# oresat-batteries.net
KiCad netlist of a schematic drawn in EAGLE
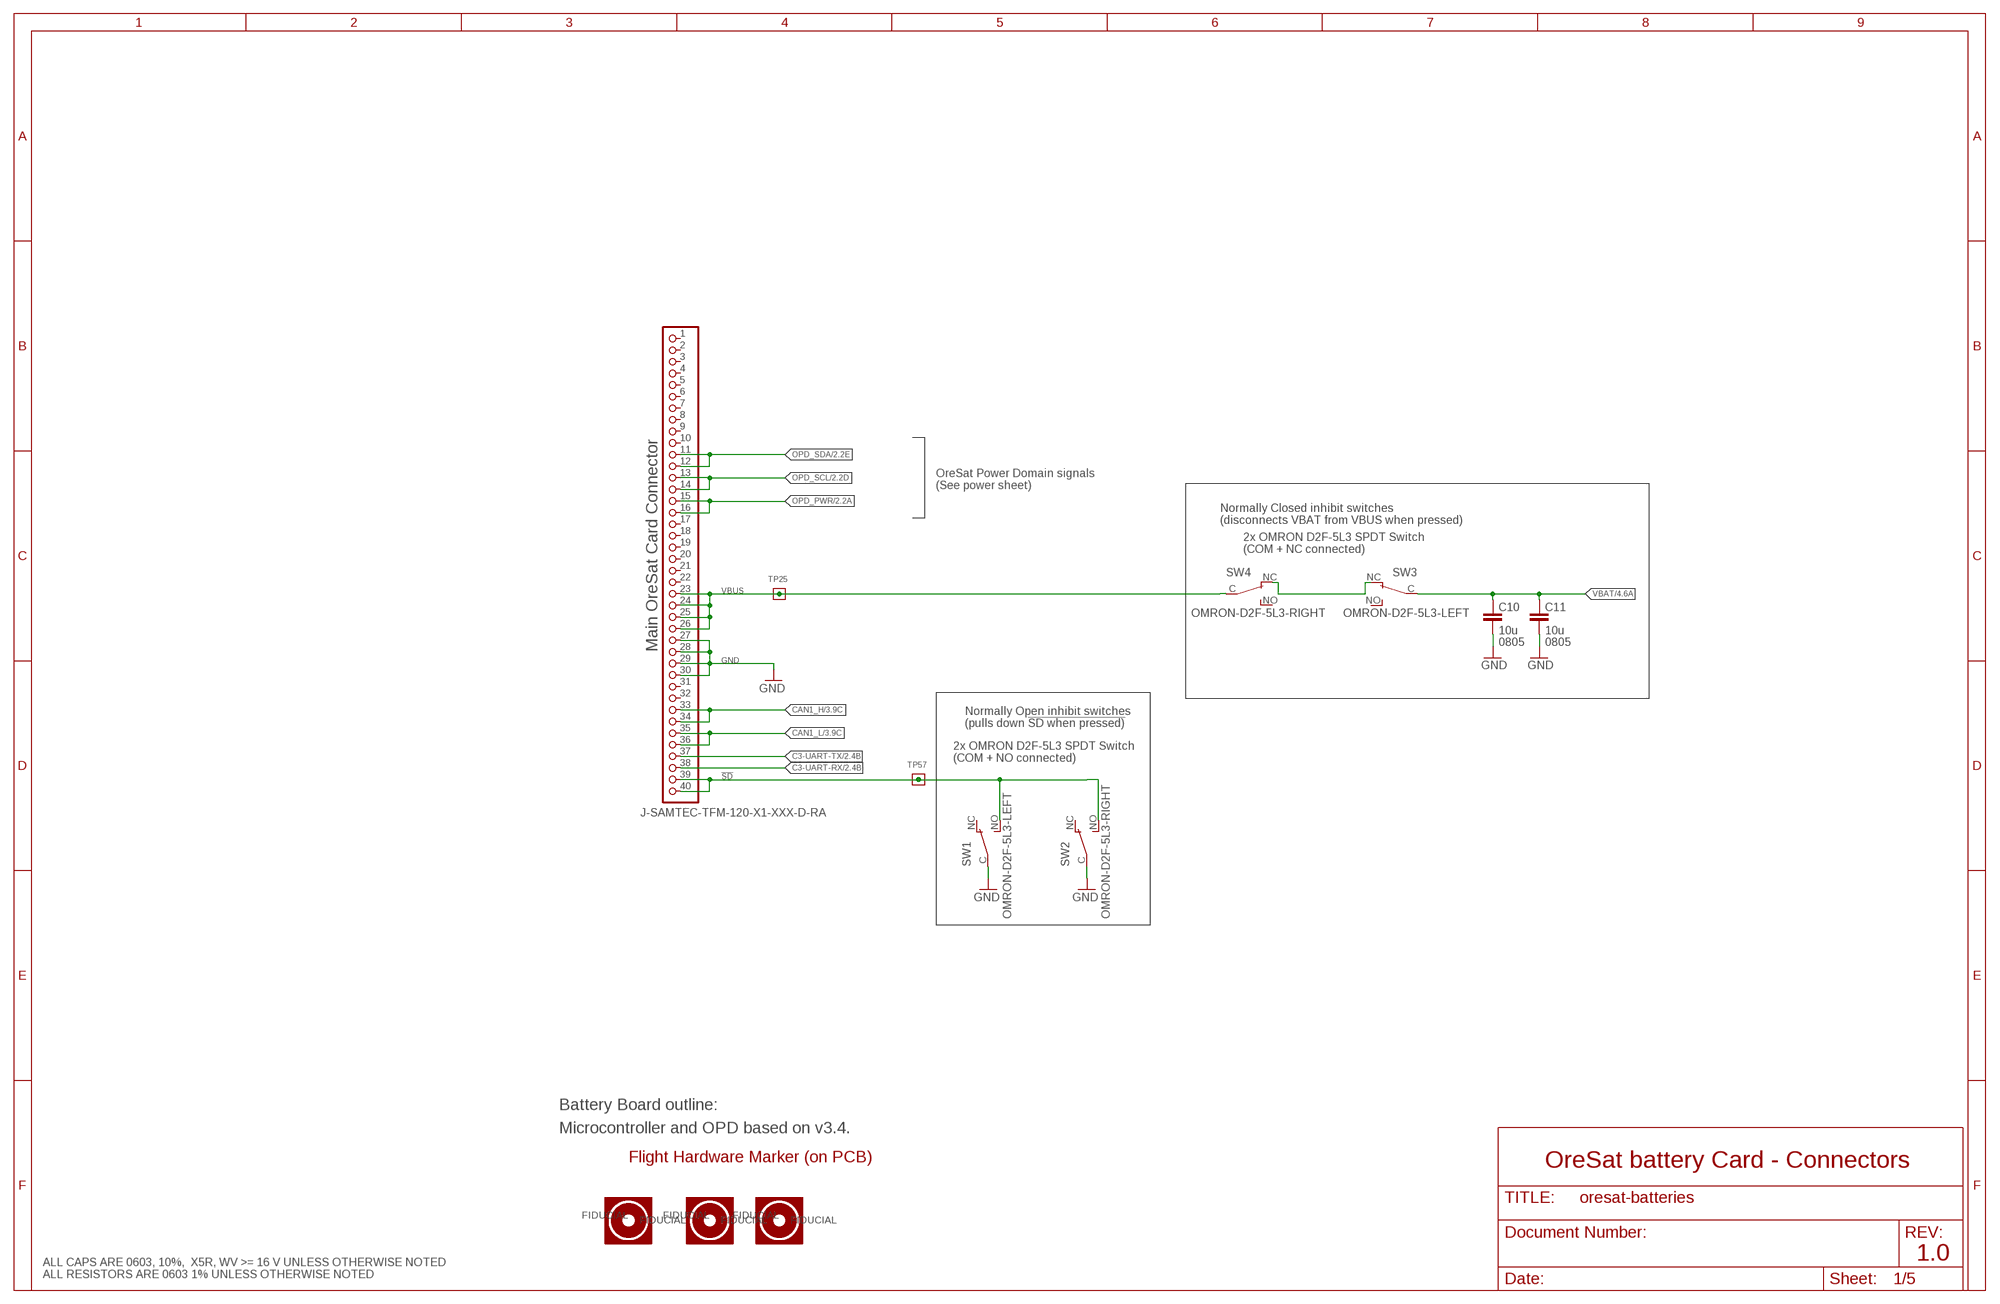
[diagram p0: schematic, sheet 1]
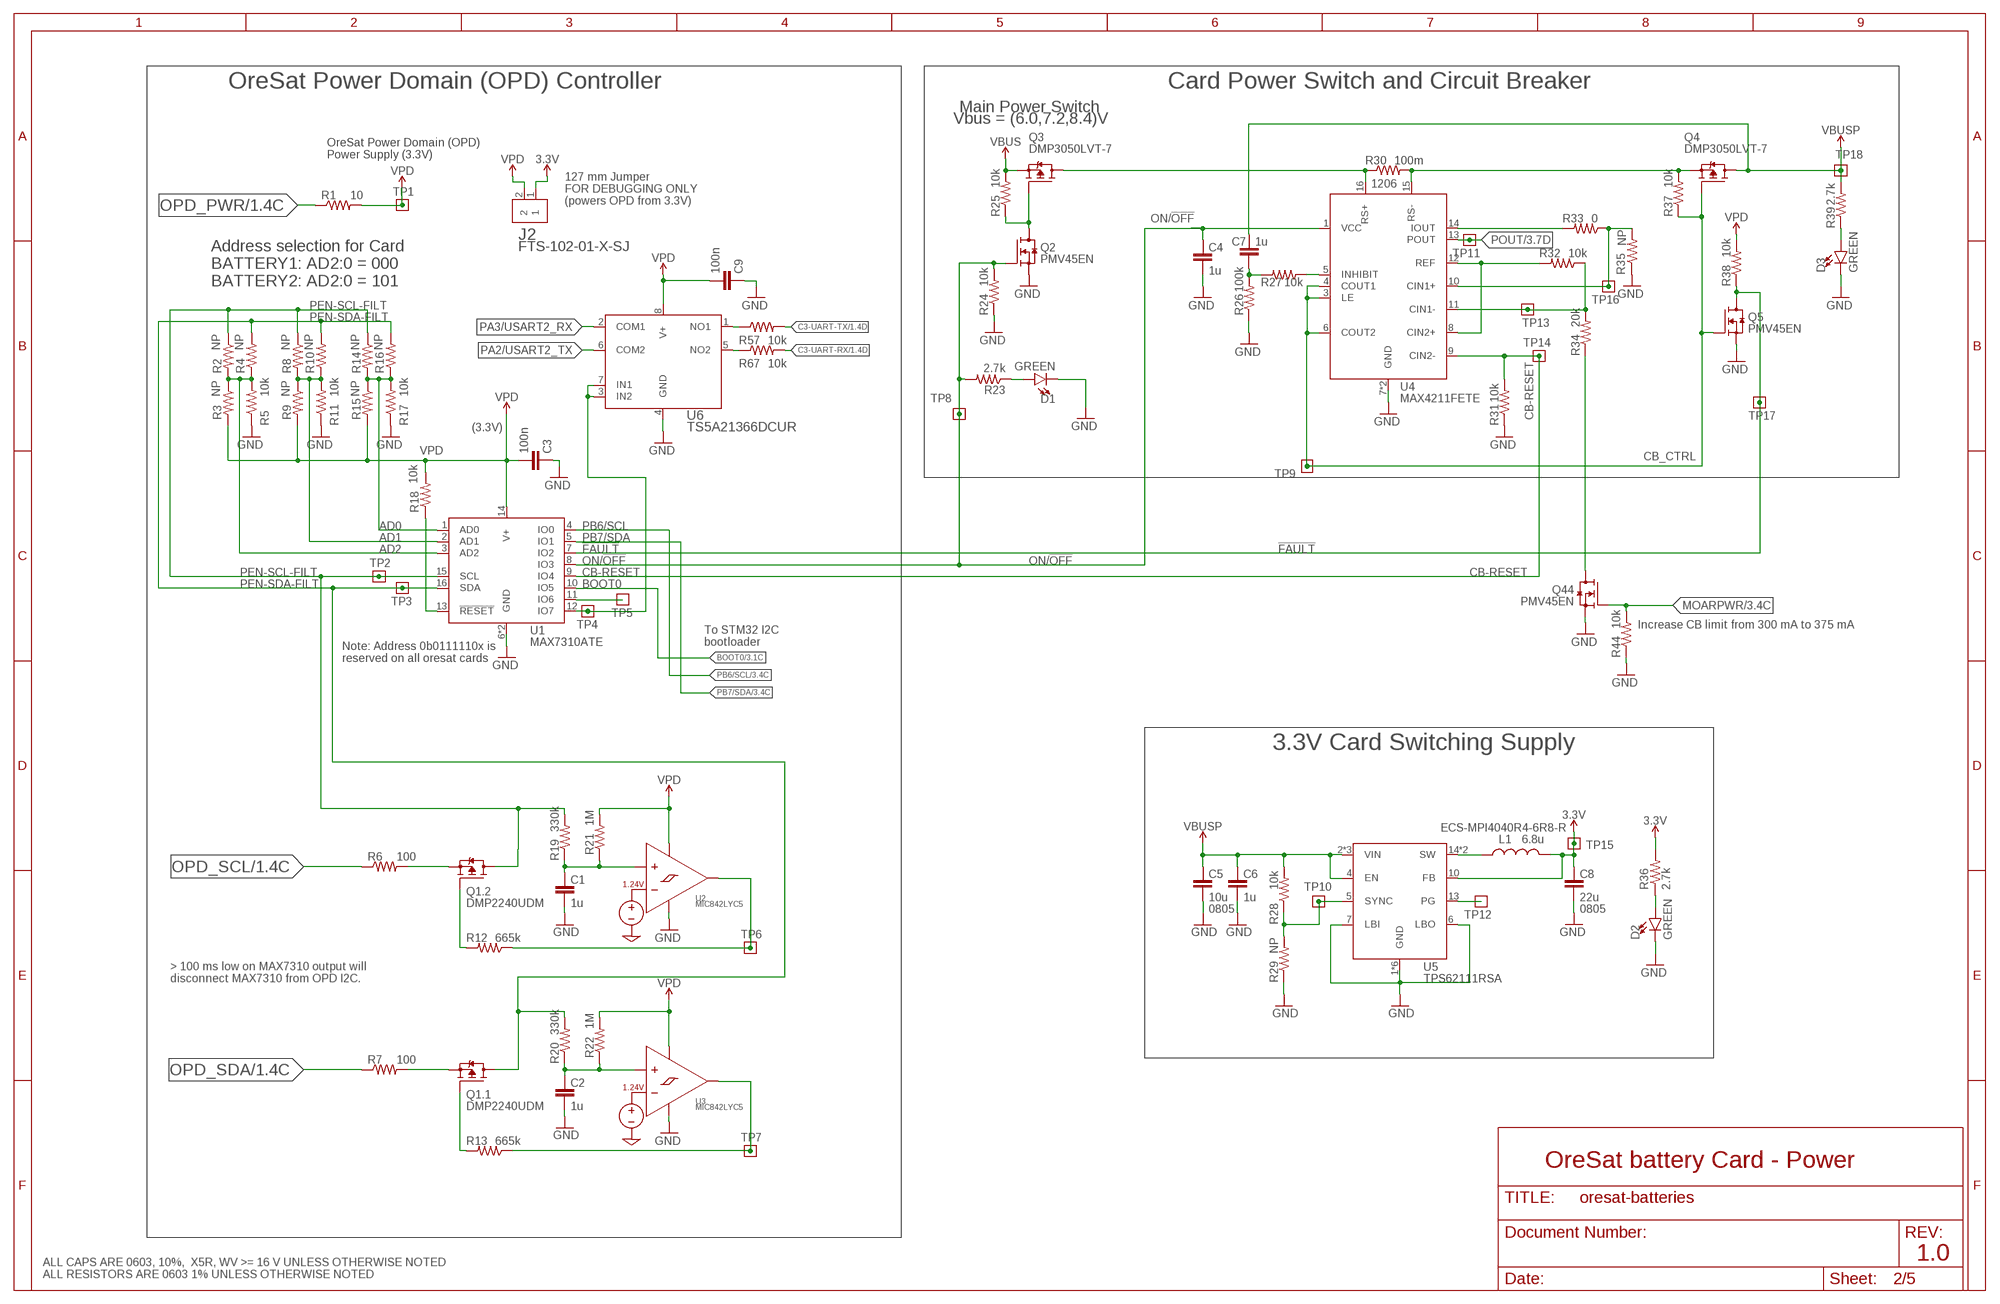
[diagram p1: schematic, sheet 2]
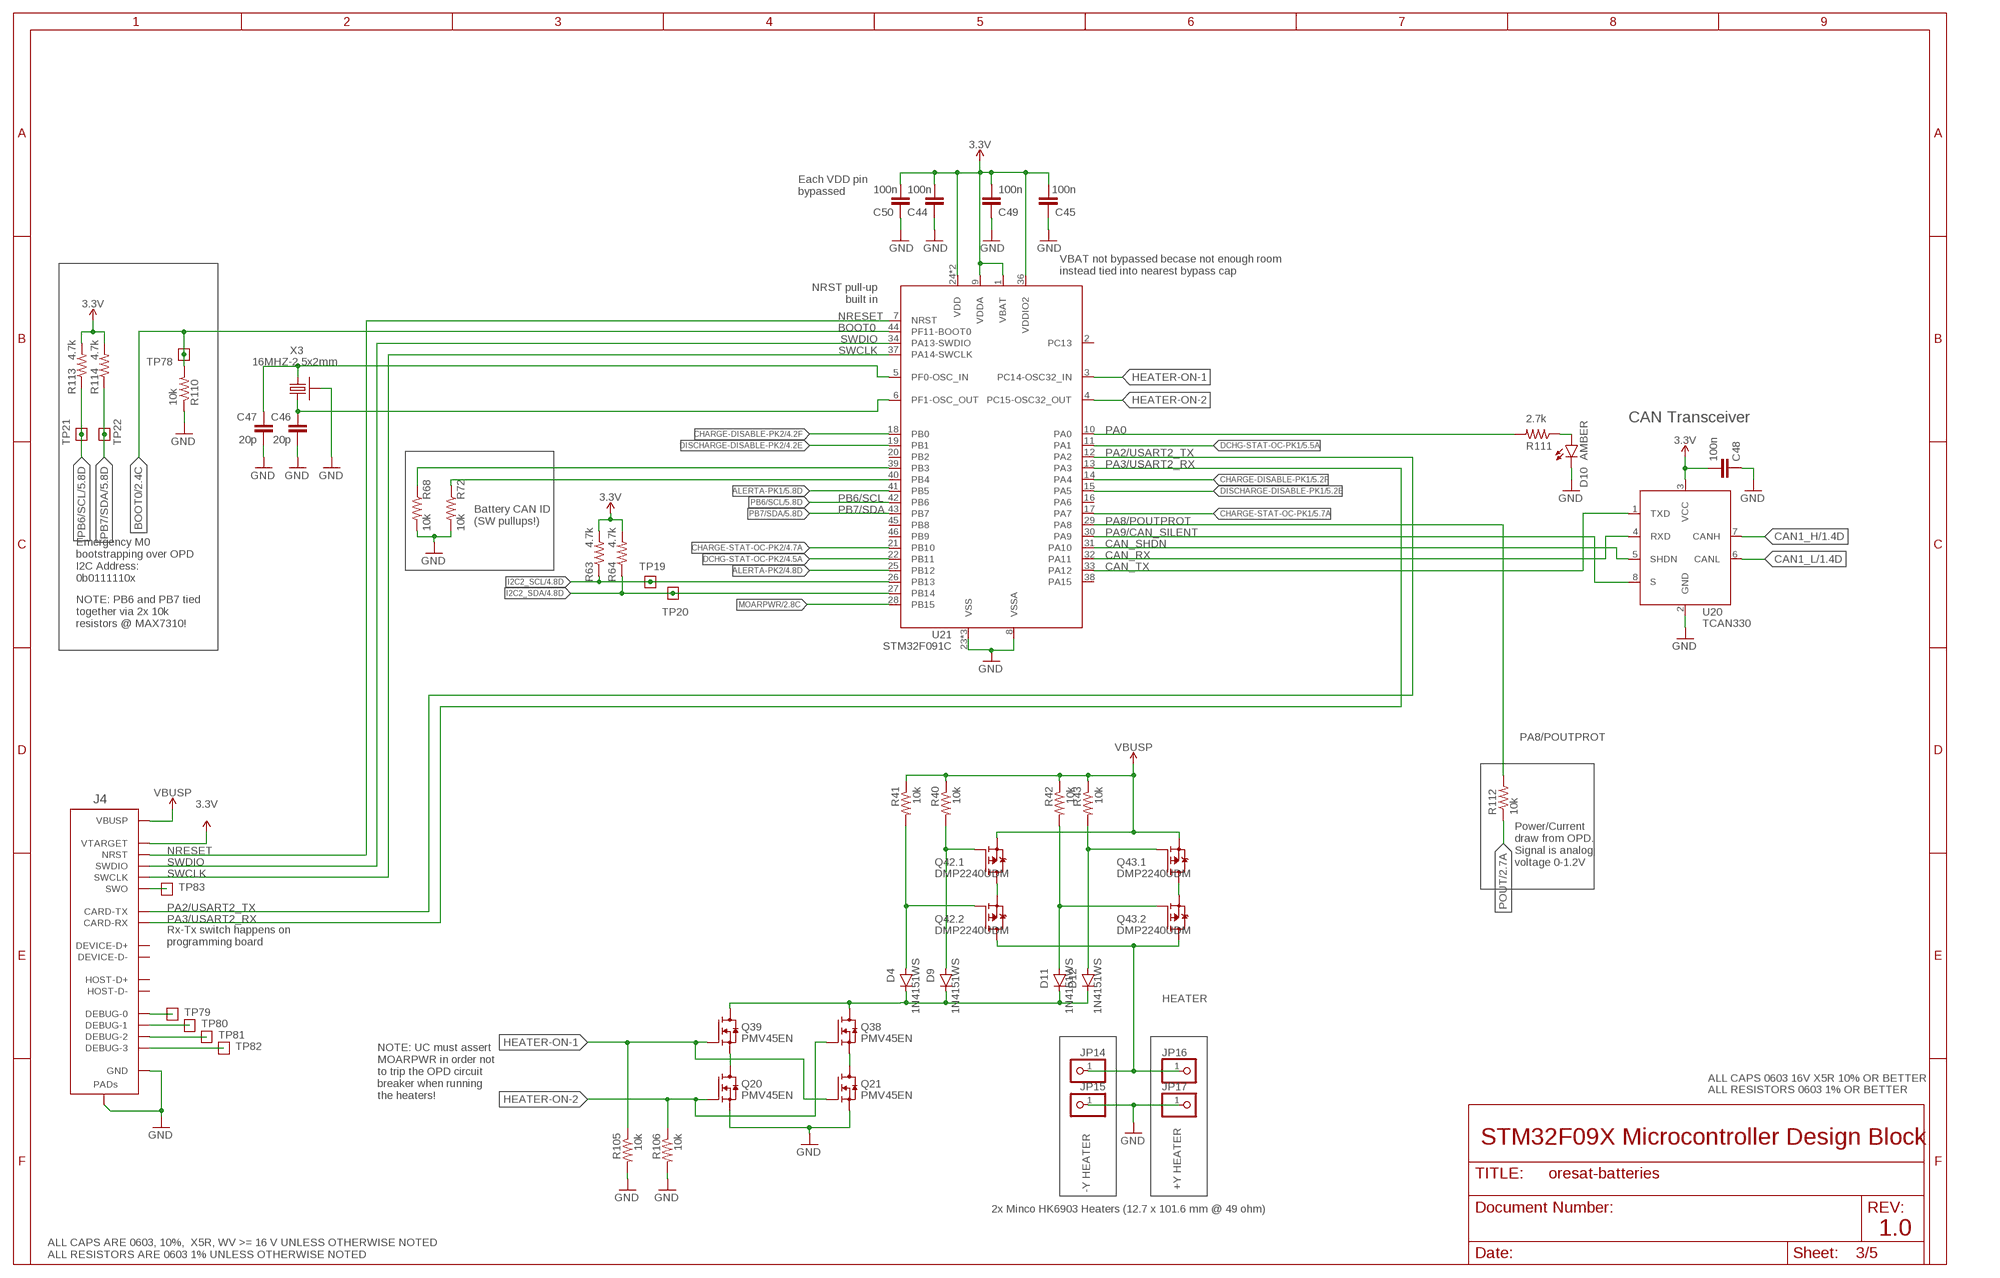
[diagram p2: schematic, sheet 3]
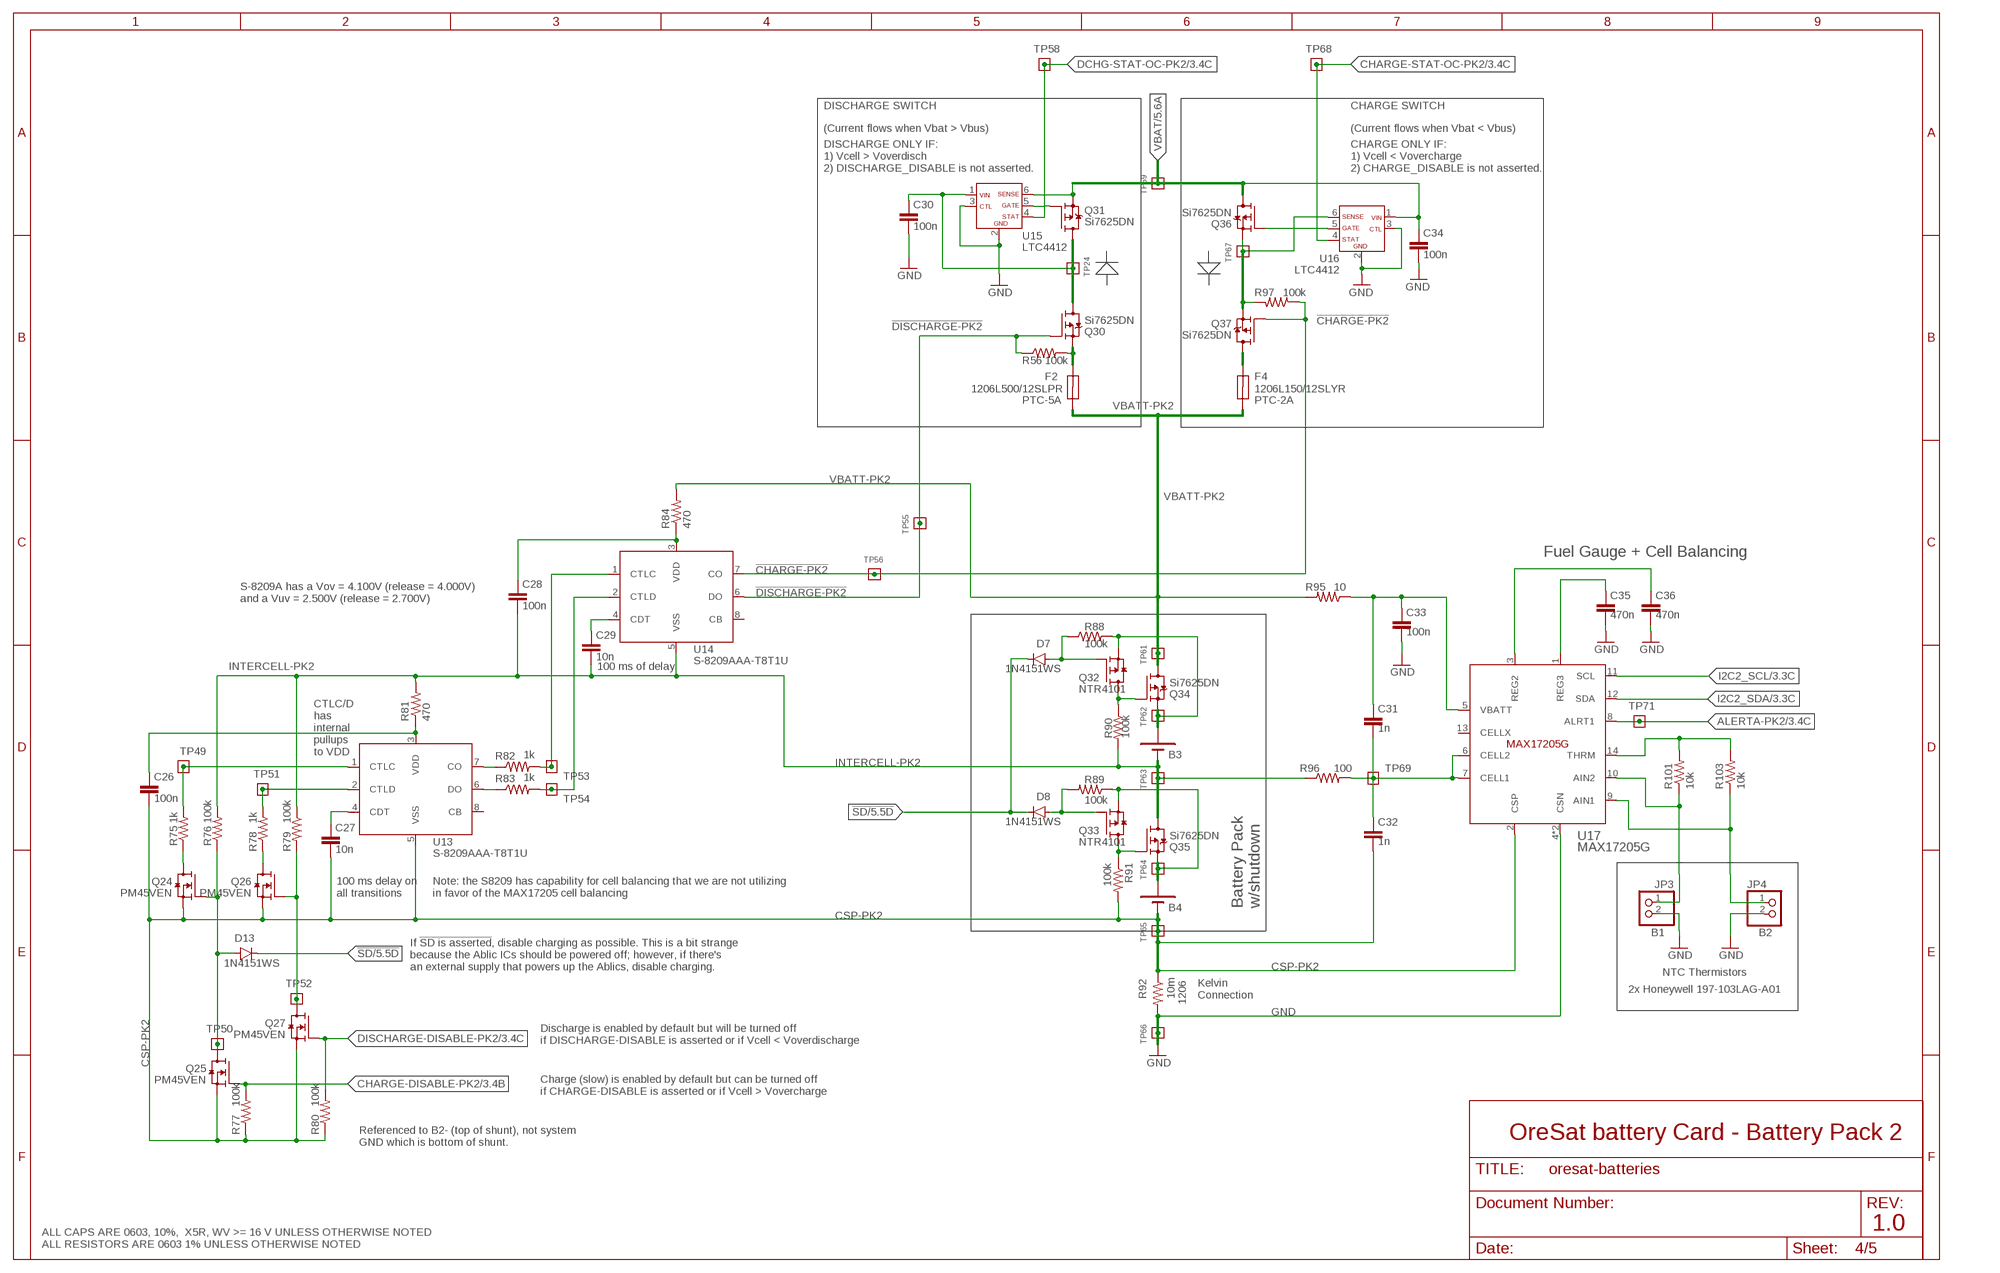
[diagram p3: schematic, sheet 4]
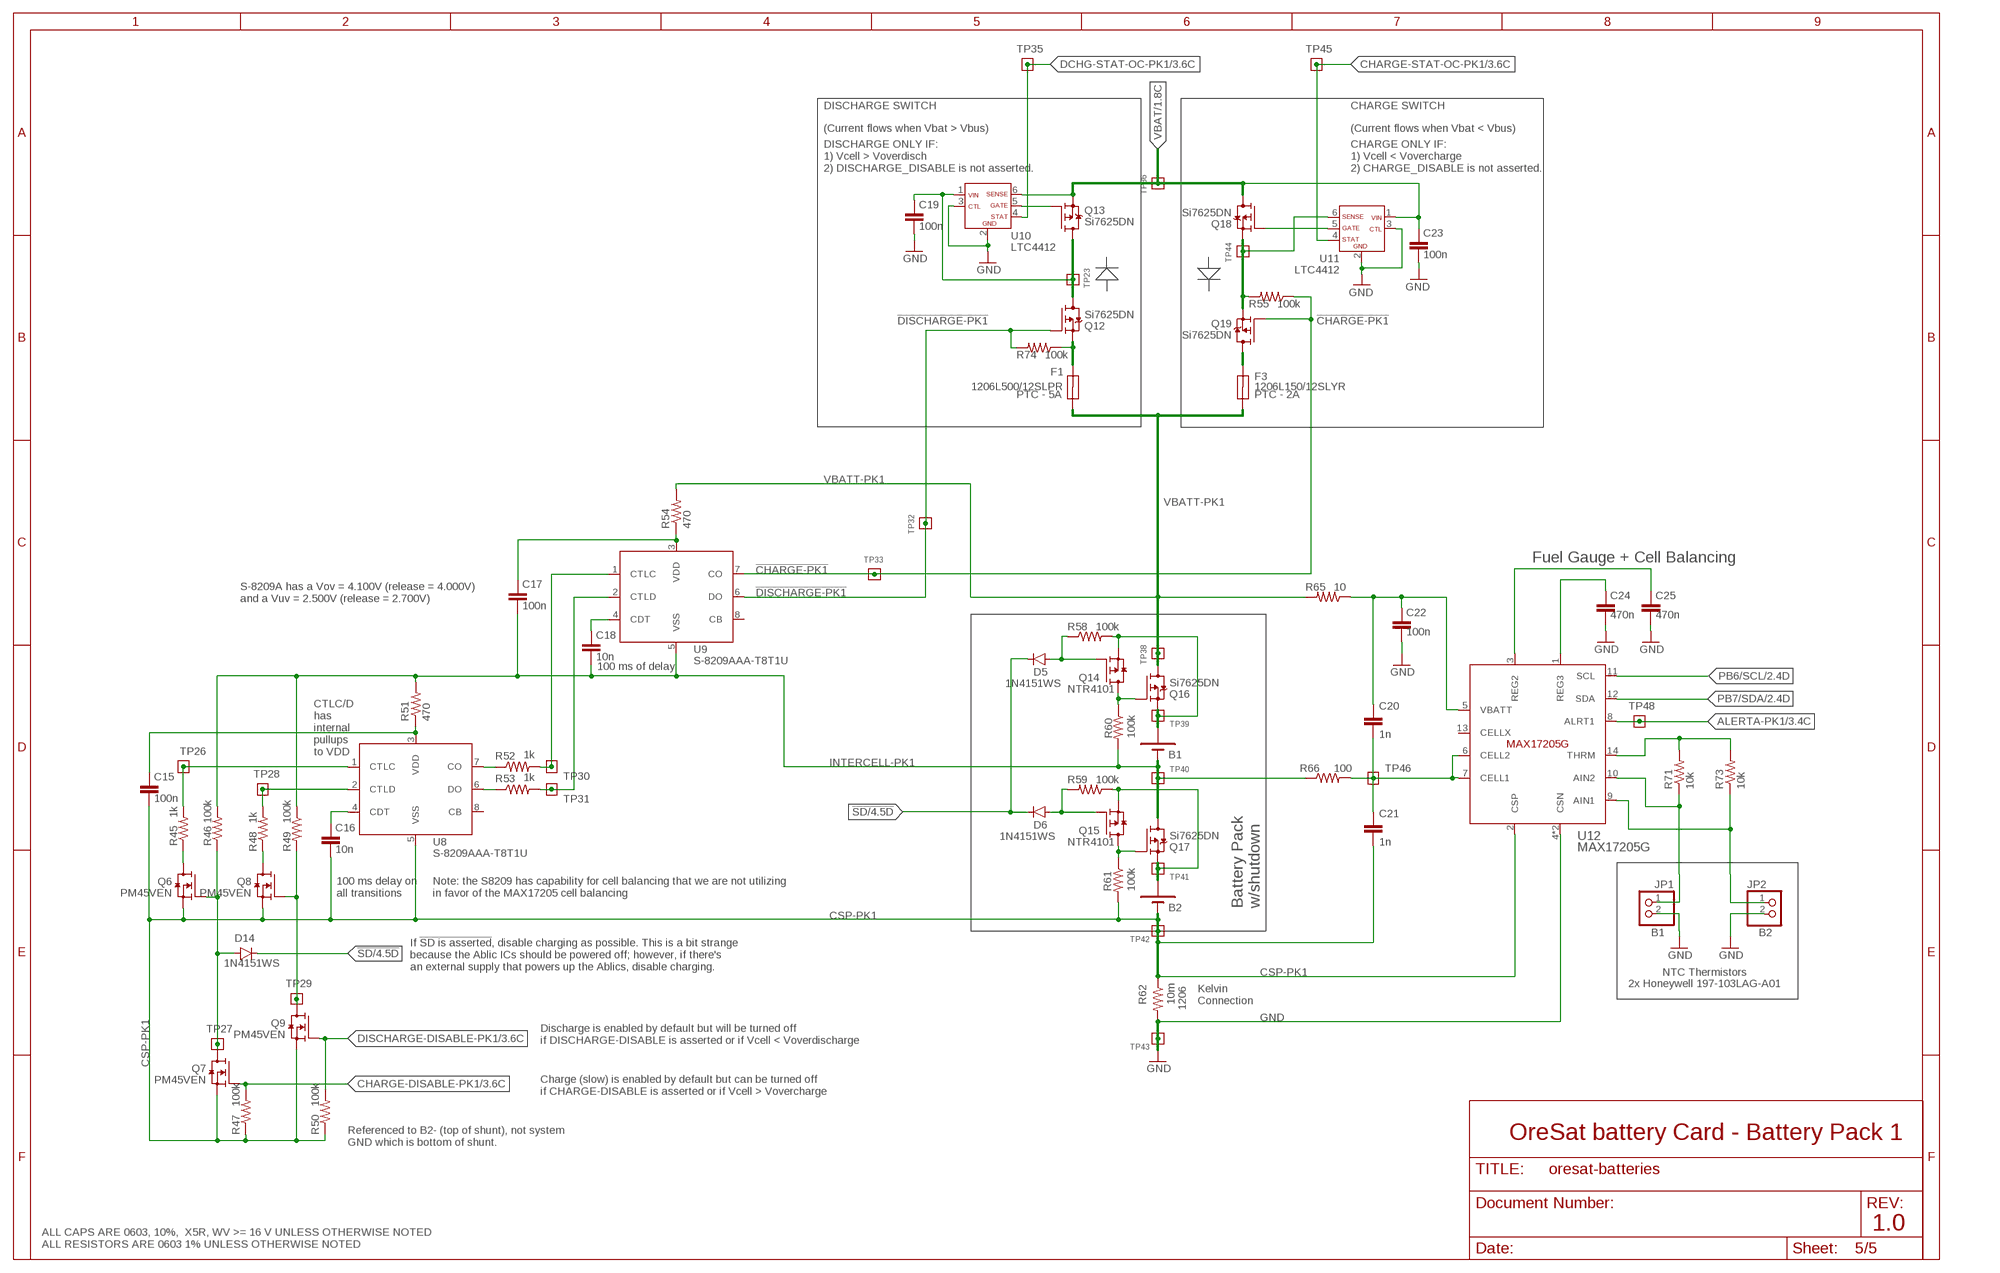
[diagram p4: schematic, sheet 5]

(export (version "E")
  (design (tool "Eeschema 10.0.6"))
  (components
    (comp (ref "C44")
      (value "100n")
      (footprint "eagle-import:.0603-C-NOSILK")
      (fields (field (name "MFR") "Samsung") (field (name "MPN") "C0603C104M4RACTU"))
      (libsource (lib "eagle-import") (part "C-EU0603-C-NOSILK"))
    )
    (comp (ref "C45")
      (value "100n")
      (footprint "eagle-import:.0603-C-NOSILK")
      (fields (field (name "MFR") "Samsung") (field (name "MPN") "C0603C104M4RACTU"))
      (libsource (lib "eagle-import") (part "C-EU0603-C-NOSILK"))
    )
    (comp (ref "C46")
      (value "20p")
      (footprint "eagle-import:.0603-C-NOSILK")
      (fields (field (name "MFR") "Yageo") (field (name "MPN") "CC0603JRNPO9BN200"))
      (libsource (lib "eagle-import") (part "C-EU0603-C-NOSILK"))
    )
    (comp (ref "C47")
      (value "20p")
      (footprint "eagle-import:.0603-C-NOSILK")
      (fields (field (name "MFR") "Yageo") (field (name "MPN") "CC0603JRNPO9BN200"))
      (libsource (lib "eagle-import") (part "C-EU0603-C-NOSILK"))
    )
    (comp (ref "C48")
      (value "100n")
      (footprint "eagle-import:.0603-C-NOSILK")
      (fields (field (name "MFR") "Samsung") (field (name "MPN") "C0603C104M4RACTU"))
      (libsource (lib "eagle-import") (part "C-EU0603-C-NOSILK"))
    )
    (comp (ref "C49")
      (value "100n")
      (footprint "eagle-import:.0603-C-NOSILK")
      (fields (field (name "MFR") "Samsung") (field (name "MPN") "C0603C104M4RACTU"))
      (libsource (lib "eagle-import") (part "C-EU0603-C-NOSILK"))
    )
    (comp (ref "C50")
      (value "100n")
      (footprint "eagle-import:.0603-C-NOSILK")
      (fields (field (name "MFR") "Samsung") (field (name "MPN") "C0603C104M4RACTU"))
      (libsource (lib "eagle-import") (part "C-EU0603-C-NOSILK"))
    )
    (comp (ref "D4")
      (value "1N4151WS")
      (footprint "eagle-import:SOD323-R")
      (fields (field (name "MFR") "Vishay") (field (name "MPN") "1N4151WS-E3-08"))
      (libsource (lib "eagle-import") (part "DIODE-SOD323-R"))
    )
    (comp (ref "D9")
      (value "1N4151WS")
      (footprint "eagle-import:SOD323-R")
      (fields (field (name "MFR") "Vishay") (field (name "MPN") "1N4151WS-E3-08"))
      (libsource (lib "eagle-import") (part "DIODE-SOD323-R"))
    )
    (comp (ref "D10")
      (value "AMBER")
      (footprint "eagle-import:LED-0603")
      (fields (field (name "MFR") "Inolux") (field (name "MPN") "IN-S63AT5A"))
      (libsource (lib "eagle-import") (part "LED-GREEN0603"))
    )
    (comp (ref "D11")
      (value "1N4151WS")
      (footprint "eagle-import:SOD323-R")
      (fields (field (name "MFR") "Vishay") (field (name "MPN") "1N4151WS-E3-08"))
      (libsource (lib "eagle-import") (part "DIODE-SOD323-R"))
    )
    (comp (ref "D12")
      (value "1N4151WS")
      (footprint "eagle-import:SOD323-R")
      (fields (field (name "MFR") "Vishay") (field (name "MPN") "1N4151WS-E3-08"))
      (libsource (lib "eagle-import") (part "DIODE-SOD323-R"))
    )
    (comp (ref "J4")
      (value "ORESAT-DEBUG-CONNECTOR-ALL")
      (footprint "eagle-import:TE_2-1734592-0")
      (fields
        (field (name "MPN") "2-1734592-0")
        (field (name "DPN") "A100287CT-ND")
        (field (name "MFR") "TE")
        (field (name "MPN_1") "2-1734592-0")
      )
      (libsource (lib "eagle-import") (part "ORESAT-DEBUG-CONNECTOR-ALL"))
    )
    (comp (ref "JP14")
      (value "PINHD-1X1")
      (footprint "eagle-import:1X01")
      (libsource (lib "eagle-import") (part "PINHD-1X1"))
    )
    (comp (ref "JP15")
      (value "PINHD-1X1")
      (footprint "eagle-import:1X01")
      (libsource (lib "eagle-import") (part "PINHD-1X1"))
    )
    (comp (ref "JP16")
      (value "PINHD-1X1")
      (footprint "eagle-import:1X01")
      (libsource (lib "eagle-import") (part "PINHD-1X1"))
    )
    (comp (ref "JP17")
      (value "PINHD-1X1")
      (footprint "eagle-import:1X01")
      (libsource (lib "eagle-import") (part "PINHD-1X1"))
    )
    (comp (ref "Q20")
      (value "PMV45EN")
      (footprint "eagle-import:SOT23-3")
      (libsource (lib "eagle-import") (part "N-MOSFET-SOT-23-3"))
    )
    (comp (ref "Q21")
      (value "PMV45EN")
      (footprint "eagle-import:SOT23-3")
      (libsource (lib "eagle-import") (part "N-MOSFET-SOT-23-3"))
    )
    (comp (ref "Q38")
      (value "PMV45EN")
      (footprint "eagle-import:SOT23-3")
      (libsource (lib "eagle-import") (part "N-MOSFET-SOT-23-3"))
    )
    (comp (ref "Q39")
      (value "PMV45EN")
      (footprint "eagle-import:SOT23-3")
      (libsource (lib "eagle-import") (part "N-MOSFET-SOT-23-3"))
    )
    (comp (ref "Q42")
      (value "DMP2240UDM")
      (footprint "eagle-import:SOT23-6")
      (libsource (lib "eagle-import") (part "Q-MOSFET-PCH-dual-SOT23-6_MOSFET-PCH-SOT23-6"))
    )
    (comp (ref "Q43")
      (value "DMP2240UDM")
      (footprint "eagle-import:SOT23-6")
      (libsource (lib "eagle-import") (part "Q-MOSFET-PCH-dual-SOT23-6_MOSFET-PCH-SOT23-6"))
    )
    (comp (ref "R40")
      (value "10k")
      (footprint "eagle-import:.0603-C-NOSILK")
      (fields (field (name "MFR") "Yageo") (field (name "MPN") "RC0603FR-0710KL"))
      (libsource (lib "eagle-import") (part "R-US_0603-C-NOSILK"))
    )
    (comp (ref "R41")
      (value "10k")
      (footprint "eagle-import:.0603-C-NOSILK")
      (fields (field (name "MFR") "Yageo") (field (name "MPN") "RC0603FR-0710KL"))
      (libsource (lib "eagle-import") (part "R-US_0603-C-NOSILK"))
    )
    (comp (ref "R42")
      (value "10k")
      (footprint "eagle-import:.0603-C-NOSILK")
      (fields (field (name "MFR") "Yageo") (field (name "MPN") "RC0603FR-0710KL"))
      (libsource (lib "eagle-import") (part "R-US_0603-C-NOSILK"))
    )
    (comp (ref "R43")
      (value "10k")
      (footprint "eagle-import:.0603-C-NOSILK")
      (fields (field (name "MFR") "Yageo") (field (name "MPN") "RC0603FR-0710KL"))
      (libsource (lib "eagle-import") (part "R-US_0603-C-NOSILK"))
    )
    (comp (ref "R63")
      (value "4.7k")
      (footprint "eagle-import:.0603-C-NOSILK")
      (fields (field (name "MFR") "TE Connectivity") (field (name "MPN") "RR0816P-472-D"))
      (libsource (lib "eagle-import") (part "R-US_0603-C-NOSILK"))
    )
    (comp (ref "R64")
      (value "4.7k")
      (footprint "eagle-import:.0603-C-NOSILK")
      (fields (field (name "MFR") "TE Connectivity") (field (name "MPN") "RR0816P-472-D"))
      (libsource (lib "eagle-import") (part "R-US_0603-C-NOSILK"))
    )
    (comp (ref "R68")
      (value "10k")
      (footprint "eagle-import:.0603-C-NOSILK")
      (fields (field (name "MFR") "TE Connectivity") (field (name "MPN") "RR0816P-472-D"))
      (libsource (lib "eagle-import") (part "R-US_0603-C-NOSILK"))
    )
    (comp (ref "R72")
      (value "10k")
      (footprint "eagle-import:.0603-C-NOSILK")
      (fields (field (name "MFR") "TE Connectivity") (field (name "MPN") "RR0816P-472-D"))
      (libsource (lib "eagle-import") (part "R-US_0603-C-NOSILK"))
    )
    (comp (ref "R105")
      (value "10k")
      (footprint "eagle-import:.0603-C-NOSILK")
      (fields (field (name "MFR") "Yageo") (field (name "MPN") "RC0603FR-0710KL"))
      (libsource (lib "eagle-import") (part "R-US_0603-C-NOSILK"))
    )
    (comp (ref "R106")
      (value "10k")
      (footprint "eagle-import:.0603-C-NOSILK")
      (fields (field (name "MFR") "Yageo") (field (name "MPN") "RC0603FR-0710KL"))
      (libsource (lib "eagle-import") (part "R-US_0603-C-NOSILK"))
    )
    (comp (ref "R110")
      (value "10k")
      (footprint "eagle-import:.0603-C-NOSILK")
      (fields (field (name "MFR") "Yageo") (field (name "MPN") "RC0603FR-0710KL"))
      (libsource (lib "eagle-import") (part "R-US_0603-C-NOSILK"))
    )
    (comp (ref "R111")
      (value "2.7k")
      (footprint "eagle-import:.0603-C-NOSILK")
      (fields (field (name "MFR") "TE") (field (name "MPN") "CRGCQ0603F2K7"))
      (libsource (lib "eagle-import") (part "R-US_0603-C-NOSILK"))
    )
    (comp (ref "R112")
      (value "10k")
      (footprint "eagle-import:.0603-C-NOSILK")
      (fields (field (name "MFR") "Yageo") (field (name "MPN") "RC0603FR-0710KL"))
      (libsource (lib "eagle-import") (part "R-US_0603-C-NOSILK"))
    )
    (comp (ref "R113")
      (value "4.7k")
      (footprint "eagle-import:.0603-C-NOSILK")
      (fields (field (name "MFR") "TE Connectivity") (field (name "MPN") "RR0816P-472-D"))
      (libsource (lib "eagle-import") (part "R-US_0603-C-NOSILK"))
    )
    (comp (ref "R114")
      (value "4.7k")
      (footprint "eagle-import:.0603-C-NOSILK")
      (fields (field (name "MFR") "TE Connectivity") (field (name "MPN") "RR0816P-472-D"))
      (libsource (lib "eagle-import") (part "R-US_0603-C-NOSILK"))
    )
    (comp (ref "TP19")
      (value "TEST-POINT-LARGE-SQUARE")
      (footprint "eagle-import:1X01")
      (libsource (lib "eagle-import") (part "TEST-POINT-LARGE-SQUARE"))
    )
    (comp (ref "TP20")
      (value "TEST-POINT-LARGE-SQUARE")
      (footprint "eagle-import:1X01")
      (libsource (lib "eagle-import") (part "TEST-POINT-LARGE-SQUARE"))
    )
    (comp (ref "TP21")
      (value "TEST-POINT-LARGE-SQUARE")
      (footprint "eagle-import:1X01")
      (libsource (lib "eagle-import") (part "TEST-POINT-LARGE-SQUARE"))
    )
    (comp (ref "TP22")
      (value "TEST-POINT-LARGE-SQUARE")
      (footprint "eagle-import:1X01")
      (libsource (lib "eagle-import") (part "TEST-POINT-LARGE-SQUARE"))
    )
    (comp (ref "TP78")
      (value "TEST-POINT-LARGE-SQUARE")
      (footprint "eagle-import:1X01")
      (libsource (lib "eagle-import") (part "TEST-POINT-LARGE-SQUARE"))
    )
    (comp (ref "TP79")
      (value "TEST-POINT-LARGE-SQUARE")
      (footprint "eagle-import:1X01")
      (libsource (lib "eagle-import") (part "TEST-POINT-LARGE-SQUARE"))
    )
    (comp (ref "TP80")
      (value "TEST-POINT-LARGE-SQUARE")
      (footprint "eagle-import:1X01")
      (libsource (lib "eagle-import") (part "TEST-POINT-LARGE-SQUARE"))
    )
    (comp (ref "TP81")
      (value "TEST-POINT-LARGE-SQUARE")
      (footprint "eagle-import:1X01")
      (libsource (lib "eagle-import") (part "TEST-POINT-LARGE-SQUARE"))
    )
    (comp (ref "TP82")
      (value "TEST-POINT-LARGE-SQUARE")
      (footprint "eagle-import:1X01")
      (libsource (lib "eagle-import") (part "TEST-POINT-LARGE-SQUARE"))
    )
    (comp (ref "TP83")
      (value "TEST-POINT-LARGE-SQUARE")
      (footprint "eagle-import:1X01")
      (libsource (lib "eagle-import") (part "TEST-POINT-LARGE-SQUARE"))
    )
    (comp (ref "U20")
      (value "TCAN330")
      (footprint "eagle-import:SOT23-8_TI-DCN")
      (fields (field (name "MFR") "Texas Instruments") (field (name "MPN") "TCAN330GDCNT"))
      (libsource (lib "eagle-import") (part "TCAN330"))
    )
    (comp (ref "U21")
      (value "STM32F091C")
      (footprint "eagle-import:STM32F091C")
      (fields (field (name "MFR") "STMicroelectronics") (field (name "MPN") "STM32F091CBT6"))
      (libsource (lib "eagle-import") (part "STM32F091C"))
    )
    (comp (ref "X3")
      (value "16MHZ-2.5x2mm")
      (footprint "eagle-import:CRYSTAL_2.5X2")
      (fields (field (name "MFR") "ECS Inc.") (field (name "MPN") "ECS-160-10-36Q-ES-TR"))
      (libsource (lib "eagle-import") (part "CRYSTAL-WITH-GND"))
    )
    (comp (ref "C1")
      (value "1u")
      (footprint "eagle-import:.0603-C-NOSILK")
      (fields (field (name "MFR") "Samsung") (field (name "MPN") "CL10B105MO8NNWC"))
      (libsource (lib "eagle-import") (part "C-EU0603-C-NOSILK"))
    )
    (comp (ref "C2")
      (value "1u")
      (footprint "eagle-import:.0603-C-NOSILK")
      (fields (field (name "MFR") "Samsung") (field (name "MPN") "CL10B105MO8NNWC"))
      (libsource (lib "eagle-import") (part "C-EU0603-C-NOSILK"))
    )
    (comp (ref "C3")
      (value "100n")
      (footprint "eagle-import:.0603-C-NOSILK")
      (fields (field (name "MFR") "Samsung") (field (name "MPN") "CL05B104KO5NNNC"))
      (libsource (lib "eagle-import") (part "C-EU0603-C-NOSILK"))
    )
    (comp (ref "C4")
      (value "1u")
      (footprint "eagle-import:.0603-C-NOSILK")
      (fields (field (name "MFR") "Samsung") (field (name "MPN") "CL10B105MO8NNWC"))
      (libsource (lib "eagle-import") (part "C-EU0603-C-NOSILK"))
    )
    (comp (ref "C5")
      (value "10u")
      (footprint "eagle-import:.0805-B-NOSILK")
      (fields (field (name "MFR") "Samsung") (field (name "MPN") "CL21A106KOFNNNE"))
      (libsource (lib "eagle-import") (part "C-EU0805-B-NOSILK"))
    )
    (comp (ref "C6")
      (value "1u")
      (footprint "eagle-import:.0603-C-NOSILK")
      (fields (field (name "MFR") "Yageo") (field (name "MPN") "CC0603KRX7R7BB105"))
      (libsource (lib "eagle-import") (part "C-EU0603-C-NOSILK"))
    )
    (comp (ref "C7")
      (value "1u")
      (footprint "eagle-import:.0603-C-NOSILK")
      (libsource (lib "eagle-import") (part "C-EU0603-C-NOSILK"))
    )
    (comp (ref "C8")
      (value "22u")
      (footprint "eagle-import:.0805-B-NOSILK")
      (fields (field (name "MFR") "Murata") (field (name "MPN") "GRM21BR61A226ME51L"))
      (libsource (lib "eagle-import") (part "C-EU0805-B-NOSILK"))
    )
    (comp (ref "C9")
      (value "100n")
      (footprint "eagle-import:.0603-C-NOSILK")
      (fields (field (name "MFR") "Samsung") (field (name "MPN") "CL05B104KO5NNNC"))
      (libsource (lib "eagle-import") (part "C-EU0603-C-NOSILK"))
    )
    (comp (ref "D1")
      (value "GREEN")
      (footprint "eagle-import:LED-0603")
      (fields (field (name "MFR") "Inolux") (field (name "MPN") "IN-S63AT5A"))
      (libsource (lib "eagle-import") (part "LED-GREEN0603"))
    )
    (comp (ref "D2")
      (value "GREEN")
      (footprint "eagle-import:LED-0603")
      (fields (field (name "MFR") "Rohm") (field (name "MPN") "SML-E12M8WT86"))
      (libsource (lib "eagle-import") (part "LED-GREEN0603"))
    )
    (comp (ref "D3")
      (value "GREEN")
      (footprint "eagle-import:LED-0603")
      (fields (field (name "MFR") "Rohm") (field (name "MPN") "SML-E12M8WT86"))
      (libsource (lib "eagle-import") (part "LED-GREEN0603"))
    )
    (comp (ref "J2")
      (value "FTS-102-01-X-SJ")
      (footprint "eagle-import:SAMTEC-FTS-102-01-X-S")
      (libsource (lib "eagle-import") (part "SAMTEC-FTS-102-01-X-SJ"))
    )
    (comp (ref "L1")
      (value "6.8u")
      (footprint "eagle-import:ECS-MPI4040")
      (fields (field (name "MFR") "ECS") (field (name "MPN") "ECS-MPI4040R4-6R8-R"))
      (libsource (lib "eagle-import") (part "L-ECS-MPI4040"))
    )
    (comp (ref "Q1")
      (value "DMP2240UDM")
      (footprint "eagle-import:SOT23-6")
      (fields
        (field (name "DIS") "Digi-Key")
        (field (name "DPN") "GRM21BR61A226ME51L ")
        (field (name "MFR") "Diodes Inc")
        (field (name "MPN") "DMP2240UDM")
      )
      (libsource (lib "eagle-import") (part "Q-MOSFET-PCH-dual-SOT23-6_MOSFET-PCH-SOT23-6"))
    )
    (comp (ref "Q2")
      (value "PMV45EN")
      (footprint "eagle-import:SOT23-3")
      (fields (field (name "MFR") "Nexperia") (field (name "MPN") "PMV45EN2R"))
      (libsource (lib "eagle-import") (part "N-MOSFET-SOT-23-3"))
    )
    (comp (ref "Q3")
      (value "DMP3050LVT-7")
      (footprint "eagle-import:SOT23-6")
      (fields (field (name "MFR") "Diodes Inc"))
      (libsource (lib "eagle-import") (part "MOSFET-PCH-SOT23-6"))
    )
    (comp (ref "Q4")
      (value "DMP3050LVT-7")
      (footprint "eagle-import:SOT23-6")
      (fields (field (name "MFR") "Diodes Inc"))
      (libsource (lib "eagle-import") (part "MOSFET-PCH-SOT23-6"))
    )
    (comp (ref "Q5")
      (value "PMV45EN")
      (footprint "eagle-import:SOT23-3")
      (fields (field (name "MFR") "Nexperia") (field (name "MPN") "PMV45EN2R"))
      (libsource (lib "eagle-import") (part "N-MOSFET-SOT-23-3"))
    )
    (comp (ref "Q44")
      (value "PMV45EN")
      (footprint "eagle-import:SOT23-3")
      (fields (field (name "MFR") "Nexperia") (field (name "MPN") "PMV45EN2R"))
      (libsource (lib "eagle-import") (part "N-MOSFET-SOT-23-3"))
    )
    (comp (ref "R1")
      (value "10")
      (footprint "eagle-import:.0603-C-NOSILK")
      (fields (field (name "MFR") "Yageo") (field (name "MPN") "RC0603FR-0710RL"))
      (libsource (lib "eagle-import") (part "R-US_0603-C-NOSILK"))
    )
    (comp (ref "R2")
      (value "NP")
      (footprint "eagle-import:.0603-C-NOSILK")
      (fields (field (name "MFR") "Yageo") (field (name "MPN") "RC0603FR-07665KL"))
      (libsource (lib "eagle-import") (part "R-US_0603-C-NOSILK"))
    )
    (comp (ref "R3")
      (value "NP")
      (footprint "eagle-import:.0603-C-NOSILK")
      (fields (field (name "MFR") "Yageo") (field (name "MPN") "RC0603FR-07665KL"))
      (libsource (lib "eagle-import") (part "R-US_0603-C-NOSILK"))
    )
    (comp (ref "R4")
      (value "NP")
      (footprint "eagle-import:.0603-C-NOSILK")
      (fields (field (name "MFR") "Yageo") (field (name "MPN") "RC0603FR-07665KL"))
      (libsource (lib "eagle-import") (part "R-US_0603-C-NOSILK"))
    )
    (comp (ref "R5")
      (value "10k")
      (footprint "eagle-import:.0603-C-NOSILK")
      (fields (field (name "MFR") "Yageo") (field (name "MPN") "RC0603FR-07665KL"))
      (libsource (lib "eagle-import") (part "R-US_0603-C-NOSILK"))
    )
    (comp (ref "R6")
      (value "100")
      (footprint "eagle-import:.0603-C-NOSILK")
      (fields (field (name "MFR") "Yageo") (field (name "MPN") "RC0603FR-07100RL"))
      (libsource (lib "eagle-import") (part "R-US_0603-C-NOSILK"))
    )
    (comp (ref "R7")
      (value "100")
      (footprint "eagle-import:.0603-C-NOSILK")
      (fields (field (name "MFR") "Yageo") (field (name "MPN") "RC0603FR-07100RL"))
      (libsource (lib "eagle-import") (part "R-US_0603-C-NOSILK"))
    )
    (comp (ref "R8")
      (value "NP")
      (footprint "eagle-import:.0603-C-NOSILK")
      (fields (field (name "MFR") "Yageo") (field (name "MPN") "RC0603FR-07665KL"))
      (libsource (lib "eagle-import") (part "R-US_0603-C-NOSILK"))
    )
    (comp (ref "R9")
      (value "NP")
      (footprint "eagle-import:.0603-C-NOSILK")
      (fields (field (name "MFR") "Yageo") (field (name "MPN") "RC0603FR-07665KL"))
      (libsource (lib "eagle-import") (part "R-US_0603-C-NOSILK"))
    )
    (comp (ref "R10")
      (value "NP")
      (footprint "eagle-import:.0603-C-NOSILK")
      (fields (field (name "MFR") "Yageo") (field (name "MPN") "RC0603FR-07665KL"))
      (libsource (lib "eagle-import") (part "R-US_0603-C-NOSILK"))
    )
    (comp (ref "R11")
      (value "10k")
      (footprint "eagle-import:.0603-C-NOSILK")
      (fields (field (name "MFR") "Yageo") (field (name "MPN") "RC0603FR-07665KL"))
      (libsource (lib "eagle-import") (part "R-US_0603-C-NOSILK"))
    )
    (comp (ref "R12")
      (value "665k")
      (footprint "eagle-import:.0603-C-NOSILK")
      (fields (field (name "MFR") "Yageo") (field (name "MPN") "RC0603FR-07665KL"))
      (libsource (lib "eagle-import") (part "R-US_0603-C-NOSILK"))
    )
    (comp (ref "R13")
      (value "665k")
      (footprint "eagle-import:.0603-C-NOSILK")
      (fields (field (name "MFR") "Yageo") (field (name "MPN") "RC0603FR-07665KL"))
      (libsource (lib "eagle-import") (part "R-US_0603-C-NOSILK"))
    )
    (comp (ref "R14")
      (value "NP")
      (footprint "eagle-import:.0603-C-NOSILK")
      (fields (field (name "MFR") "Yageo") (field (name "MPN") "RC0603FR-07665KL"))
      (libsource (lib "eagle-import") (part "R-US_0603-C-NOSILK"))
    )
    (comp (ref "R15")
      (value "NP")
      (footprint "eagle-import:.0603-C-NOSILK")
      (fields (field (name "MFR") "Yageo") (field (name "MPN") "RC0603FR-07665KL"))
      (libsource (lib "eagle-import") (part "R-US_0603-C-NOSILK"))
    )
    (comp (ref "R16")
      (value "NP")
      (footprint "eagle-import:.0603-C-NOSILK")
      (fields (field (name "MFR") "Yageo") (field (name "MPN") "RC0603FR-07665KL"))
      (libsource (lib "eagle-import") (part "R-US_0603-C-NOSILK"))
    )
    (comp (ref "R17")
      (value "10k")
      (footprint "eagle-import:.0603-C-NOSILK")
      (fields (field (name "MFR") "Yageo") (field (name "MPN") "RC0603FR-07665KL"))
      (libsource (lib "eagle-import") (part "R-US_0603-C-NOSILK"))
    )
    (comp (ref "R18")
      (value "10k")
      (footprint "eagle-import:.0603-C-NOSILK")
      (fields (field (name "MFR") "Yageo") (field (name "MPN") "RC0603FR-0710KL"))
      (libsource (lib "eagle-import") (part "R-US_0603-C-NOSILK"))
    )
    (comp (ref "R19")
      (value "330k")
      (footprint "eagle-import:.0603-C-NOSILK")
      (fields (field (name "MFR") "TE") (field (name "MPN") "CRGCQ0603F330K"))
      (libsource (lib "eagle-import") (part "R-US_0603-C-NOSILK"))
    )
    (comp (ref "R20")
      (value "330k")
      (footprint "eagle-import:.0603-C-NOSILK")
      (fields (field (name "MFR") "TE") (field (name "MPN") "CRGCQ0603F330K"))
      (libsource (lib "eagle-import") (part "R-US_0603-C-NOSILK"))
    )
    (comp (ref "R21")
      (value "1M")
      (footprint "eagle-import:.0603-C-NOSILK")
      (fields (field (name "MFR") "Yageo") (field (name "MPN") "RC0603FR-071ML"))
      (libsource (lib "eagle-import") (part "R-US_0603-C-NOSILK"))
    )
    (comp (ref "R22")
      (value "1M")
      (footprint "eagle-import:.0603-C-NOSILK")
      (fields (field (name "MFR") "Yageo") (field (name "MPN") "RC0603FR-071ML"))
      (libsource (lib "eagle-import") (part "R-US_0603-C-NOSILK"))
    )
    (comp (ref "R23")
      (value "2.7k")
      (footprint "eagle-import:.0603-C-NOSILK")
      (fields (field (name "MFR") "TE") (field (name "MPN") "CRGCQ0603F2K7"))
      (libsource (lib "eagle-import") (part "R-US_0603-C-NOSILK"))
    )
    (comp (ref "R24")
      (value "10k")
      (footprint "eagle-import:.0603-C-NOSILK")
      (fields (field (name "MFR") "Yageo") (field (name "MPN") "RC0603FR-0710KL"))
      (libsource (lib "eagle-import") (part "R-US_0603-C-NOSILK"))
    )
    (comp (ref "R25")
      (value "10k")
      (footprint "eagle-import:.0603-C-NOSILK")
      (fields (field (name "MFR") "Yageo") (field (name "MPN") "RC0603FR-0710KL"))
      (libsource (lib "eagle-import") (part "R-US_0603-C-NOSILK"))
    )
    (comp (ref "R26")
      (value "100k")
      (footprint "eagle-import:.0603-C-NOSILK")
      (fields (field (name "MFR") "Samsung") (field (name "MPN") "RC1005F6653CS"))
      (libsource (lib "eagle-import") (part "R-US_0603-C-NOSILK"))
    )
    (comp (ref "R27")
      (value "10k")
      (footprint "eagle-import:.0603-C-NOSILK")
      (fields (field (name "MFR") "Samsung") (field (name "MPN") "RC1005F6653CS"))
      (libsource (lib "eagle-import") (part "R-US_0603-C-NOSILK"))
    )
    (comp (ref "R28")
      (value "10k")
      (footprint "eagle-import:.0603-C-NOSILK")
      (fields (field (name "MFR") "Yageo") (field (name "MPN") "RC0603FR-0710KL"))
      (libsource (lib "eagle-import") (part "R-US_0603-C-NOSILK"))
    )
    (comp (ref "R29")
      (value "NP")
      (footprint "eagle-import:.0603-C-NOSILK")
      (fields (field (name "MFR") "Samsung") (field (name "MPN") "RC1005F6653CS"))
      (libsource (lib "eagle-import") (part "R-US_0603-C-NOSILK"))
    )
    (comp (ref "R30")
      (value "100m")
      (footprint "eagle-import:1206-C")
      (fields (field (name "MFR") "Stackpole") (field (name "MPN") "CSR1206FTR100"))
      (libsource (lib "eagle-import") (part "R-US_1206-C"))
    )
    (comp (ref "R31")
      (value "10k")
      (footprint "eagle-import:.0603-C-NOSILK")
      (fields (field (name "MFR") "Yageo") (field (name "MPN") "RC0603FR-0710KL"))
      (libsource (lib "eagle-import") (part "R-US_0603-C-NOSILK"))
    )
    (comp (ref "R32")
      (value "10k")
      (footprint "eagle-import:.0603-C-NOSILK")
      (fields (field (name "MFR") "Yageo") (field (name "MPN") "RC0603FR-0710KL"))
      (libsource (lib "eagle-import") (part "R-US_0603-C-NOSILK"))
    )
    (comp (ref "R33")
      (value "0")
      (footprint "eagle-import:.0603-C-NOSILK")
      (fields (field (name "MFR") "Yageo") (field (name "MPN") "RC0603JR-070RL"))
      (libsource (lib "eagle-import") (part "R-US_0603-C-NOSILK"))
    )
    (comp (ref "R34")
      (value "20k")
      (footprint "eagle-import:.0603-C-NOSILK")
      (fields (field (name "MFR") "Samsung") (field (name "MPN") "RR0816P-203-D"))
      (libsource (lib "eagle-import") (part "R-US_0603-C-NOSILK"))
    )
    (comp (ref "R35")
      (value "NP")
      (footprint "eagle-import:.0603-C-NOSILK")
      (fields (field (name "MFR") "Samsung") (field (name "MPN") "RC1005F6653CS"))
      (libsource (lib "eagle-import") (part "R-US_0603-C-NOSILK"))
    )
    (comp (ref "R36")
      (value "2.7k")
      (footprint "eagle-import:.0603-C-NOSILK")
      (fields (field (name "MFR") "TE") (field (name "MPN") "CRGCQ0603F2K7"))
      (libsource (lib "eagle-import") (part "R-US_0603-C-NOSILK"))
    )
    (comp (ref "R37")
      (value "10k")
      (footprint "eagle-import:.0603-C-NOSILK")
      (fields (field (name "MFR") "Yageo") (field (name "MPN") "RC0603FR-0710KL"))
      (libsource (lib "eagle-import") (part "R-US_0603-C-NOSILK"))
    )
    (comp (ref "R38")
      (value "10k")
      (footprint "eagle-import:.0603-C-NOSILK")
      (fields (field (name "MFR") "Yageo") (field (name "MPN") "RC0603FR-0710KL"))
      (libsource (lib "eagle-import") (part "R-US_0603-C-NOSILK"))
    )
    (comp (ref "R39")
      (value "2.7k")
      (footprint "eagle-import:.0603-C-NOSILK")
      (fields (field (name "MFR") "TE") (field (name "MPN") "CRGCQ0603F2K7"))
      (libsource (lib "eagle-import") (part "R-US_0603-C-NOSILK"))
    )
    (comp (ref "R44")
      (value "10k")
      (footprint "eagle-import:.0603-C-NOSILK")
      (fields (field (name "MFR") "Yageo") (field (name "MPN") "RC0603FR-0710KL"))
      (libsource (lib "eagle-import") (part "R-US_0603-C-NOSILK"))
    )
    (comp (ref "R57")
      (value "10k")
      (footprint "eagle-import:.0603-C-NOSILK")
      (fields (field (name "MFR") "Yageo") (field (name "MPN") "RC0603FR-07665KL"))
      (libsource (lib "eagle-import") (part "R-US_0603-C-NOSILK"))
    )
    (comp (ref "R67")
      (value "10k")
      (footprint "eagle-import:.0603-C-NOSILK")
      (fields (field (name "MFR") "Yageo") (field (name "MPN") "RC0603FR-07665KL"))
      (libsource (lib "eagle-import") (part "R-US_0603-C-NOSILK"))
    )
    (comp (ref "TP1")
      (value "TEST-POINT-LARGE-SQUARE")
      (footprint "eagle-import:1X01")
      (libsource (lib "eagle-import") (part "TEST-POINT-LARGE-SQUARE"))
    )
    (comp (ref "TP2")
      (value "TEST-POINT-LARGE-SQUARE")
      (footprint "eagle-import:1X01")
      (libsource (lib "eagle-import") (part "TEST-POINT-LARGE-SQUARE"))
    )
    (comp (ref "TP3")
      (value "TEST-POINT-LARGE-SQUARE")
      (footprint "eagle-import:1X01")
      (libsource (lib "eagle-import") (part "TEST-POINT-LARGE-SQUARE"))
    )
    (comp (ref "TP4")
      (value "TEST-POINT-LARGE-SQUARE")
      (footprint "eagle-import:1X01")
      (libsource (lib "eagle-import") (part "TEST-POINT-LARGE-SQUARE"))
    )
    (comp (ref "TP5")
      (value "TEST-POINT-LARGE-SQUARE")
      (footprint "eagle-import:1X01")
      (libsource (lib "eagle-import") (part "TEST-POINT-LARGE-SQUARE"))
    )
    (comp (ref "TP6")
      (value "TEST-POINT-LARGE-SQUARE")
      (footprint "eagle-import:1X01")
      (libsource (lib "eagle-import") (part "TEST-POINT-LARGE-SQUARE"))
    )
    (comp (ref "TP7")
      (value "TEST-POINT-LARGE-SQUARE")
      (footprint "eagle-import:1X01")
      (libsource (lib "eagle-import") (part "TEST-POINT-LARGE-SQUARE"))
    )
    (comp (ref "TP8")
      (value "TEST-POINT-LARGE-SQUARE")
      (footprint "eagle-import:1X01")
      (libsource (lib "eagle-import") (part "TEST-POINT-LARGE-SQUARE"))
    )
    (comp (ref "TP9")
      (value "TEST-POINT-LARGE-SQUARE")
      (footprint "eagle-import:1X01")
      (libsource (lib "eagle-import") (part "TEST-POINT-LARGE-SQUARE"))
    )
    (comp (ref "TP10")
      (value "TEST-POINT-LARGE-SQUARE")
      (footprint "eagle-import:1X01")
      (libsource (lib "eagle-import") (part "TEST-POINT-LARGE-SQUARE"))
    )
    (comp (ref "TP11")
      (value "TEST-POINT-LARGE-SQUARE")
      (footprint "eagle-import:1X01")
      (libsource (lib "eagle-import") (part "TEST-POINT-LARGE-SQUARE"))
    )
    (comp (ref "TP12")
      (value "TEST-POINT-LARGE-SQUARE")
      (footprint "eagle-import:1X01")
      (libsource (lib "eagle-import") (part "TEST-POINT-LARGE-SQUARE"))
    )
    (comp (ref "TP13")
      (value "TEST-POINT-LARGE-SQUARE")
      (footprint "eagle-import:1X01")
      (libsource (lib "eagle-import") (part "TEST-POINT-LARGE-SQUARE"))
    )
    (comp (ref "TP14")
      (value "TEST-POINT-LARGE-SQUARE")
      (footprint "eagle-import:1X01")
      (libsource (lib "eagle-import") (part "TEST-POINT-LARGE-SQUARE"))
    )
    (comp (ref "TP15")
      (value "TEST-POINT-LARGE-SQUARE")
      (footprint "eagle-import:1X01")
      (libsource (lib "eagle-import") (part "TEST-POINT-LARGE-SQUARE"))
    )
    (comp (ref "TP16")
      (value "TEST-POINT-LARGE-SQUARE")
      (footprint "eagle-import:1X01")
      (libsource (lib "eagle-import") (part "TEST-POINT-LARGE-SQUARE"))
    )
    (comp (ref "TP17")
      (value "TEST-POINT-LARGE-SQUARE")
      (footprint "eagle-import:1X01")
      (libsource (lib "eagle-import") (part "TEST-POINT-LARGE-SQUARE"))
    )
    (comp (ref "TP18")
      (value "TEST-POINT-LARGE-SQUARE")
      (footprint "eagle-import:1X01")
      (libsource (lib "eagle-import") (part "TEST-POINT-LARGE-SQUARE"))
    )
    (comp (ref "U1")
      (value "MAX7310ATE")
      (footprint "eagle-import:QFN65P400X400X80-17T210")
      (fields (field (name "MFR") "Maxim"))
      (libsource (lib "eagle-import") (part "MAX7310"))
    )
    (comp (ref "U2")
      (value "MIC842LYC5")
      (footprint "eagle-import:SC70-5")
      (fields (field (name "MFR") "Microchip") (field (name "MPN") "MIC842LYC5-TR"))
      (libsource (lib "eagle-import") (part "MIC842LYC5"))
    )
    (comp (ref "U3")
      (value "MIC842LYC5")
      (footprint "eagle-import:SC70-5")
      (libsource (lib "eagle-import") (part "MIC842LYC5"))
    )
    (comp (ref "U4")
      (value "MAX4211FETE")
      (footprint "eagle-import:QFN65P400X400X80-17T210")
      (fields (field (name "MFR") "Maxim"))
      (libsource (lib "eagle-import") (part "MAX4211"))
    )
    (comp (ref "U5")
      (value "TPS62111RSA")
      (footprint "eagle-import:S-PVQFN-16")
      (fields (field (name "MFR") "Texas Instruments"))
      (libsource (lib "eagle-import") (part "TPS6211X"))
    )
    (comp (ref "U6")
      (value "TS5A21366DCUR")
      (footprint "eagle-import:DCU0008A_N")
      (fields (field (name "COPYRIGHT") "Copyright (C) 2021 Ultra Librarian. All rights reserved."))
      (libsource (lib "eagle-import") (part "TS5A21366DCUR"))
    )
    (comp (ref "B1")
      (value "B-18650-LI-BATTERY")
      (footprint "eagle-import:18650")
      (fields (field (name "MFR") "Tenergy") (field (name "MPN") "MH48285"))
      (libsource (lib "eagle-import") (part "B-18650-LI-BATTERY"))
    )
    (comp (ref "B2")
      (value "B-18650-LI-BATTERY")
      (footprint "eagle-import:18650")
      (fields (field (name "MFR") "Tenergy") (field (name "MPN") "MH48285"))
      (libsource (lib "eagle-import") (part "B-18650-LI-BATTERY"))
    )
    (comp (ref "C15")
      (value "100n")
      (footprint "eagle-import:.0603-C-NOSILK")
      (fields (field (name "MFR") "Kemet") (field (name "MPN") "C0603C104M4RACTU"))
      (libsource (lib "eagle-import") (part "C-EU0603-C-NOSILK"))
    )
    (comp (ref "C16")
      (value "10n")
      (footprint "eagle-import:.0603-C-NOSILK")
      (fields (field (name "MFR") "Kemet") (field (name "MPN") "C0603C103M5RACTU"))
      (libsource (lib "eagle-import") (part "C-EU0603-C-NOSILK"))
    )
    (comp (ref "C17")
      (value "100n")
      (footprint "eagle-import:.0603-C-NOSILK")
      (fields (field (name "MFR") "Kemet") (field (name "MPN") "C0603C104M4RACTU"))
      (libsource (lib "eagle-import") (part "C-EU0603-C-NOSILK"))
    )
    (comp (ref "C18")
      (value "10n")
      (footprint "eagle-import:.0603-C-NOSILK")
      (fields (field (name "MFR") "Kemet") (field (name "MPN") "C0603C103M5RACTU"))
      (libsource (lib "eagle-import") (part "C-EU0603-C-NOSILK"))
    )
    (comp (ref "C19")
      (value "100n")
      (footprint "eagle-import:.0603-C-NOSILK")
      (fields (field (name "MFR") "Kemet") (field (name "MPN") "C0603C104M4RACTU"))
      (libsource (lib "eagle-import") (part "C-EU0603-C-NOSILK"))
    )
    (comp (ref "C20")
      (value "1n")
      (footprint "eagle-import:.0603-C-NOSILK")
      (fields (field (name "MFR") "Yageo") (field (name "MPN") "CC0603KRX7R9BB102"))
      (libsource (lib "eagle-import") (part "C-EU0603-C-NOSILK"))
    )
    (comp (ref "C21")
      (value "1n")
      (footprint "eagle-import:.0603-C-NOSILK")
      (fields (field (name "MFR") "Yageo") (field (name "MPN") "CC0603KRX7R9BB102"))
      (libsource (lib "eagle-import") (part "C-EU0603-C-NOSILK"))
    )
    (comp (ref "C22")
      (value "100n")
      (footprint "eagle-import:.0603-C-NOSILK")
      (fields (field (name "MFR") "Kemet") (field (name "MPN") "C0603C104M4RACTU"))
      (libsource (lib "eagle-import") (part "C-EU0603-C-NOSILK"))
    )
    (comp (ref "C23")
      (value "100n")
      (footprint "eagle-import:.0603-C-NOSILK")
      (fields (field (name "MFR") "Kemet") (field (name "MPN") "C0603C104M4RACTU"))
      (libsource (lib "eagle-import") (part "C-EU0603-C-NOSILK"))
    )
    (comp (ref "C24")
      (value "470n")
      (footprint "eagle-import:.0603-C-NOSILK")
      (fields (field (name "MFR") "Kemet") (field (name "MPN") "C0603C474K4PACTU"))
      (libsource (lib "eagle-import") (part "C-EU0603-C-NOSILK"))
    )
    (comp (ref "C25")
      (value "470n")
      (footprint "eagle-import:.0603-C-NOSILK")
      (fields (field (name "MFR") "Kemet") (field (name "MPN") "C0603C474K4PACTU"))
      (libsource (lib "eagle-import") (part "C-EU0603-C-NOSILK"))
    )
    (comp (ref "D5")
      (value "1N4151WS")
      (footprint "eagle-import:SOD323-R")
      (fields (field (name "MFR") "Vishay") (field (name "MPN") "1N4151WS-E3-08"))
      (libsource (lib "eagle-import") (part "DIODE-SOD323-R"))
    )
    (comp (ref "D6")
      (value "1N4151WS")
      (footprint "eagle-import:SOD323-R")
      (fields (field (name "MFR") "Vishay") (field (name "MPN") "1N4151WS-E3-08"))
      (libsource (lib "eagle-import") (part "DIODE-SOD323-R"))
    )
    (comp (ref "D14")
      (value "1N4151WS")
      (footprint "eagle-import:SOD323-R")
      (fields (field (name "MFR") "Vishay") (field (name "MPN") "1N4151WS-E3-08"))
      (libsource (lib "eagle-import") (part "DIODE-SOD323-R"))
    )
    (comp (ref "F1")
      (value "1206L500/12SLPR")
      (footprint "eagle-import:1206-C")
      (fields (field (name "MFR") "LittleFuse") (field (name "MPN") "NANOSMD350LR-C-2"))
      (libsource (lib "eagle-import") (part "GENERIC-FUSE-1206"))
    )
    (comp (ref "F3")
      (value "1206L150/12SLYR")
      (footprint "eagle-import:1206-C")
      (fields (field (name "MFR") "LittleFuse") (field (name "MPN") "NANOSMD350LR-C-2"))
      (libsource (lib "eagle-import") (part "GENERIC-FUSE-1206"))
    )
    (comp (ref "JP1")
      (value "PINHD-1X2")
      (footprint "eagle-import:1X02")
      (libsource (lib "eagle-import") (part "PINHD-1X2"))
    )
    (comp (ref "JP2")
      (value "PINHD-1X2")
      (footprint "eagle-import:1X02")
      (libsource (lib "eagle-import") (part "PINHD-1X2"))
    )
    (comp (ref "Q6")
      (value "PM45VEN")
      (footprint "eagle-import:SOT23-3")
      (fields (field (name "MFR") "Nexperia") (field (name "MPN") "PMV45EN2R"))
      (libsource (lib "eagle-import") (part "N-MOSFET-SOT-23-3"))
    )
    (comp (ref "Q7")
      (value "PM45VEN")
      (footprint "eagle-import:SOT23-3")
      (fields (field (name "MFR") "Nexperia") (field (name "MPN") "PMV45EN2R"))
      (libsource (lib "eagle-import") (part "N-MOSFET-SOT-23-3"))
    )
    (comp (ref "Q8")
      (value "PM45VEN")
      (footprint "eagle-import:SOT23-3")
      (fields (field (name "MFR") "Nexperia") (field (name "MPN") "PMV45EN2R"))
      (libsource (lib "eagle-import") (part "N-MOSFET-SOT-23-3"))
    )
    (comp (ref "Q9")
      (value "PM45VEN")
      (footprint "eagle-import:SOT23-3")
      (fields (field (name "MFR") "Nexperia") (field (name "MPN") "PMV45EN2R"))
      (libsource (lib "eagle-import") (part "N-MOSFET-SOT-23-3"))
    )
    (comp (ref "Q12")
      (value "Si7625DN")
      (footprint "eagle-import:POWERPAK-1212-8")
      (fields (field (name "MFR") "Vishay") (field (name "MPN") "SI7625DN-T1-GE3"))
      (libsource (lib "eagle-import") (part "Q-VISHAY-MOSFET-PCH-POWERPAK-1212-8"))
    )
    (comp (ref "Q13")
      (value "Si7625DN")
      (footprint "eagle-import:POWERPAK-1212-8")
      (fields (field (name "MFR") "Vishay") (field (name "MPN") "SI7625DN-T1-GE3"))
      (libsource (lib "eagle-import") (part "Q-VISHAY-MOSFET-PCH-POWERPAK-1212-8"))
    )
    (comp (ref "Q14")
      (value "NTR4101")
      (footprint "eagle-import:SOT23-3")
      (fields (field (name "MFR") "ON Semi") (field (name "MPN") "NTR4101PT1G"))
      (libsource (lib "eagle-import") (part "P-MOSFET-SOT23-3"))
    )
    (comp (ref "Q15")
      (value "NTR4101")
      (footprint "eagle-import:SOT23-3")
      (fields (field (name "MFR") "ON Semi") (field (name "MPN") "NTR4101PT1G"))
      (libsource (lib "eagle-import") (part "P-MOSFET-SOT23-3"))
    )
    (comp (ref "Q16")
      (value "Si7625DN")
      (footprint "eagle-import:POWERPAK-1212-8")
      (fields (field (name "MFR") "Vishay") (field (name "MPN") "SI7625DN-T1-GE3"))
      (libsource (lib "eagle-import") (part "Q-VISHAY-MOSFET-PCH-POWERPAK-1212-8"))
    )
    (comp (ref "Q17")
      (value "Si7625DN")
      (footprint "eagle-import:POWERPAK-1212-8")
      (fields (field (name "MFR") "Vishay") (field (name "MPN") "SI7625DN-T1-GE3"))
      (libsource (lib "eagle-import") (part "Q-VISHAY-MOSFET-PCH-POWERPAK-1212-8"))
    )
    (comp (ref "Q18")
      (value "Si7625DN")
      (footprint "eagle-import:POWERPAK-1212-8")
      (fields (field (name "MFR") "Vishay") (field (name "MPN") "SI7625DN-T1-GE3"))
      (libsource (lib "eagle-import") (part "Q-VISHAY-MOSFET-PCH-POWERPAK-1212-8"))
    )
    (comp (ref "Q19")
      (value "Si7625DN")
      (footprint "eagle-import:POWERPAK-1212-8")
      (fields (field (name "MFR") "Vishay") (field (name "MPN") "SI7625DN-T1-GE3"))
      (libsource (lib "eagle-import") (part "Q-VISHAY-MOSFET-PCH-POWERPAK-1212-8"))
    )
    (comp (ref "R45")
      (value "1k")
      (footprint "eagle-import:.0603-C-NOSILK")
      (fields (field (name "MPN") "311-1.0KGRCT-ND"))
      (libsource (lib "eagle-import") (part "R-US_0603-C-NOSILK"))
    )
    (comp (ref "R46")
      (value "100k")
      (footprint "eagle-import:.0603-C-NOSILK")
      (fields (field (name "MFR") "Yageo") (field (name "MPN") "RC0603FR-071ML"))
      (libsource (lib "eagle-import") (part "R-US_0603-C-NOSILK"))
    )
    (comp (ref "R47")
      (value "100k")
      (footprint "eagle-import:.0603-C-NOSILK")
      (fields (field (name "MFR") "Yageo") (field (name "MPN") "RC0603FR-0710KL"))
      (libsource (lib "eagle-import") (part "R-US_0603-C-NOSILK"))
    )
    (comp (ref "R48")
      (value "1k")
      (footprint "eagle-import:.0603-C-NOSILK")
      (fields (field (name "MPN") "311-1.0KGRCT-ND"))
      (libsource (lib "eagle-import") (part "R-US_0603-C-NOSILK"))
    )
    (comp (ref "R49")
      (value "100k")
      (footprint "eagle-import:.0603-C-NOSILK")
      (fields (field (name "MFR") "Yageo") (field (name "MPN") "RC0603FR-071ML"))
      (libsource (lib "eagle-import") (part "R-US_0603-C-NOSILK"))
    )
    (comp (ref "R50")
      (value "100k")
      (footprint "eagle-import:.0603-C-NOSILK")
      (fields (field (name "MFR") "Yageo") (field (name "MPN") "RC0603FR-0710KL"))
      (libsource (lib "eagle-import") (part "R-US_0603-C-NOSILK"))
    )
    (comp (ref "R51")
      (value "470")
      (footprint "eagle-import:.0603-C-NOSILK")
      (fields (field (name "MFR") "Yageo") (field (name "MPN") "RC0603JR-07470RL"))
      (libsource (lib "eagle-import") (part "R-US_0603-C-NOSILK"))
    )
    (comp (ref "R52")
      (value "1k")
      (footprint "eagle-import:.0603-C-NOSILK")
      (fields (field (name "MPN") "311-1.0KGRCT-ND"))
      (libsource (lib "eagle-import") (part "R-US_0603-C-NOSILK"))
    )
    (comp (ref "R53")
      (value "1k")
      (footprint "eagle-import:.0603-C-NOSILK")
      (fields (field (name "MPN") "311-1.0KGRCT-ND"))
      (libsource (lib "eagle-import") (part "R-US_0603-C-NOSILK"))
    )
    (comp (ref "R54")
      (value "470")
      (footprint "eagle-import:.0603-C-NOSILK")
      (fields (field (name "MFR") "Yageo") (field (name "MPN") "RC0603JR-07470RL"))
      (libsource (lib "eagle-import") (part "R-US_0603-C-NOSILK"))
    )
    (comp (ref "R55")
      (value "100k")
      (footprint "eagle-import:.0603-C-NOSILK")
      (fields (field (name "MFR") "Susumu") (field (name "MPN") "RR0816P-104-D"))
      (libsource (lib "eagle-import") (part "R-US_0603-C-NOSILK"))
    )
    (comp (ref "R58")
      (value "100k")
      (footprint "eagle-import:.0603-C-NOSILK")
      (fields (field (name "MFR") "Yageo") (field (name "MPN") "RC0603FR-071ML"))
      (libsource (lib "eagle-import") (part "R-US_0603-C-NOSILK"))
    )
    (comp (ref "R59")
      (value "100k")
      (footprint "eagle-import:.0603-C-NOSILK")
      (fields (field (name "MFR") "Yageo") (field (name "MPN") "RC0603FR-071ML"))
      (libsource (lib "eagle-import") (part "R-US_0603-C-NOSILK"))
    )
    (comp (ref "R60")
      (value "100k")
      (footprint "eagle-import:.0603-C-NOSILK")
      (fields (field (name "MFR") "Yageo") (field (name "MPN") "RC0603FR-071ML"))
      (libsource (lib "eagle-import") (part "R-US_0603-C-NOSILK"))
    )
    (comp (ref "R61")
      (value "100k")
      (footprint "eagle-import:.0603-C-NOSILK")
      (fields (field (name "MFR") "Yageo") (field (name "MPN") "RC0603FR-071ML"))
      (libsource (lib "eagle-import") (part "R-US_0603-C-NOSILK"))
    )
    (comp (ref "R62")
      (value "10m")
      (footprint "eagle-import:1206-C")
      (fields (field (name "MFR") "Riedon") (field (name "MPN") "CSR1206-0R01F1"))
      (libsource (lib "eagle-import") (part "R-US_1206-C"))
    )
    (comp (ref "R65")
      (value "10")
      (footprint "eagle-import:.0603-C-NOSILK")
      (fields (field (name "MFR") "Yageo") (field (name "MPN") "RC0603FR-0710RL"))
      (libsource (lib "eagle-import") (part "R-US_0603-C-NOSILK"))
    )
    (comp (ref "R66")
      (value "100")
      (footprint "eagle-import:.0603-C-NOSILK")
      (fields (field (name "MFR") "Yageo") (field (name "MPN") "RC0603FR-07100RL"))
      (libsource (lib "eagle-import") (part "R-US_0603-C-NOSILK"))
    )
    (comp (ref "R71")
      (value "10k")
      (footprint "eagle-import:.0603-C-NOSILK")
      (fields (field (name "MFR") "Yageo") (field (name "MPN") "RC0603FR-0710KL"))
      (libsource (lib "eagle-import") (part "R-US_0603-C-NOSILK"))
    )
    (comp (ref "R73")
      (value "10k")
      (footprint "eagle-import:.0603-C-NOSILK")
      (fields (field (name "MFR") "Yageo") (field (name "MPN") "RC0603FR-0710KL"))
      (libsource (lib "eagle-import") (part "R-US_0603-C-NOSILK"))
    )
    (comp (ref "R74")
      (value "100k")
      (footprint "eagle-import:.0603-C-NOSILK")
      (fields (field (name "MFR") "Susumu") (field (name "MPN") "RR0816P-104-D"))
      (libsource (lib "eagle-import") (part "R-US_0603-C-NOSILK"))
    )
    (comp (ref "TP23")
      (value "TEST-POINT-LARGE-SQUARE")
      (footprint "eagle-import:1X01")
      (libsource (lib "eagle-import") (part "TEST-POINT-LARGE-SQUARE"))
    )
    (comp (ref "TP26")
      (value "TEST-POINT-LARGE-SQUARE")
      (footprint "eagle-import:1X01")
      (libsource (lib "eagle-import") (part "TEST-POINT-LARGE-SQUARE"))
    )
    (comp (ref "TP27")
      (value "TEST-POINT-LARGE-SQUARE")
      (footprint "eagle-import:1X01")
      (libsource (lib "eagle-import") (part "TEST-POINT-LARGE-SQUARE"))
    )
    (comp (ref "TP28")
      (value "TEST-POINT-LARGE-SQUARE")
      (footprint "eagle-import:1X01")
      (libsource (lib "eagle-import") (part "TEST-POINT-LARGE-SQUARE"))
    )
    (comp (ref "TP29")
      (value "TEST-POINT-LARGE-SQUARE")
      (footprint "eagle-import:1X01")
      (libsource (lib "eagle-import") (part "TEST-POINT-LARGE-SQUARE"))
    )
    (comp (ref "TP30")
      (value "TEST-POINT-LARGE-SQUARE")
      (footprint "eagle-import:1X01")
      (libsource (lib "eagle-import") (part "TEST-POINT-LARGE-SQUARE"))
    )
    (comp (ref "TP31")
      (value "TEST-POINT-LARGE-SQUARE")
      (footprint "eagle-import:1X01")
      (libsource (lib "eagle-import") (part "TEST-POINT-LARGE-SQUARE"))
    )
    (comp (ref "TP32")
      (value "TEST-POINT-LARGE-SQUARE")
      (footprint "eagle-import:1X01")
      (libsource (lib "eagle-import") (part "TEST-POINT-LARGE-SQUARE"))
    )
    (comp (ref "TP33")
      (value "TEST-POINT-LARGE-SQUARE")
      (footprint "eagle-import:1X01")
      (libsource (lib "eagle-import") (part "TEST-POINT-LARGE-SQUARE"))
    )
    (comp (ref "TP35")
      (value "TEST-POINT-LARGE-SQUARE")
      (footprint "eagle-import:1X01")
      (libsource (lib "eagle-import") (part "TEST-POINT-LARGE-SQUARE"))
    )
    (comp (ref "TP36")
      (value "TEST-POINT-LARGE-SQUARE")
      (footprint "eagle-import:1X01")
      (libsource (lib "eagle-import") (part "TEST-POINT-LARGE-SQUARE"))
    )
    (comp (ref "TP38")
      (value "TEST-POINT-LARGE-SQUARE")
      (footprint "eagle-import:1X01")
      (libsource (lib "eagle-import") (part "TEST-POINT-LARGE-SQUARE"))
    )
    (comp (ref "TP39")
      (value "TEST-POINT-LARGE-SQUARE")
      (footprint "eagle-import:1X01")
      (libsource (lib "eagle-import") (part "TEST-POINT-LARGE-SQUARE"))
    )
    (comp (ref "TP40")
      (value "TEST-POINT-LARGE-SQUARE")
      (footprint "eagle-import:1X01")
      (libsource (lib "eagle-import") (part "TEST-POINT-LARGE-SQUARE"))
    )
    (comp (ref "TP41")
      (value "TEST-POINT-LARGE-SQUARE")
      (footprint "eagle-import:1X01")
      (libsource (lib "eagle-import") (part "TEST-POINT-LARGE-SQUARE"))
    )
    (comp (ref "TP42")
      (value "TEST-POINT-LARGE-SQUARE")
      (footprint "eagle-import:1X01")
      (libsource (lib "eagle-import") (part "TEST-POINT-LARGE-SQUARE"))
    )
    (comp (ref "TP43")
      (value "TEST-POINT-LARGE-SQUARE")
      (footprint "eagle-import:1X01")
      (libsource (lib "eagle-import") (part "TEST-POINT-LARGE-SQUARE"))
    )
    (comp (ref "TP44")
      (value "TEST-POINT-LARGE-SQUARE")
      (footprint "eagle-import:1X01")
      (libsource (lib "eagle-import") (part "TEST-POINT-LARGE-SQUARE"))
    )
    (comp (ref "TP45")
      (value "TEST-POINT-LARGE-SQUARE")
      (footprint "eagle-import:1X01")
      (libsource (lib "eagle-import") (part "TEST-POINT-LARGE-SQUARE"))
    )
    (comp (ref "TP46")
      (value "TEST-POINT-LARGE-SQUARE")
      (footprint "eagle-import:1X01")
      (libsource (lib "eagle-import") (part "TEST-POINT-LARGE-SQUARE"))
    )
    (comp (ref "TP48")
      (value "TEST-POINT-LARGE-SQUARE")
      (footprint "eagle-import:1X01")
      (libsource (lib "eagle-import") (part "TEST-POINT-LARGE-SQUARE"))
    )
    (comp (ref "U8")
      (value "S-8209AAA-T8T1U")
      (footprint "eagle-import:TSSOP8")
      (fields (field (name "MFR") "Ablic"))
      (libsource (lib "eagle-import") (part "S-8209AXXT"))
    )
    (comp (ref "U9")
      (value "S-8209AAA-T8T1U")
      (footprint "eagle-import:TSSOP8")
      (fields (field (name "MFR") "Ablic"))
      (libsource (lib "eagle-import") (part "S-8209AXXT"))
    )
    (comp (ref "U10")
      (value "LTC4412")
      (footprint "eagle-import:SOT23-6")
      (fields (field (name "MFR") "Analog Devices") (field (name "MPN") "LTC4412ES6#TRPBF"))
      (libsource (lib "eagle-import") (part "LTC4412"))
    )
    (comp (ref "U11")
      (value "LTC4412")
      (footprint "eagle-import:SOT23-6")
      (fields (field (name "MFR") "Analog Devices") (field (name "MPN") "LTC4412ES6#TRPBF"))
      (libsource (lib "eagle-import") (part "LTC4412"))
    )
    (comp (ref "U12")
      (value "MAX17205G")
      (footprint "eagle-import:21-0137I_T1433-2")
      (fields (field (name "MFR") "Maxim") (field (name "MPN") "MAX17205G+T"))
      (libsource (lib "eagle-import") (part "MAX17205G"))
    )
    (comp (ref "C10")
      (value "10u")
      (footprint "eagle-import:.0805-B-NOSILK")
      (fields (field (name "MFR") "Samsung") (field (name "MPN") "CL21A106KOFNNNE"))
      (libsource (lib "eagle-import") (part "C-EU0805-B-NOSILK"))
    )
    (comp (ref "C11")
      (value "10u")
      (footprint "eagle-import:.0805-B-NOSILK")
      (fields (field (name "MFR") "Samsung") (field (name "MPN") "CL21A106KOFNNNE"))
      (libsource (lib "eagle-import") (part "C-EU0805-B-NOSILK"))
    )
    (comp (ref "FIDUCIAL1")
      (value "FIDUCIAL-1.0X2.0")
      (footprint "eagle-import:FIDUCIAL-1.0X2.0")
      (libsource (lib "eagle-import") (part "FIDUCIAL-1.0X2.0"))
    )
    (comp (ref "FIDUCIAL2")
      (value "FIDUCIAL-1.0X2.0")
      (footprint "eagle-import:FIDUCIAL-1.0X2.0")
      (libsource (lib "eagle-import") (part "FIDUCIAL-1.0X2.0"))
    )
    (comp (ref "FIDUCIAL3")
      (value "FIDUCIAL-1.0X2.0")
      (footprint "eagle-import:FIDUCIAL-1.0X2.0")
      (libsource (lib "eagle-import") (part "FIDUCIAL-1.0X2.0"))
    )
    (comp (ref "J1")
      (value "J-SAMTEC-TFM-120-X1-XXX-D-RA")
      (footprint "eagle-import:J-SAMTEC-TFM-120-X1-XXX-D-RA")
      (fields (field (name "MFR") "Samtec") (field (name "MPN") "TFM-120-01-L-D-RA"))
      (libsource (lib "eagle-import") (part "J-SAMTEC-TFM-120-X1-XXX-D-RA"))
    )
    (comp (ref "SW1")
      (value "OMRON-D2F-5L3-LEFT")
      (footprint "eagle-import:D2F-L3-D-HORIZONTAL-L")
      (libsource (lib "eagle-import") (part "OMRON-D2F-L3-D-LEFT"))
    )
    (comp (ref "SW2")
      (value "OMRON-D2F-5L3-RIGHT")
      (footprint "eagle-import:D2F-L3-D-HORIZONTAL-R")
      (libsource (lib "eagle-import") (part "OMRON-D2F-L3-D-RIGHT"))
    )
    (comp (ref "SW3")
      (value "OMRON-D2F-5L3-LEFT")
      (footprint "eagle-import:D2F-L3-D-HORIZONTAL-L")
      (libsource (lib "eagle-import") (part "OMRON-D2F-L3-D-LEFT"))
    )
    (comp (ref "SW4")
      (value "OMRON-D2F-5L3-RIGHT")
      (footprint "eagle-import:D2F-L3-D-HORIZONTAL-R")
      (libsource (lib "eagle-import") (part "OMRON-D2F-L3-D-RIGHT"))
    )
    (comp (ref "TP25")
      (value "TEST-POINT-LARGE-SQUARE")
      (footprint "eagle-import:1X01")
      (libsource (lib "eagle-import") (part "TEST-POINT-LARGE-SQUARE"))
    )
    (comp (ref "TP57")
      (value "TEST-POINT-LARGE-SQUARE")
      (footprint "eagle-import:1X01")
      (libsource (lib "eagle-import") (part "TEST-POINT-LARGE-SQUARE"))
    )
    (comp (ref "U$1")
      (value "FLIGHMARKERNEW")
      (footprint "eagle-import:FLIGHTMARKER_NEW_BOARDS")
      (libsource (lib "eagle-import") (part "FLIGHMARKERNEW"))
    )
    (comp (ref "B3")
      (value "B-18650-LI-BATTERY")
      (footprint "eagle-import:18650")
      (fields (field (name "MFR") "Tenergy") (field (name "MPN") "MH48285"))
      (libsource (lib "eagle-import") (part "B-18650-LI-BATTERY"))
    )
    (comp (ref "B4")
      (value "B-18650-LI-BATTERY")
      (footprint "eagle-import:18650")
      (fields (field (name "MFR") "Tenergy") (field (name "MPN") "MH48285"))
      (libsource (lib "eagle-import") (part "B-18650-LI-BATTERY"))
    )
    (comp (ref "C26")
      (value "100n")
      (footprint "eagle-import:.0603-C-NOSILK")
      (fields (field (name "MFR") "Kemet") (field (name "MPN") "C0603C104M4RACTU"))
      (libsource (lib "eagle-import") (part "C-EU0603-C-NOSILK"))
    )
    (comp (ref "C27")
      (value "10n")
      (footprint "eagle-import:.0603-C-NOSILK")
      (fields (field (name "MFR") "Kemet") (field (name "MPN") "C0603C103M5RACTU"))
      (libsource (lib "eagle-import") (part "C-EU0603-C-NOSILK"))
    )
    (comp (ref "C28")
      (value "100n")
      (footprint "eagle-import:.0603-C-NOSILK")
      (fields (field (name "MFR") "Kemet") (field (name "MPN") "C0603C104M4RACTU"))
      (libsource (lib "eagle-import") (part "C-EU0603-C-NOSILK"))
    )
    (comp (ref "C29")
      (value "10n")
      (footprint "eagle-import:.0603-C-NOSILK")
      (fields (field (name "MFR") "Kemet") (field (name "MPN") "C0603C103M5RACTU"))
      (libsource (lib "eagle-import") (part "C-EU0603-C-NOSILK"))
    )
    (comp (ref "C30")
      (value "100n")
      (footprint "eagle-import:.0603-C-NOSILK")
      (fields (field (name "MFR") "Kemet") (field (name "MPN") "C0603C104M4RACTU"))
      (libsource (lib "eagle-import") (part "C-EU0603-C-NOSILK"))
    )
    (comp (ref "C31")
      (value "1n")
      (footprint "eagle-import:.0603-C-NOSILK")
      (fields (field (name "MFR") "Yageo") (field (name "MPN") "CC0603KRX7R9BB102"))
      (libsource (lib "eagle-import") (part "C-EU0603-C-NOSILK"))
    )
    (comp (ref "C32")
      (value "1n")
      (footprint "eagle-import:.0603-C-NOSILK")
      (fields (field (name "MFR") "Yageo") (field (name "MPN") "CC0603KRX7R9BB102"))
      (libsource (lib "eagle-import") (part "C-EU0603-C-NOSILK"))
    )
    (comp (ref "C33")
      (value "100n")
      (footprint "eagle-import:.0603-C-NOSILK")
      (fields (field (name "MFR") "Kemet") (field (name "MPN") "C0603C104M4RACTU"))
      (libsource (lib "eagle-import") (part "C-EU0603-C-NOSILK"))
    )
    (comp (ref "C34")
      (value "100n")
      (footprint "eagle-import:.0603-C-NOSILK")
      (fields (field (name "MFR") "Kemet") (field (name "MPN") "C0603C104M4RACTU"))
      (libsource (lib "eagle-import") (part "C-EU0603-C-NOSILK"))
    )
    (comp (ref "C35")
      (value "470n")
      (footprint "eagle-import:.0603-C-NOSILK")
      (fields (field (name "MFR") "Kemet") (field (name "MPN") "C0603C474K4PACTU"))
      (libsource (lib "eagle-import") (part "C-EU0603-C-NOSILK"))
    )
    (comp (ref "C36")
      (value "470n")
      (footprint "eagle-import:.0603-C-NOSILK")
      (fields (field (name "MFR") "Kemet") (field (name "MPN") "C0603C474K4PACTU"))
      (libsource (lib "eagle-import") (part "C-EU0603-C-NOSILK"))
    )
    (comp (ref "D7")
      (value "1N4151WS")
      (footprint "eagle-import:SOD323-R")
      (fields (field (name "MFR") "Vishay") (field (name "MPN") "1N4151WS-E3-08"))
      (libsource (lib "eagle-import") (part "DIODE-SOD323-R"))
    )
    (comp (ref "D8")
      (value "1N4151WS")
      (footprint "eagle-import:SOD323-R")
      (fields (field (name "MFR") "Vishay") (field (name "MPN") "1N4151WS-E3-08"))
      (libsource (lib "eagle-import") (part "DIODE-SOD323-R"))
    )
    (comp (ref "D13")
      (value "1N4151WS")
      (footprint "eagle-import:SOD323-R")
      (fields (field (name "MFR") "Vishay") (field (name "MPN") "1N4151WS-E3-08"))
      (libsource (lib "eagle-import") (part "DIODE-SOD323-R"))
    )
    (comp (ref "F2")
      (value "1206L500/12SLPR")
      (footprint "eagle-import:1206-C")
      (fields (field (name "MFR") "LittleFuse") (field (name "MPN") "NANOSMD350LR-C-2"))
      (libsource (lib "eagle-import") (part "GENERIC-FUSE-1206"))
    )
    (comp (ref "F4")
      (value "1206L150/12SLYR")
      (footprint "eagle-import:1206-C")
      (fields (field (name "MFR") "LittleFuse") (field (name "MPN") "NANOSMD350LR-C-2"))
      (libsource (lib "eagle-import") (part "GENERIC-FUSE-1206"))
    )
    (comp (ref "JP3")
      (value "PINHD-1X2")
      (footprint "eagle-import:1X02")
      (libsource (lib "eagle-import") (part "PINHD-1X2"))
    )
    (comp (ref "JP4")
      (value "PINHD-1X2")
      (footprint "eagle-import:1X02")
      (libsource (lib "eagle-import") (part "PINHD-1X2"))
    )
    (comp (ref "Q24")
      (value "PM45VEN")
      (footprint "eagle-import:SOT23-3")
      (fields (field (name "MFR") "Nexperia") (field (name "MPN") "PMV45EN2R"))
      (libsource (lib "eagle-import") (part "N-MOSFET-SOT-23-3"))
    )
    (comp (ref "Q25")
      (value "PM45VEN")
      (footprint "eagle-import:SOT23-3")
      (fields (field (name "MFR") "Nexperia") (field (name "MPN") "PMV45EN2R"))
      (libsource (lib "eagle-import") (part "N-MOSFET-SOT-23-3"))
    )
    (comp (ref "Q26")
      (value "PM45VEN")
      (footprint "eagle-import:SOT23-3")
      (fields (field (name "MFR") "Nexperia") (field (name "MPN") "PMV45EN2R"))
      (libsource (lib "eagle-import") (part "N-MOSFET-SOT-23-3"))
    )
    (comp (ref "Q27")
      (value "PM45VEN")
      (footprint "eagle-import:SOT23-3")
      (fields (field (name "MFR") "Nexperia") (field (name "MPN") "PMV45EN2R"))
      (libsource (lib "eagle-import") (part "N-MOSFET-SOT-23-3"))
    )
    (comp (ref "Q30")
      (value "Si7625DN")
      (footprint "eagle-import:POWERPAK-1212-8")
      (fields (field (name "MFR") "Vishay") (field (name "MPN") "SI7625DN-T1-GE3"))
      (libsource (lib "eagle-import") (part "Q-VISHAY-MOSFET-PCH-POWERPAK-1212-8"))
    )
    (comp (ref "Q31")
      (value "Si7625DN")
      (footprint "eagle-import:POWERPAK-1212-8")
      (fields (field (name "MFR") "Vishay") (field (name "MPN") "SI7625DN-T1-GE3"))
      (libsource (lib "eagle-import") (part "Q-VISHAY-MOSFET-PCH-POWERPAK-1212-8"))
    )
    (comp (ref "Q32")
      (value "NTR4101")
      (footprint "eagle-import:SOT23-3")
      (fields (field (name "MFR") "ON Semi") (field (name "MPN") "NTR4101PT1G"))
      (libsource (lib "eagle-import") (part "P-MOSFET-SOT23-3"))
    )
    (comp (ref "Q33")
      (value "NTR4101")
      (footprint "eagle-import:SOT23-3")
      (fields (field (name "MFR") "ON Semi") (field (name "MPN") "NTR4101PT1G"))
      (libsource (lib "eagle-import") (part "P-MOSFET-SOT23-3"))
    )
    (comp (ref "Q34")
      (value "Si7625DN")
      (footprint "eagle-import:POWERPAK-1212-8")
      (fields (field (name "MFR") "Vishay") (field (name "MPN") "SI7625DN-T1-GE3"))
      (libsource (lib "eagle-import") (part "Q-VISHAY-MOSFET-PCH-POWERPAK-1212-8"))
    )
    (comp (ref "Q35")
      (value "Si7625DN")
      (footprint "eagle-import:POWERPAK-1212-8")
      (fields (field (name "MFR") "Vishay") (field (name "MPN") "SI7625DN-T1-GE3"))
      (libsource (lib "eagle-import") (part "Q-VISHAY-MOSFET-PCH-POWERPAK-1212-8"))
    )
    (comp (ref "Q36")
      (value "Si7625DN")
      (footprint "eagle-import:POWERPAK-1212-8")
      (fields (field (name "MFR") "Vishay") (field (name "MPN") "SI7625DN-T1-GE3"))
      (libsource (lib "eagle-import") (part "Q-VISHAY-MOSFET-PCH-POWERPAK-1212-8"))
    )
    (comp (ref "Q37")
      (value "Si7625DN")
      (footprint "eagle-import:POWERPAK-1212-8")
      (fields (field (name "MFR") "Vishay") (field (name "MPN") "SI7625DN-T1-GE3"))
      (libsource (lib "eagle-import") (part "Q-VISHAY-MOSFET-PCH-POWERPAK-1212-8"))
    )
    (comp (ref "R56")
      (value "100k")
      (footprint "eagle-import:.0603-C-NOSILK")
      (fields (field (name "MFR") "Yageo") (field (name "MPN") "RR0816P-104-D"))
      (libsource (lib "eagle-import") (part "R-US_0603-C-NOSILK"))
    )
    (comp (ref "R75")
      (value "1k")
      (footprint "eagle-import:.0603-C-NOSILK")
      (fields (field (name "MFR") "Yageo") (field (name "MPN") "RC0603JR-071KL"))
      (libsource (lib "eagle-import") (part "R-US_0603-C-NOSILK"))
    )
    (comp (ref "R76")
      (value "100k")
      (footprint "eagle-import:.0603-C-NOSILK")
      (fields (field (name "MFR") "Yageo") (field (name "MPN") "RC0603FR-071ML"))
      (libsource (lib "eagle-import") (part "R-US_0603-C-NOSILK"))
    )
    (comp (ref "R77")
      (value "100k")
      (footprint "eagle-import:.0603-C-NOSILK")
      (fields (field (name "MFR") "Yageo") (field (name "MPN") "RC0603FR-0710KL"))
      (libsource (lib "eagle-import") (part "R-US_0603-C-NOSILK"))
    )
    (comp (ref "R78")
      (value "1k")
      (footprint "eagle-import:.0603-C-NOSILK")
      (fields (field (name "MFR") "Yageo") (field (name "MPN") "RC0603JR-071KL"))
      (libsource (lib "eagle-import") (part "R-US_0603-C-NOSILK"))
    )
    (comp (ref "R79")
      (value "100k")
      (footprint "eagle-import:.0603-C-NOSILK")
      (fields (field (name "MFR") "Yageo") (field (name "MPN") "RC0603FR-071ML"))
      (libsource (lib "eagle-import") (part "R-US_0603-C-NOSILK"))
    )
    (comp (ref "R80")
      (value "100k")
      (footprint "eagle-import:.0603-C-NOSILK")
      (fields (field (name "MFR") "Yageo") (field (name "MPN") "RC0603FR-0710KL"))
      (libsource (lib "eagle-import") (part "R-US_0603-C-NOSILK"))
    )
    (comp (ref "R81")
      (value "470")
      (footprint "eagle-import:.0603-C-NOSILK")
      (fields (field (name "MFR") "Yageo") (field (name "MPN") "RC0603JR-07470RL"))
      (libsource (lib "eagle-import") (part "R-US_0603-C-NOSILK"))
    )
    (comp (ref "R82")
      (value "1k")
      (footprint "eagle-import:.0603-C-NOSILK")
      (fields (field (name "MFR") "Yageo") (field (name "MPN") "RC0603JR-071KL"))
      (libsource (lib "eagle-import") (part "R-US_0603-C-NOSILK"))
    )
    (comp (ref "R83")
      (value "1k")
      (footprint "eagle-import:.0603-C-NOSILK")
      (fields (field (name "MFR") "Yageo") (field (name "MPN") "RC0603JR-071KL"))
      (libsource (lib "eagle-import") (part "R-US_0603-C-NOSILK"))
    )
    (comp (ref "R84")
      (value "470")
      (footprint "eagle-import:.0603-C-NOSILK")
      (fields (field (name "MFR") "Yageo") (field (name "MPN") "RC0603JR-07470RL"))
      (libsource (lib "eagle-import") (part "R-US_0603-C-NOSILK"))
    )
    (comp (ref "R88")
      (value "100k")
      (footprint "eagle-import:.0603-C-NOSILK")
      (fields (field (name "MFR") "Yageo") (field (name "MPN") "RC0603FR-071ML"))
      (libsource (lib "eagle-import") (part "R-US_0603-C-NOSILK"))
    )
    (comp (ref "R89")
      (value "100k")
      (footprint "eagle-import:.0603-C-NOSILK")
      (fields (field (name "MFR") "Yageo") (field (name "MPN") "RC0603FR-071ML"))
      (libsource (lib "eagle-import") (part "R-US_0603-C-NOSILK"))
    )
    (comp (ref "R90")
      (value "100k")
      (footprint "eagle-import:.0603-C-NOSILK")
      (fields (field (name "MFR") "Yageo") (field (name "MPN") "RC0603FR-071ML"))
      (libsource (lib "eagle-import") (part "R-US_0603-C-NOSILK"))
    )
    (comp (ref "R91")
      (value "100k")
      (footprint "eagle-import:.0603-C-NOSILK")
      (fields (field (name "MFR") "Yageo") (field (name "MPN") "RC0603FR-071ML"))
      (libsource (lib "eagle-import") (part "R-US_0603-C-NOSILK"))
    )
    (comp (ref "R92")
      (value "10m")
      (footprint "eagle-import:1206-C")
      (fields (field (name "MFR") "Riedon") (field (name "MPN") "CSR1206-0R01F1"))
      (libsource (lib "eagle-import") (part "R-US_1206-C"))
    )
    (comp (ref "R95")
      (value "10")
      (footprint "eagle-import:.0603-C-NOSILK")
      (fields (field (name "MFR") "Yageo") (field (name "MPN") "RC0603FR-0710RL"))
      (libsource (lib "eagle-import") (part "R-US_0603-C-NOSILK"))
    )
    (comp (ref "R96")
      (value "100")
      (footprint "eagle-import:.0603-C-NOSILK")
      (fields (field (name "MFR") "Yageo") (field (name "MPN") "RC0603FR-07100RL"))
      (libsource (lib "eagle-import") (part "R-US_0603-C-NOSILK"))
    )
    (comp (ref "R97")
      (value "100k")
      (footprint "eagle-import:.0603-C-NOSILK")
      (fields (field (name "MFR") "Yageo") (field (name "MPN") "RR0816P-104-D"))
      (libsource (lib "eagle-import") (part "R-US_0603-C-NOSILK"))
    )
    (comp (ref "R101")
      (value "10k")
      (footprint "eagle-import:.0603-C-NOSILK")
      (fields (field (name "MFR") "Yageo") (field (name "MPN") "RC0603FR-0710KL"))
      (libsource (lib "eagle-import") (part "R-US_0603-C-NOSILK"))
    )
    (comp (ref "R103")
      (value "10k")
      (footprint "eagle-import:.0603-C-NOSILK")
      (fields (field (name "MFR") "Yageo") (field (name "MPN") "RC0603FR-0710KL"))
      (libsource (lib "eagle-import") (part "R-US_0603-C-NOSILK"))
    )
    (comp (ref "TP24")
      (value "TEST-POINT-LARGE-SQUARE")
      (footprint "eagle-import:1X01")
      (libsource (lib "eagle-import") (part "TEST-POINT-LARGE-SQUARE"))
    )
    (comp (ref "TP49")
      (value "TEST-POINT-LARGE-SQUARE")
      (footprint "eagle-import:1X01")
      (libsource (lib "eagle-import") (part "TEST-POINT-LARGE-SQUARE"))
    )
    (comp (ref "TP50")
      (value "TEST-POINT-LARGE-SQUARE")
      (footprint "eagle-import:1X01")
      (libsource (lib "eagle-import") (part "TEST-POINT-LARGE-SQUARE"))
    )
    (comp (ref "TP51")
      (value "TEST-POINT-LARGE-SQUARE")
      (footprint "eagle-import:1X01")
      (libsource (lib "eagle-import") (part "TEST-POINT-LARGE-SQUARE"))
    )
    (comp (ref "TP52")
      (value "TEST-POINT-LARGE-SQUARE")
      (footprint "eagle-import:1X01")
      (libsource (lib "eagle-import") (part "TEST-POINT-LARGE-SQUARE"))
    )
    (comp (ref "TP53")
      (value "TEST-POINT-LARGE-SQUARE")
      (footprint "eagle-import:1X01")
      (libsource (lib "eagle-import") (part "TEST-POINT-LARGE-SQUARE"))
    )
    (comp (ref "TP54")
      (value "TEST-POINT-LARGE-SQUARE")
      (footprint "eagle-import:1X01")
      (libsource (lib "eagle-import") (part "TEST-POINT-LARGE-SQUARE"))
    )
    (comp (ref "TP55")
      (value "TEST-POINT-LARGE-SQUARE")
      (footprint "eagle-import:1X01")
      (libsource (lib "eagle-import") (part "TEST-POINT-LARGE-SQUARE"))
    )
    (comp (ref "TP56")
      (value "TEST-POINT-LARGE-SQUARE")
      (footprint "eagle-import:1X01")
      (libsource (lib "eagle-import") (part "TEST-POINT-LARGE-SQUARE"))
    )
    (comp (ref "TP58")
      (value "TEST-POINT-LARGE-SQUARE")
      (footprint "eagle-import:1X01")
      (libsource (lib "eagle-import") (part "TEST-POINT-LARGE-SQUARE"))
    )
    (comp (ref "TP59")
      (value "TEST-POINT-LARGE-SQUARE")
      (footprint "eagle-import:1X01")
      (libsource (lib "eagle-import") (part "TEST-POINT-LARGE-SQUARE"))
    )
    (comp (ref "TP61")
      (value "TEST-POINT-LARGE-SQUARE")
      (footprint "eagle-import:1X01")
      (libsource (lib "eagle-import") (part "TEST-POINT-LARGE-SQUARE"))
    )
    (comp (ref "TP62")
      (value "TEST-POINT-LARGE-SQUARE")
      (footprint "eagle-import:1X01")
      (libsource (lib "eagle-import") (part "TEST-POINT-LARGE-SQUARE"))
    )
    (comp (ref "TP63")
      (value "TEST-POINT-LARGE-SQUARE")
      (footprint "eagle-import:1X01")
      (libsource (lib "eagle-import") (part "TEST-POINT-LARGE-SQUARE"))
    )
    (comp (ref "TP64")
      (value "TEST-POINT-LARGE-SQUARE")
      (footprint "eagle-import:1X01")
      (libsource (lib "eagle-import") (part "TEST-POINT-LARGE-SQUARE"))
    )
    (comp (ref "TP65")
      (value "TEST-POINT-LARGE-SQUARE")
      (footprint "eagle-import:1X01")
      (libsource (lib "eagle-import") (part "TEST-POINT-LARGE-SQUARE"))
    )
    (comp (ref "TP66")
      (value "TEST-POINT-LARGE-SQUARE")
      (footprint "eagle-import:1X01")
      (libsource (lib "eagle-import") (part "TEST-POINT-LARGE-SQUARE"))
    )
    (comp (ref "TP67")
      (value "TEST-POINT-LARGE-SQUARE")
      (footprint "eagle-import:1X01")
      (libsource (lib "eagle-import") (part "TEST-POINT-LARGE-SQUARE"))
    )
    (comp (ref "TP68")
      (value "TEST-POINT-LARGE-SQUARE")
      (footprint "eagle-import:1X01")
      (libsource (lib "eagle-import") (part "TEST-POINT-LARGE-SQUARE"))
    )
    (comp (ref "TP69")
      (value "TEST-POINT-LARGE-SQUARE")
      (footprint "eagle-import:1X01")
      (libsource (lib "eagle-import") (part "TEST-POINT-LARGE-SQUARE"))
    )
    (comp (ref "TP71")
      (value "TEST-POINT-LARGE-SQUARE")
      (footprint "eagle-import:1X01")
      (libsource (lib "eagle-import") (part "TEST-POINT-LARGE-SQUARE"))
    )
    (comp (ref "U13")
      (value "S-8209AAA-T8T1U")
      (footprint "eagle-import:TSSOP8")
      (fields (field (name "MFR") "Ablic"))
      (libsource (lib "eagle-import") (part "S-8209AXXT"))
    )
    (comp (ref "U14")
      (value "S-8209AAA-T8T1U")
      (footprint "eagle-import:TSSOP8")
      (fields (field (name "MFR") "Ablic"))
      (libsource (lib "eagle-import") (part "S-8209AXXT"))
    )
    (comp (ref "U15")
      (value "LTC4412")
      (footprint "eagle-import:SOT23-6")
      (fields (field (name "MFR") "Analog Devices") (field (name "MPN") "LTC4412ES6#TRPBF"))
      (libsource (lib "eagle-import") (part "LTC4412"))
    )
    (comp (ref "U16")
      (value "LTC4412")
      (footprint "eagle-import:SOT23-6")
      (fields (field (name "MFR") "Analog Devices") (field (name "MPN") "LTC4412ES6#TRPBF"))
      (libsource (lib "eagle-import") (part "LTC4412"))
    )
    (comp (ref "U17")
      (value "MAX17205G")
      (footprint "eagle-import:21-0137I_T1433-2")
      (fields (field (name "MFR") "Maxim") (field (name "MPN") "MAX17205G+T"))
      (libsource (lib "eagle-import") (part "MAX17205G"))
    )
  )
  (nets
    (net (code "1") (name "3.3V") (class "Default")
      (node (ref "C44") (pin "2") (pinfunction "2_2") (pintype "passive"))
      (node (ref "C45") (pin "2") (pinfunction "2_2") (pintype "passive"))
      (node (ref "C48") (pin "2") (pinfunction "2_2") (pintype "passive"))
      (node (ref "C49") (pin "2") (pinfunction "2_2") (pintype "passive"))
      (node (ref "C50") (pin "2") (pinfunction "2_2") (pintype "passive"))
      (node (ref "C8") (pin "1") (pinfunction "1_1") (pintype "passive"))
      (node (ref "J2") (pin "1") (pinfunction "1_1") (pintype "passive"))
      (node (ref "J4") (pin "11") (pinfunction "VTARGET_11") (pintype "passive"))
      (node (ref "L1") (pin "2") (pinfunction "2_2") (pintype "passive"))
      (node (ref "R113") (pin "2") (pinfunction "2_2") (pintype "passive"))
      (node (ref "R114") (pin "2") (pinfunction "2_2") (pintype "passive"))
      (node (ref "R36") (pin "2") (pinfunction "2_2") (pintype "passive"))
      (node (ref "R63") (pin "2") (pinfunction "2_2") (pintype "passive"))
      (node (ref "R64") (pin "2") (pinfunction "2_2") (pintype "passive"))
      (node (ref "TP15") (pin "1") (pinfunction "1_1") (pintype "passive"))
      (node (ref "U20") (pin "3") (pinfunction "VCC_3") (pintype "power_in"))
      (node (ref "U21") (pin "1") (pinfunction "VBAT_1") (pintype "power_in"))
      (node (ref "U21") (pin "24") (pinfunction "VDD_24") (pintype "power_in"))
      (node (ref "U21") (pin "36") (pinfunction "VDDIO2_36") (pintype "power_in"))
      (node (ref "U21") (pin "48") (pinfunction "VDD_48") (pintype "power_in"))
      (node (ref "U21") (pin "9") (pinfunction "VDDA_9") (pintype "power_in"))
      (node (ref "U5") (pin "10") (pinfunction "FB_10") (pintype "input"))
    )
    (net (code "2") (name "AD0") (class "Default")
      (node (ref "R14") (pin "2") (pinfunction "2_2") (pintype "passive"))
      (node (ref "R15") (pin "1") (pinfunction "1_1") (pintype "passive"))
      (node (ref "R16") (pin "1") (pinfunction "1_1") (pintype "passive"))
      (node (ref "R17") (pin "2") (pinfunction "2_2") (pintype "passive"))
      (node (ref "U1") (pin "1") (pinfunction "AD0_1") (pintype "input"))
    )
    (net (code "3") (name "AD1") (class "Default")
      (node (ref "R10") (pin "1") (pinfunction "1_1") (pintype "passive"))
      (node (ref "R11") (pin "2") (pinfunction "2_2") (pintype "passive"))
      (node (ref "R8") (pin "2") (pinfunction "2_2") (pintype "passive"))
      (node (ref "R9") (pin "1") (pinfunction "1_1") (pintype "passive"))
      (node (ref "U1") (pin "2") (pinfunction "AD1_2") (pintype "input"))
    )
    (net (code "4") (name "AD2") (class "Default")
      (node (ref "R2") (pin "2") (pinfunction "2_2") (pintype "passive"))
      (node (ref "R3") (pin "1") (pinfunction "1_1") (pintype "passive"))
      (node (ref "R4") (pin "1") (pinfunction "1_1") (pintype "passive"))
      (node (ref "R5") (pin "2") (pinfunction "2_2") (pintype "passive"))
      (node (ref "U1") (pin "3") (pinfunction "AD2_3") (pintype "input"))
    )
    (net (code "5") (name "ALERTA-PK1") (class "Default")
      (node (ref "TP48") (pin "1") (pinfunction "1_1") (pintype "passive"))
      (node (ref "U12") (pin "8") (pinfunction "ALRT1_8") (pintype "output"))
      (node (ref "U21") (pin "41") (pinfunction "PB5_41") (pintype "bidirectional"))
    )
    (net (code "6") (name "ALERTA-PK2") (class "Default")
      (node (ref "TP71") (pin "1") (pinfunction "1_1") (pintype "passive"))
      (node (ref "U17") (pin "8") (pinfunction "ALRT1_8") (pintype "output"))
      (node (ref "U21") (pin "25") (pinfunction "PB12_25") (pintype "bidirectional"))
    )
    (net (code "7") (name "BOOT0") (class "Default")
      (node (ref "R110") (pin "2") (pinfunction "2_2") (pintype "passive"))
      (node (ref "TP78") (pin "1") (pinfunction "1_1") (pintype "passive"))
      (node (ref "U1") (pin "10") (pinfunction "IO5_10") (pintype "bidirectional"))
      (node (ref "U21") (pin "44") (pinfunction "PF11-BOOT0_44") (pintype "bidirectional"))
    )
    (net (code "8") (name "C3-UART-RX") (class "Default")
      (node (ref "J1") (pin "38") (pinfunction "38_38") (pintype "passive"))
      (node (ref "R67") (pin "2") (pinfunction "2_2") (pintype "passive"))
    )
    (net (code "9") (name "C3-UART-TX") (class "Default")
      (node (ref "J1") (pin "37") (pinfunction "37_37") (pintype "passive"))
      (node (ref "R57") (pin "2") (pinfunction "2_2") (pintype "passive"))
    )
    (net (code "10") (name "CAN1_H") (class "Default")
      (node (ref "J1") (pin "33") (pinfunction "33_33") (pintype "passive"))
      (node (ref "J1") (pin "34") (pinfunction "34_34") (pintype "passive"))
      (node (ref "U20") (pin "7") (pinfunction "CANH_7") (pintype "bidirectional"))
    )
    (net (code "11") (name "CAN1_L") (class "Default")
      (node (ref "J1") (pin "35") (pinfunction "35_35") (pintype "passive"))
      (node (ref "J1") (pin "36") (pinfunction "36_36") (pintype "passive"))
      (node (ref "U20") (pin "6") (pinfunction "CANL_6") (pintype "bidirectional"))
    )
    (net (code "12") (name "CAN_RX") (class "Default")
      (node (ref "U20") (pin "4") (pinfunction "RXD_4") (pintype "output"))
      (node (ref "U21") (pin "32") (pinfunction "PA11_32") (pintype "bidirectional"))
    )
    (net (code "13") (name "CAN_SHDN") (class "Default")
      (node (ref "U20") (pin "5") (pinfunction "SHDN_5") (pintype "input"))
      (node (ref "U21") (pin "31") (pinfunction "PA10_31") (pintype "bidirectional"))
    )
    (net (code "14") (name "CAN_TX") (class "Default")
      (node (ref "U20") (pin "1") (pinfunction "TXD_1") (pintype "input"))
      (node (ref "U21") (pin "33") (pinfunction "PA12_33") (pintype "bidirectional"))
    )
    (net (code "15") (name "CB-RESET") (class "Default")
      (node (ref "R31") (pin "2") (pinfunction "2_2") (pintype "passive"))
      (node (ref "TP14") (pin "1") (pinfunction "1_1") (pintype "passive"))
      (node (ref "U1") (pin "9") (pinfunction "IO4_9") (pintype "bidirectional"))
      (node (ref "U4") (pin "9") (pinfunction "CIN2-_9") (pintype "input"))
    )
    (net (code "16") (name "CB_CTRL") (class "Default")
      (node (ref "Q4") (pin "3") (pinfunction "G_3") (pintype "passive"))
      (node (ref "Q5") (pin "1") (pinfunction "G_1") (pintype "passive"))
      (node (ref "R37") (pin "1") (pinfunction "1_1") (pintype "passive"))
      (node (ref "TP9") (pin "1") (pinfunction "1_1") (pintype "passive"))
      (node (ref "U4") (pin "3") (pinfunction "LE_3") (pintype "input"))
      (node (ref "U4") (pin "4") (pinfunction "COUT1_4") (pintype "open_collector"))
      (node (ref "U4") (pin "6") (pinfunction "COUT2_6") (pintype "open_collector"))
    )
    (net (code "17") (name "CHARGE-DISABLE-PK1") (class "Default")
      (node (ref "Q7") (pin "1") (pinfunction "G_1") (pintype "passive"))
      (node (ref "R47") (pin "2") (pinfunction "2_2") (pintype "passive"))
      (node (ref "U21") (pin "14") (pinfunction "PA4_14") (pintype "bidirectional"))
    )
    (net (code "18") (name "CHARGE-DISABLE-PK2") (class "Default")
      (node (ref "Q25") (pin "1") (pinfunction "G_1") (pintype "passive"))
      (node (ref "R77") (pin "2") (pinfunction "2_2") (pintype "passive"))
      (node (ref "U21") (pin "18") (pinfunction "PB0_18") (pintype "bidirectional"))
    )
    (net (code "19") (name "CHARGE-STAT-OC-PK1") (class "Default")
      (node (ref "TP45") (pin "1") (pinfunction "1_1") (pintype "passive"))
      (node (ref "U11") (pin "4") (pinfunction "STAT_4") (pintype "open_collector"))
      (node (ref "U21") (pin "17") (pinfunction "PA7_17") (pintype "bidirectional"))
    )
    (net (code "20") (name "CHARGE-STAT-OC-PK2") (class "Default")
      (node (ref "TP68") (pin "1") (pinfunction "1_1") (pintype "passive"))
      (node (ref "U16") (pin "4") (pinfunction "STAT_4") (pintype "open_collector"))
      (node (ref "U21") (pin "21") (pinfunction "PB10_21") (pintype "bidirectional"))
    )
    (net (code "21") (name "CSP-PK1") (class "Default")
      (node (ref "B2") (pin "NEG-T") (pinfunction "NEG_NEG-T") (pintype "power_in"))
      (node (ref "C15") (pin "2") (pinfunction "2_2") (pintype "passive"))
      (node (ref "C16") (pin "2") (pinfunction "2_2") (pintype "passive"))
      (node (ref "C21") (pin "2") (pinfunction "2_2") (pintype "passive"))
      (node (ref "Q6") (pin "2") (pinfunction "S_2") (pintype "passive"))
      (node (ref "Q7") (pin "2") (pinfunction "S_2") (pintype "passive"))
      (node (ref "Q8") (pin "2") (pinfunction "S_2") (pintype "passive"))
      (node (ref "Q9") (pin "2") (pinfunction "S_2") (pintype "passive"))
      (node (ref "R47") (pin "1") (pinfunction "1_1") (pintype "passive"))
      (node (ref "R50") (pin "1") (pinfunction "1_1") (pintype "passive"))
      (node (ref "R61") (pin "2") (pinfunction "2_2") (pintype "passive"))
      (node (ref "R62") (pin "1") (pinfunction "1_1") (pintype "passive"))
      (node (ref "TP42") (pin "1") (pinfunction "1_1") (pintype "passive"))
      (node (ref "U12") (pin "2") (pinfunction "CSP_2") (pintype "passive"))
      (node (ref "U8") (pin "5") (pinfunction "VSS_5") (pintype "power_in"))
    )
    (net (code "22") (name "CSP-PK2") (class "Default")
      (node (ref "B4") (pin "NEG-T") (pinfunction "NEG_NEG-T") (pintype "power_in"))
      (node (ref "C26") (pin "2") (pinfunction "2_2") (pintype "passive"))
      (node (ref "C27") (pin "2") (pinfunction "2_2") (pintype "passive"))
      (node (ref "C32") (pin "2") (pinfunction "2_2") (pintype "passive"))
      (node (ref "Q24") (pin "2") (pinfunction "S_2") (pintype "passive"))
      (node (ref "Q25") (pin "2") (pinfunction "S_2") (pintype "passive"))
      (node (ref "Q26") (pin "2") (pinfunction "S_2") (pintype "passive"))
      (node (ref "Q27") (pin "2") (pinfunction "S_2") (pintype "passive"))
      (node (ref "R77") (pin "1") (pinfunction "1_1") (pintype "passive"))
      (node (ref "R80") (pin "1") (pinfunction "1_1") (pintype "passive"))
      (node (ref "R91") (pin "2") (pinfunction "2_2") (pintype "passive"))
      (node (ref "R92") (pin "1") (pinfunction "1_1") (pintype "passive"))
      (node (ref "TP65") (pin "1") (pinfunction "1_1") (pintype "passive"))
      (node (ref "U13") (pin "5") (pinfunction "VSS_5") (pintype "power_in"))
      (node (ref "U17") (pin "2") (pinfunction "CSP_2") (pintype "passive"))
    )
    (net (code "23") (name "DCHG-STAT-OC-PK1") (class "Default")
      (node (ref "TP35") (pin "1") (pinfunction "1_1") (pintype "passive"))
      (node (ref "U10") (pin "4") (pinfunction "STAT_4") (pintype "open_collector"))
      (node (ref "U21") (pin "11") (pinfunction "PA1_11") (pintype "bidirectional"))
    )
    (net (code "24") (name "DCHG-STAT-OC-PK2") (class "Default")
      (node (ref "TP58") (pin "1") (pinfunction "1_1") (pintype "passive"))
      (node (ref "U15") (pin "4") (pinfunction "STAT_4") (pintype "open_collector"))
      (node (ref "U21") (pin "22") (pinfunction "PB11_22") (pintype "bidirectional"))
    )
    (net (code "25") (name "DISCHARGE-DISABLE-PK1") (class "Default")
      (node (ref "Q9") (pin "1") (pinfunction "G_1") (pintype "passive"))
      (node (ref "R50") (pin "2") (pinfunction "2_2") (pintype "passive"))
      (node (ref "U21") (pin "15") (pinfunction "PA5_15") (pintype "bidirectional"))
    )
    (net (code "26") (name "DISCHARGE-DISABLE-PK2") (class "Default")
      (node (ref "Q27") (pin "1") (pinfunction "G_1") (pintype "passive"))
      (node (ref "R80") (pin "2") (pinfunction "2_2") (pintype "passive"))
      (node (ref "U21") (pin "19") (pinfunction "PB1_19") (pintype "bidirectional"))
    )
    (net (code "27") (name "GND") (class "Default")
      (node (ref "C1") (pin "2") (pinfunction "2_2") (pintype "passive"))
      (node (ref "C10") (pin "2") (pinfunction "2_2") (pintype "passive"))
      (node (ref "C11") (pin "2") (pinfunction "2_2") (pintype "passive"))
      (node (ref "C19") (pin "2") (pinfunction "2_2") (pintype "passive"))
      (node (ref "C2") (pin "2") (pinfunction "2_2") (pintype "passive"))
      (node (ref "C22") (pin "2") (pinfunction "2_2") (pintype "passive"))
      (node (ref "C23") (pin "2") (pinfunction "2_2") (pintype "passive"))
      (node (ref "C24") (pin "2") (pinfunction "2_2") (pintype "passive"))
      (node (ref "C25") (pin "2") (pinfunction "2_2") (pintype "passive"))
      (node (ref "C3") (pin "1") (pinfunction "1_1") (pintype "passive"))
      (node (ref "C30") (pin "2") (pinfunction "2_2") (pintype "passive"))
      (node (ref "C33") (pin "2") (pinfunction "2_2") (pintype "passive"))
      (node (ref "C34") (pin "2") (pinfunction "2_2") (pintype "passive"))
      (node (ref "C35") (pin "2") (pinfunction "2_2") (pintype "passive"))
      (node (ref "C36") (pin "2") (pinfunction "2_2") (pintype "passive"))
      (node (ref "C4") (pin "2") (pinfunction "2_2") (pintype "passive"))
      (node (ref "C44") (pin "1") (pinfunction "1_1") (pintype "passive"))
      (node (ref "C45") (pin "1") (pinfunction "1_1") (pintype "passive"))
      (node (ref "C46") (pin "2") (pinfunction "2_2") (pintype "passive"))
      (node (ref "C47") (pin "2") (pinfunction "2_2") (pintype "passive"))
      (node (ref "C48") (pin "1") (pinfunction "1_1") (pintype "passive"))
      (node (ref "C49") (pin "1") (pinfunction "1_1") (pintype "passive"))
      (node (ref "C5") (pin "2") (pinfunction "2_2") (pintype "passive"))
      (node (ref "C50") (pin "1") (pinfunction "1_1") (pintype "passive"))
      (node (ref "C6") (pin "2") (pinfunction "2_2") (pintype "passive"))
      (node (ref "C8") (pin "2") (pinfunction "2_2") (pintype "passive"))
      (node (ref "C9") (pin "1") (pinfunction "1_1") (pintype "passive"))
      (node (ref "D1") (pin "C") (pinfunction "C_C") (pintype "passive"))
      (node (ref "D10") (pin "C") (pinfunction "C_C") (pintype "passive"))
      (node (ref "D2") (pin "C") (pinfunction "C_C") (pintype "passive"))
      (node (ref "D3") (pin "C") (pinfunction "C_C") (pintype "passive"))
      (node (ref "J1") (pin "27") (pinfunction "27_27") (pintype "passive"))
      (node (ref "J1") (pin "28") (pinfunction "28_28") (pintype "passive"))
      (node (ref "J1") (pin "29") (pinfunction "29_29") (pintype "passive"))
      (node (ref "J1") (pin "30") (pinfunction "30_30") (pintype "passive"))
      (node (ref "J4") (pin "3") (pinfunction "GND_3") (pintype "passive"))
      (node (ref "J4") (pin "6") (pinfunction "GND_6") (pintype "passive"))
      (node (ref "J4") (pin "9") (pinfunction "GND_9") (pintype "passive"))
      (node (ref "J4") (pin "PAD1") (pinfunction "PAD_PAD1") (pintype "bidirectional"))
      (node (ref "J4") (pin "PAD2") (pinfunction "PAD_PAD2") (pintype "bidirectional"))
      (node (ref "JP1") (pin "2") (pinfunction "2_2") (pintype "passive"))
      (node (ref "JP15") (pin "1") (pinfunction "1_1") (pintype "passive"))
      (node (ref "JP17") (pin "1") (pinfunction "1_1") (pintype "passive"))
      (node (ref "JP2") (pin "2") (pinfunction "2_2") (pintype "passive"))
      (node (ref "JP3") (pin "2") (pinfunction "2_2") (pintype "passive"))
      (node (ref "JP4") (pin "2") (pinfunction "2_2") (pintype "passive"))
      (node (ref "Q2") (pin "2") (pinfunction "S_2") (pintype "passive"))
      (node (ref "Q20") (pin "2") (pinfunction "S_2") (pintype "passive"))
      (node (ref "Q21") (pin "2") (pinfunction "S_2") (pintype "passive"))
      (node (ref "Q44") (pin "2") (pinfunction "S_2") (pintype "passive"))
      (node (ref "Q5") (pin "2") (pinfunction "S_2") (pintype "passive"))
      (node (ref "R105") (pin "2") (pinfunction "2_2") (pintype "passive"))
      (node (ref "R106") (pin "2") (pinfunction "2_2") (pintype "passive"))
      (node (ref "R11") (pin "1") (pinfunction "1_1") (pintype "passive"))
      (node (ref "R110") (pin "1") (pinfunction "1_1") (pintype "passive"))
      (node (ref "R17") (pin "1") (pinfunction "1_1") (pintype "passive"))
      (node (ref "R24") (pin "1") (pinfunction "1_1") (pintype "passive"))
      (node (ref "R26") (pin "1") (pinfunction "1_1") (pintype "passive"))
      (node (ref "R29") (pin "1") (pinfunction "1_1") (pintype "passive"))
      (node (ref "R31") (pin "1") (pinfunction "1_1") (pintype "passive"))
      (node (ref "R35") (pin "1") (pinfunction "1_1") (pintype "passive"))
      (node (ref "R44") (pin "1") (pinfunction "1_1") (pintype "passive"))
      (node (ref "R5") (pin "1") (pinfunction "1_1") (pintype "passive"))
      (node (ref "R62") (pin "2") (pinfunction "2_2") (pintype "passive"))
      (node (ref "R68") (pin "2") (pinfunction "2_2") (pintype "passive"))
      (node (ref "R72") (pin "2") (pinfunction "2_2") (pintype "passive"))
      (node (ref "R92") (pin "2") (pinfunction "2_2") (pintype "passive"))
      (node (ref "SW1") (pin "C") (pinfunction "COM_C") (pintype "passive"))
      (node (ref "SW2") (pin "C") (pinfunction "COM_C") (pintype "passive"))
      (node (ref "TP43") (pin "1") (pinfunction "1_1") (pintype "passive"))
      (node (ref "TP66") (pin "1") (pinfunction "1_1") (pintype "passive"))
      (node (ref "U1") (pin "6") (pinfunction "GND_6") (pintype "power_in"))
      (node (ref "U1") (pin "EPAD") (pinfunction "GND_EPAD") (pintype "power_in"))
      (node (ref "U10") (pin "2") (pinfunction "GND_2") (pintype "power_in"))
      (node (ref "U10") (pin "3") (pinfunction "CTL_3") (pintype "input"))
      (node (ref "U11") (pin "2") (pinfunction "GND_2") (pintype "power_in"))
      (node (ref "U11") (pin "3") (pinfunction "CTL_3") (pintype "input"))
      (node (ref "U12") (pin "4") (pinfunction "CSN_4") (pintype "passive"))
      (node (ref "U12") (pin "EP") (pinfunction "CSN_EP") (pintype "passive"))
      (node (ref "U15") (pin "2") (pinfunction "GND_2") (pintype "power_in"))
      (node (ref "U15") (pin "3") (pinfunction "CTL_3") (pintype "input"))
      (node (ref "U16") (pin "2") (pinfunction "GND_2") (pintype "power_in"))
      (node (ref "U16") (pin "3") (pinfunction "CTL_3") (pintype "input"))
      (node (ref "U17") (pin "4") (pinfunction "CSN_4") (pintype "passive"))
      (node (ref "U17") (pin "EP") (pinfunction "CSN_EP") (pintype "passive"))
      (node (ref "U2") (pin "2") (pinfunction "GND_2") (pintype "power_in"))
      (node (ref "U20") (pin "2") (pinfunction "GND_2") (pintype "power_in"))
      (node (ref "U21") (pin "23") (pinfunction "VSS_23") (pintype "power_in"))
      (node (ref "U21") (pin "35") (pinfunction "VSS_35") (pintype "power_in"))
      (node (ref "U21") (pin "47") (pinfunction "VSS_47") (pintype "power_in"))
      (node (ref "U21") (pin "8") (pinfunction "VSSA_8") (pintype "power_in"))
      (node (ref "U3") (pin "2") (pinfunction "GND_2") (pintype "power_in"))
      (node (ref "U4") (pin "7") (pinfunction "GND_7") (pintype "power_in"))
      (node (ref "U4") (pin "EPAD") (pinfunction "GND_EPAD") (pintype "power_in"))
      (node (ref "U5") (pin "1") (pinfunction "GND_1") (pintype "power_in"))
      (node (ref "U5") (pin "11") (pinfunction "GND_11") (pintype "power_in"))
      (node (ref "U5") (pin "12") (pinfunction "GND_12") (pintype "power_in"))
      (node (ref "U5") (pin "16") (pinfunction "GND_16") (pintype "power_in"))
      (node (ref "U5") (pin "6") (pinfunction "LBO_6") (pintype "open_collector"))
      (node (ref "U5") (pin "7") (pinfunction "LBI_7") (pintype "input"))
      (node (ref "U5") (pin "9") (pinfunction "GND_9") (pintype "power_in"))
      (node (ref "U5") (pin "PAD") (pinfunction "GND_PAD") (pintype "power_in"))
      (node (ref "U6") (pin "4") (pinfunction "GND_4") (pintype "power_in"))
      (node (ref "X3") (pin "2") (pinfunction "SHIELD_2") (pintype "power_in"))
      (node (ref "X3") (pin "4") (pinfunction "SHIELD_4") (pintype "power_in"))
    )
    (net (code "28") (name "HEATER-ON-1") (class "Default")
      (node (ref "Q21") (pin "1") (pinfunction "G_1") (pintype "passive"))
      (node (ref "Q39") (pin "1") (pinfunction "G_1") (pintype "passive"))
      (node (ref "R105") (pin "1") (pinfunction "1_1") (pintype "passive"))
      (node (ref "U21") (pin "3") (pinfunction "PC14-OSC32_IN_3") (pintype "bidirectional"))
    )
    (net (code "29") (name "HEATER-ON-2") (class "Default")
      (node (ref "Q20") (pin "1") (pinfunction "G_1") (pintype "passive"))
      (node (ref "Q38") (pin "1") (pinfunction "G_1") (pintype "passive"))
      (node (ref "R106") (pin "1") (pinfunction "1_1") (pintype "passive"))
      (node (ref "U21") (pin "4") (pinfunction "PC15-OSC32_OUT_4") (pintype "bidirectional"))
    )
    (net (code "30") (name "I2C2_SCL") (class "Default")
      (node (ref "R63") (pin "1") (pinfunction "1_1") (pintype "passive"))
      (node (ref "TP19") (pin "1") (pinfunction "1_1") (pintype "passive"))
      (node (ref "U17") (pin "11") (pinfunction "SCL_11") (pintype "input"))
      (node (ref "U21") (pin "26") (pinfunction "PB13_26") (pintype "bidirectional"))
    )
    (net (code "31") (name "I2C2_SDA") (class "Default")
      (node (ref "R64") (pin "1") (pinfunction "1_1") (pintype "passive"))
      (node (ref "TP20") (pin "1") (pinfunction "1_1") (pintype "passive"))
      (node (ref "U17") (pin "12") (pinfunction "SDA_12") (pintype "bidirectional"))
      (node (ref "U21") (pin "27") (pinfunction "PB14_27") (pintype "bidirectional"))
    )
    (net (code "32") (name "INTERCELL-PK1") (class "Default")
      (node (ref "B1") (pin "NEG-T") (pinfunction "NEG_NEG-T") (pintype "power_in"))
      (node (ref "C17") (pin "2") (pinfunction "2_2") (pintype "passive"))
      (node (ref "C18") (pin "2") (pinfunction "2_2") (pintype "passive"))
      (node (ref "Q17") (pin "5") (pinfunction "D_5") (pintype "passive"))
      (node (ref "Q17") (pin "6") (pinfunction "D_6") (pintype "passive"))
      (node (ref "Q17") (pin "7") (pinfunction "D_7") (pintype "passive"))
      (node (ref "Q17") (pin "8") (pinfunction "D_8") (pintype "passive"))
      (node (ref "Q17") (pin "PAD") (pinfunction "D_PAD") (pintype "passive"))
      (node (ref "R46") (pin "2") (pinfunction "2_2") (pintype "passive"))
      (node (ref "R49") (pin "1") (pinfunction "1_1") (pintype "passive"))
      (node (ref "R51") (pin "2") (pinfunction "2_2") (pintype "passive"))
      (node (ref "R60") (pin "2") (pinfunction "2_2") (pintype "passive"))
      (node (ref "R66") (pin "1") (pinfunction "1_1") (pintype "passive"))
      (node (ref "TP40") (pin "1") (pinfunction "1_1") (pintype "passive"))
      (node (ref "U9") (pin "5") (pinfunction "VSS_5") (pintype "power_in"))
    )
    (net (code "33") (name "INTERCELL-PK2") (class "Default")
      (node (ref "B3") (pin "NEG-T") (pinfunction "NEG_NEG-T") (pintype "power_in"))
      (node (ref "C28") (pin "2") (pinfunction "2_2") (pintype "passive"))
      (node (ref "C29") (pin "2") (pinfunction "2_2") (pintype "passive"))
      (node (ref "Q35") (pin "5") (pinfunction "D_5") (pintype "passive"))
      (node (ref "Q35") (pin "6") (pinfunction "D_6") (pintype "passive"))
      (node (ref "Q35") (pin "7") (pinfunction "D_7") (pintype "passive"))
      (node (ref "Q35") (pin "8") (pinfunction "D_8") (pintype "passive"))
      (node (ref "Q35") (pin "PAD") (pinfunction "D_PAD") (pintype "passive"))
      (node (ref "R76") (pin "2") (pinfunction "2_2") (pintype "passive"))
      (node (ref "R79") (pin "1") (pinfunction "1_1") (pintype "passive"))
      (node (ref "R81") (pin "2") (pinfunction "2_2") (pintype "passive"))
      (node (ref "R90") (pin "2") (pinfunction "2_2") (pintype "passive"))
      (node (ref "R96") (pin "1") (pinfunction "1_1") (pintype "passive"))
      (node (ref "TP63") (pin "1") (pinfunction "1_1") (pintype "passive"))
      (node (ref "U14") (pin "5") (pinfunction "VSS_5") (pintype "power_in"))
    )
    (net (code "34") (name "MOARPWR") (class "Default")
      (node (ref "Q44") (pin "1") (pinfunction "G_1") (pintype "passive"))
      (node (ref "R44") (pin "2") (pinfunction "2_2") (pintype "passive"))
      (node (ref "U21") (pin "28") (pinfunction "PB15_28") (pintype "bidirectional"))
    )
    (net (code "35") (name "NRESET") (class "Default")
      (node (ref "J4") (pin "10") (pinfunction "NRST_10") (pintype "passive"))
      (node (ref "U21") (pin "7") (pinfunction "NRST_7") (pintype "bidirectional"))
    )
    (net (code "36") (name "Net-(B1-POS)") (class "Default")
      (node (ref "B1") (pin "POS-T") (pinfunction "POS_POS-T") (pintype "power_in"))
      (node (ref "Q14") (pin "2") (pinfunction "S_2") (pintype "passive"))
      (node (ref "Q16") (pin "1") (pinfunction "S_1") (pintype "passive"))
      (node (ref "Q16") (pin "2") (pinfunction "S_2") (pintype "passive"))
      (node (ref "Q16") (pin "3") (pinfunction "S_3") (pintype "passive"))
      (node (ref "R58") (pin "2") (pinfunction "2_2") (pintype "passive"))
      (node (ref "TP39") (pin "1") (pinfunction "1_1") (pintype "passive"))
    )
    (net (code "37") (name "Net-(B2-POS)") (class "Default")
      (node (ref "B2") (pin "POS-T") (pinfunction "POS_POS-T") (pintype "power_in"))
      (node (ref "Q15") (pin "2") (pinfunction "S_2") (pintype "passive"))
      (node (ref "Q17") (pin "1") (pinfunction "S_1") (pintype "passive"))
      (node (ref "Q17") (pin "2") (pinfunction "S_2") (pintype "passive"))
      (node (ref "Q17") (pin "3") (pinfunction "S_3") (pintype "passive"))
      (node (ref "R59") (pin "1") (pinfunction "1_1") (pintype "passive"))
      (node (ref "TP41") (pin "1") (pinfunction "1_1") (pintype "passive"))
    )
    (net (code "38") (name "Net-(B3-POS)") (class "Default")
      (node (ref "B3") (pin "POS-T") (pinfunction "POS_POS-T") (pintype "power_in"))
      (node (ref "Q32") (pin "2") (pinfunction "S_2") (pintype "passive"))
      (node (ref "Q34") (pin "1") (pinfunction "S_1") (pintype "passive"))
      (node (ref "Q34") (pin "2") (pinfunction "S_2") (pintype "passive"))
      (node (ref "Q34") (pin "3") (pinfunction "S_3") (pintype "passive"))
      (node (ref "R88") (pin "2") (pinfunction "2_2") (pintype "passive"))
      (node (ref "TP62") (pin "1") (pinfunction "1_1") (pintype "passive"))
    )
    (net (code "39") (name "Net-(B4-POS)") (class "Default")
      (node (ref "B4") (pin "POS-T") (pinfunction "POS_POS-T") (pintype "power_in"))
      (node (ref "Q33") (pin "2") (pinfunction "S_2") (pintype "passive"))
      (node (ref "Q35") (pin "1") (pinfunction "S_1") (pintype "passive"))
      (node (ref "Q35") (pin "2") (pinfunction "S_2") (pintype "passive"))
      (node (ref "Q35") (pin "3") (pinfunction "S_3") (pintype "passive"))
      (node (ref "R89") (pin "1") (pinfunction "1_1") (pintype "passive"))
      (node (ref "TP64") (pin "1") (pinfunction "1_1") (pintype "passive"))
    )
    (net (code "40") (name "Net-(C7-Pad1)") (class "Default")
      (node (ref "C7") (pin "1") (pinfunction "1_1") (pintype "passive"))
      (node (ref "R26") (pin "2") (pinfunction "2_2") (pintype "passive"))
      (node (ref "R27") (pin "2") (pinfunction "2_2") (pintype "passive"))
    )
    (net (code "41") (name "Net-(D1-PadA)") (class "Default")
      (node (ref "D1") (pin "A") (pinfunction "A_A") (pintype "passive"))
      (node (ref "R23") (pin "1") (pinfunction "1_1") (pintype "passive"))
    )
    (net (code "42") (name "Net-(D2-PadA)") (class "Default")
      (node (ref "D2") (pin "A") (pinfunction "A_A") (pintype "passive"))
      (node (ref "R36") (pin "1") (pinfunction "1_1") (pintype "passive"))
    )
    (net (code "43") (name "Net-(D3-PadA)") (class "Default")
      (node (ref "D3") (pin "A") (pinfunction "A_A") (pintype "passive"))
      (node (ref "R39") (pin "1") (pinfunction "1_1") (pintype "passive"))
    )
    (net (code "44") (name "Net-(D10-PadA)") (class "Default")
      (node (ref "D10") (pin "A") (pinfunction "A_A") (pintype "passive"))
      (node (ref "R111") (pin "1") (pinfunction "1_1") (pintype "passive"))
    )
    (net (code "45") (name "Net-(F1-P$1)") (class "Default")
      (node (ref "F1") (pin "1") (pinfunction "P$1_1") (pintype "passive"))
      (node (ref "Q12") (pin "1") (pinfunction "S_1") (pintype "passive"))
      (node (ref "Q12") (pin "2") (pinfunction "S_2") (pintype "passive"))
      (node (ref "Q12") (pin "3") (pinfunction "S_3") (pintype "passive"))
      (node (ref "R74") (pin "1") (pinfunction "1_1") (pintype "passive"))
    )
    (net (code "46") (name "Net-(F2-P$1)") (class "Default")
      (node (ref "F2") (pin "1") (pinfunction "P$1_1") (pintype "passive"))
      (node (ref "Q30") (pin "1") (pinfunction "S_1") (pintype "passive"))
      (node (ref "Q30") (pin "2") (pinfunction "S_2") (pintype "passive"))
      (node (ref "Q30") (pin "3") (pinfunction "S_3") (pintype "passive"))
      (node (ref "R56") (pin "2") (pinfunction "2_2") (pintype "passive"))
    )
    (net (code "47") (name "Net-(F3-P$1)") (class "Default")
      (node (ref "F3") (pin "1") (pinfunction "P$1_1") (pintype "passive"))
      (node (ref "Q19") (pin "5") (pinfunction "D_5") (pintype "passive"))
      (node (ref "Q19") (pin "6") (pinfunction "D_6") (pintype "passive"))
      (node (ref "Q19") (pin "7") (pinfunction "D_7") (pintype "passive"))
      (node (ref "Q19") (pin "8") (pinfunction "D_8") (pintype "passive"))
      (node (ref "Q19") (pin "PAD") (pinfunction "D_PAD") (pintype "passive"))
    )
    (net (code "48") (name "Net-(F4-P$1)") (class "Default")
      (node (ref "F4") (pin "1") (pinfunction "P$1_1") (pintype "passive"))
      (node (ref "Q37") (pin "5") (pinfunction "D_5") (pintype "passive"))
      (node (ref "Q37") (pin "6") (pinfunction "D_6") (pintype "passive"))
      (node (ref "Q37") (pin "7") (pinfunction "D_7") (pintype "passive"))
      (node (ref "Q37") (pin "8") (pinfunction "D_8") (pintype "passive"))
      (node (ref "Q37") (pin "PAD") (pinfunction "D_PAD") (pintype "passive"))
    )
    (net (code "49") (name "Net-(J4-DEBUG-0)") (class "Default")
      (node (ref "J4") (pin "17") (pinfunction "DEBUG-0_17") (pintype "passive"))
      (node (ref "TP79") (pin "1") (pinfunction "1_1") (pintype "passive"))
    )
    (net (code "50") (name "Net-(J4-DEBUG-1)") (class "Default")
      (node (ref "J4") (pin "18") (pinfunction "DEBUG-1_18") (pintype "passive"))
      (node (ref "TP80") (pin "1") (pinfunction "1_1") (pintype "passive"))
    )
    (net (code "51") (name "Net-(J4-DEBUG-2)") (class "Default")
      (node (ref "J4") (pin "19") (pinfunction "DEBUG-2_19") (pintype "passive"))
      (node (ref "TP81") (pin "1") (pinfunction "1_1") (pintype "passive"))
    )
    (net (code "52") (name "Net-(J4-DEBUG-3)") (class "Default")
      (node (ref "J4") (pin "20") (pinfunction "DEBUG-3_20") (pintype "passive"))
      (node (ref "TP82") (pin "1") (pinfunction "1_1") (pintype "passive"))
    )
    (net (code "53") (name "Net-(J4-SWO)") (class "Default")
      (node (ref "J4") (pin "16") (pinfunction "SWO_16") (pintype "passive"))
      (node (ref "TP83") (pin "1") (pinfunction "1_1") (pintype "passive"))
    )
    (net (code "54") (name "Net-(L1-Pad1)") (class "Default")
      (node (ref "L1") (pin "1") (pinfunction "1_1") (pintype "passive"))
      (node (ref "U5") (pin "14") (pinfunction "SW_14") (pintype "output"))
      (node (ref "U5") (pin "15") (pinfunction "SW_15") (pintype "output"))
    )
    (net (code "55") (name "Net-(Q1A-G)") (class "Default")
      (node (ref "Q1") (pin "1") (pinfunction "G_1") (pintype "passive"))
      (node (ref "R13") (pin "2") (pinfunction "2_2") (pintype "passive"))
    )
    (net (code "56") (name "Net-(Q1A-S)") (class "Default")
      (node (ref "Q1") (pin "5") (pinfunction "S_5") (pintype "passive"))
      (node (ref "R7") (pin "2") (pinfunction "2_2") (pintype "passive"))
    )
    (net (code "57") (name "Net-(Q1B-G)") (class "Default")
      (node (ref "Q1") (pin "3") (pinfunction "G_3") (pintype "passive"))
      (node (ref "R12") (pin "2") (pinfunction "2_2") (pintype "passive"))
    )
    (net (code "58") (name "Net-(Q1B-S)") (class "Default")
      (node (ref "Q1") (pin "2") (pinfunction "S_2") (pintype "passive"))
      (node (ref "R6") (pin "2") (pinfunction "2_2") (pintype "passive"))
    )
    (net (code "59") (name "Net-(Q2-D)") (class "Default")
      (node (ref "Q2") (pin "3") (pinfunction "D_3") (pintype "passive"))
      (node (ref "Q3") (pin "3") (pinfunction "G_3") (pintype "passive"))
      (node (ref "R25") (pin "1") (pinfunction "1_1") (pintype "passive"))
    )
    (net (code "60") (name "Net-(Q4-S)") (class "Default")
      (node (ref "Q4") (pin "4") (pinfunction "S_4") (pintype "passive"))
      (node (ref "R30") (pin "2") (pinfunction "2_2") (pintype "passive"))
      (node (ref "R37") (pin "2") (pinfunction "2_2") (pintype "passive"))
      (node (ref "U4") (pin "15") (pinfunction "RS-_15") (pintype "passive"))
    )
    (net (code "61") (name "Net-(Q6-D)") (class "Default")
      (node (ref "Q6") (pin "3") (pinfunction "D_3") (pintype "passive"))
      (node (ref "R45") (pin "1") (pinfunction "1_1") (pintype "passive"))
    )
    (net (code "62") (name "Net-(Q6-G)") (class "Default")
      (node (ref "D14") (pin "A") (pinfunction "A_A") (pintype "passive"))
      (node (ref "Q6") (pin "1") (pinfunction "G_1") (pintype "passive"))
      (node (ref "Q7") (pin "3") (pinfunction "D_3") (pintype "passive"))
      (node (ref "R46") (pin "1") (pinfunction "1_1") (pintype "passive"))
      (node (ref "TP27") (pin "1") (pinfunction "1_1") (pintype "passive"))
    )
    (net (code "63") (name "Net-(Q8-D)") (class "Default")
      (node (ref "Q8") (pin "3") (pinfunction "D_3") (pintype "passive"))
      (node (ref "R48") (pin "1") (pinfunction "1_1") (pintype "passive"))
    )
    (net (code "64") (name "Net-(Q8-G)") (class "Default")
      (node (ref "Q8") (pin "1") (pinfunction "G_1") (pintype "passive"))
      (node (ref "Q9") (pin "3") (pinfunction "D_3") (pintype "passive"))
      (node (ref "R49") (pin "2") (pinfunction "2_2") (pintype "passive"))
      (node (ref "TP29") (pin "1") (pinfunction "1_1") (pintype "passive"))
    )
    (net (code "65") (name "Net-(Q13-G)") (class "Default")
      (node (ref "Q13") (pin "4") (pinfunction "G_4") (pintype "passive"))
      (node (ref "U10") (pin "5") (pinfunction "GATE_5") (pintype "output"))
    )
    (net (code "66") (name "Net-(Q14-D)") (class "Default")
      (node (ref "Q14") (pin "3") (pinfunction "D_3") (pintype "passive"))
      (node (ref "Q16") (pin "4") (pinfunction "G_4") (pintype "passive"))
      (node (ref "R60") (pin "1") (pinfunction "1_1") (pintype "passive"))
    )
    (net (code "67") (name "Net-(Q14-G)") (class "Default")
      (node (ref "D5") (pin "A") (pinfunction "A_A") (pintype "passive"))
      (node (ref "Q14") (pin "1") (pinfunction "G_1") (pintype "passive"))
      (node (ref "R58") (pin "1") (pinfunction "1_1") (pintype "passive"))
    )
    (net (code "68") (name "Net-(Q15-D)") (class "Default")
      (node (ref "Q15") (pin "3") (pinfunction "D_3") (pintype "passive"))
      (node (ref "Q17") (pin "4") (pinfunction "G_4") (pintype "passive"))
      (node (ref "R61") (pin "1") (pinfunction "1_1") (pintype "passive"))
    )
    (net (code "69") (name "Net-(Q15-G)") (class "Default")
      (node (ref "D6") (pin "A") (pinfunction "A_A") (pintype "passive"))
      (node (ref "Q15") (pin "1") (pinfunction "G_1") (pintype "passive"))
      (node (ref "R59") (pin "2") (pinfunction "2_2") (pintype "passive"))
    )
    (net (code "70") (name "Net-(Q18-G)") (class "Default")
      (node (ref "Q18") (pin "4") (pinfunction "G_4") (pintype "passive"))
      (node (ref "U11") (pin "5") (pinfunction "GATE_5") (pintype "output"))
    )
    (net (code "71") (name "Net-(Q20-D)") (class "Default")
      (node (ref "Q20") (pin "3") (pinfunction "D_3") (pintype "passive"))
      (node (ref "Q39") (pin "2") (pinfunction "S_2") (pintype "passive"))
    )
    (net (code "72") (name "Net-(Q21-D)") (class "Default")
      (node (ref "Q21") (pin "3") (pinfunction "D_3") (pintype "passive"))
      (node (ref "Q38") (pin "2") (pinfunction "S_2") (pintype "passive"))
    )
    (net (code "73") (name "Net-(Q24-D)") (class "Default")
      (node (ref "Q24") (pin "3") (pinfunction "D_3") (pintype "passive"))
      (node (ref "R75") (pin "1") (pinfunction "1_1") (pintype "passive"))
    )
    (net (code "74") (name "Net-(Q24-G)") (class "Default")
      (node (ref "D13") (pin "A") (pinfunction "A_A") (pintype "passive"))
      (node (ref "Q24") (pin "1") (pinfunction "G_1") (pintype "passive"))
      (node (ref "Q25") (pin "3") (pinfunction "D_3") (pintype "passive"))
      (node (ref "R76") (pin "1") (pinfunction "1_1") (pintype "passive"))
      (node (ref "TP50") (pin "1") (pinfunction "1_1") (pintype "passive"))
    )
    (net (code "75") (name "Net-(Q26-D)") (class "Default")
      (node (ref "Q26") (pin "3") (pinfunction "D_3") (pintype "passive"))
      (node (ref "R78") (pin "1") (pinfunction "1_1") (pintype "passive"))
    )
    (net (code "76") (name "Net-(Q26-G)") (class "Default")
      (node (ref "Q26") (pin "1") (pinfunction "G_1") (pintype "passive"))
      (node (ref "Q27") (pin "3") (pinfunction "D_3") (pintype "passive"))
      (node (ref "R79") (pin "2") (pinfunction "2_2") (pintype "passive"))
      (node (ref "TP52") (pin "1") (pinfunction "1_1") (pintype "passive"))
    )
    (net (code "77") (name "Net-(Q31-G)") (class "Default")
      (node (ref "Q31") (pin "4") (pinfunction "G_4") (pintype "passive"))
      (node (ref "U15") (pin "5") (pinfunction "GATE_5") (pintype "output"))
    )
    (net (code "78") (name "Net-(Q32-D)") (class "Default")
      (node (ref "Q32") (pin "3") (pinfunction "D_3") (pintype "passive"))
      (node (ref "Q34") (pin "4") (pinfunction "G_4") (pintype "passive"))
      (node (ref "R90") (pin "1") (pinfunction "1_1") (pintype "passive"))
    )
    (net (code "79") (name "Net-(Q32-G)") (class "Default")
      (node (ref "D7") (pin "A") (pinfunction "A_A") (pintype "passive"))
      (node (ref "Q32") (pin "1") (pinfunction "G_1") (pintype "passive"))
      (node (ref "R88") (pin "1") (pinfunction "1_1") (pintype "passive"))
    )
    (net (code "80") (name "Net-(Q33-D)") (class "Default")
      (node (ref "Q33") (pin "3") (pinfunction "D_3") (pintype "passive"))
      (node (ref "Q35") (pin "4") (pinfunction "G_4") (pintype "passive"))
      (node (ref "R91") (pin "1") (pinfunction "1_1") (pintype "passive"))
    )
    (net (code "81") (name "Net-(Q33-G)") (class "Default")
      (node (ref "D8") (pin "A") (pinfunction "A_A") (pintype "passive"))
      (node (ref "Q33") (pin "1") (pinfunction "G_1") (pintype "passive"))
      (node (ref "R89") (pin "2") (pinfunction "2_2") (pintype "passive"))
    )
    (net (code "82") (name "Net-(Q36-G)") (class "Default")
      (node (ref "Q36") (pin "4") (pinfunction "G_4") (pintype "passive"))
      (node (ref "U16") (pin "5") (pinfunction "GATE_5") (pintype "output"))
    )
    (net (code "83") (name "Net-(Q38-D)") (class "Default")
      (node (ref "D11") (pin "C") (pinfunction "C_C") (pintype "passive"))
      (node (ref "D12") (pin "C") (pinfunction "C_C") (pintype "passive"))
      (node (ref "D4") (pin "C") (pinfunction "C_C") (pintype "passive"))
      (node (ref "D9") (pin "C") (pinfunction "C_C") (pintype "passive"))
      (node (ref "Q38") (pin "3") (pinfunction "D_3") (pintype "passive"))
      (node (ref "Q39") (pin "3") (pinfunction "D_3") (pintype "passive"))
    )
    (net (code "84") (name "Net-(Q42A-D)") (class "Default")
      (node (ref "Q42") (pin "2") (pinfunction "S_2") (pintype "passive"))
      (node (ref "Q42") (pin "6") (pinfunction "D_6") (pintype "passive"))
    )
    (net (code "85") (name "Net-(Q42A-G)") (class "Default")
      (node (ref "D9") (pin "A") (pinfunction "A_A") (pintype "passive"))
      (node (ref "Q42") (pin "1") (pinfunction "G_1") (pintype "passive"))
      (node (ref "R40") (pin "2") (pinfunction "2_2") (pintype "passive"))
    )
    (net (code "86") (name "Net-(Q42B-D)") (class "Default")
      (node (ref "JP14") (pin "1") (pinfunction "1_1") (pintype "passive"))
      (node (ref "JP16") (pin "1") (pinfunction "1_1") (pintype "passive"))
      (node (ref "Q42") (pin "4") (pinfunction "D_4") (pintype "passive"))
      (node (ref "Q43") (pin "4") (pinfunction "D_4") (pintype "passive"))
    )
    (net (code "87") (name "Net-(Q42B-G)") (class "Default")
      (node (ref "D4") (pin "A") (pinfunction "A_A") (pintype "passive"))
      (node (ref "Q42") (pin "3") (pinfunction "G_3") (pintype "passive"))
      (node (ref "R41") (pin "2") (pinfunction "2_2") (pintype "passive"))
    )
    (net (code "88") (name "Net-(Q43A-D)") (class "Default")
      (node (ref "Q43") (pin "2") (pinfunction "S_2") (pintype "passive"))
      (node (ref "Q43") (pin "6") (pinfunction "D_6") (pintype "passive"))
    )
    (net (code "89") (name "Net-(Q43A-G)") (class "Default")
      (node (ref "D12") (pin "A") (pinfunction "A_A") (pintype "passive"))
      (node (ref "Q43") (pin "1") (pinfunction "G_1") (pintype "passive"))
      (node (ref "R43") (pin "2") (pinfunction "2_2") (pintype "passive"))
    )
    (net (code "90") (name "Net-(Q43B-G)") (class "Default")
      (node (ref "D11") (pin "A") (pinfunction "A_A") (pintype "passive"))
      (node (ref "Q43") (pin "3") (pinfunction "G_3") (pintype "passive"))
      (node (ref "R42") (pin "2") (pinfunction "2_2") (pintype "passive"))
    )
    (net (code "91") (name "Net-(Q44-D)") (class "Default")
      (node (ref "Q44") (pin "3") (pinfunction "D_3") (pintype "passive"))
      (node (ref "R34") (pin "1") (pinfunction "1_1") (pintype "passive"))
    )
    (net (code "92") (name "Net-(SW3-PadNC)") (class "Default")
      (node (ref "SW3") (pin "NC") (pinfunction "NC_NC") (pintype "passive"))
      (node (ref "SW4") (pin "NC") (pinfunction "NC_NC") (pintype "passive"))
    )
    (net (code "93") (name "Net-(U1-IO6)") (class "Default")
      (node (ref "TP5") (pin "1") (pinfunction "1_1") (pintype "passive"))
      (node (ref "U1") (pin "11") (pinfunction "IO6_11") (pintype "bidirectional"))
    )
    (net (code "94") (name "Net-(U1-IO7)") (class "Default")
      (node (ref "TP4") (pin "1") (pinfunction "1_1") (pintype "passive"))
      (node (ref "U1") (pin "12") (pinfunction "IO7_12") (pintype "bidirectional"))
      (node (ref "U6") (pin "3") (pinfunction "IN2_3") (pintype "input"))
      (node (ref "U6") (pin "7") (pinfunction "IN1_7") (pintype "input"))
    )
    (net (code "95") (name "Net-(U1-~{RESET})") (class "Default")
      (node (ref "R18") (pin "1") (pinfunction "1_1") (pintype "passive"))
      (node (ref "U1") (pin "13") (pinfunction "~{RESET}_13") (pintype "input"))
    )
    (net (code "96") (name "Net-(U2-INP)") (class "Default")
      (node (ref "C1") (pin "1") (pinfunction "1_1") (pintype "passive"))
      (node (ref "R19") (pin "1") (pinfunction "1_1") (pintype "passive"))
      (node (ref "R21") (pin "1") (pinfunction "1_1") (pintype "passive"))
      (node (ref "U2") (pin "1") (pinfunction "INP_1") (pintype "input"))
    )
    (net (code "97") (name "Net-(U2-OUT)") (class "Default")
      (node (ref "R12") (pin "1") (pinfunction "1_1") (pintype "passive"))
      (node (ref "TP6") (pin "1") (pinfunction "1_1") (pintype "passive"))
      (node (ref "U2") (pin "4") (pinfunction "OUT_4") (pintype "output"))
    )
    (net (code "98") (name "Net-(U3-INP)") (class "Default")
      (node (ref "C2") (pin "1") (pinfunction "1_1") (pintype "passive"))
      (node (ref "R20") (pin "1") (pinfunction "1_1") (pintype "passive"))
      (node (ref "R22") (pin "1") (pinfunction "1_1") (pintype "passive"))
      (node (ref "U3") (pin "1") (pinfunction "INP_1") (pintype "input"))
    )
    (net (code "99") (name "Net-(U3-OUT)") (class "Default")
      (node (ref "R13") (pin "1") (pinfunction "1_1") (pintype "passive"))
      (node (ref "TP7") (pin "1") (pinfunction "1_1") (pintype "passive"))
      (node (ref "U3") (pin "4") (pinfunction "OUT_4") (pintype "output"))
    )
    (net (code "100") (name "Net-(U4-CIN1+)") (class "Default")
      (node (ref "R33") (pin "1") (pinfunction "1_1") (pintype "passive"))
      (node (ref "R35") (pin "2") (pinfunction "2_2") (pintype "passive"))
      (node (ref "TP16") (pin "1") (pinfunction "1_1") (pintype "passive"))
      (node (ref "U4") (pin "10") (pinfunction "CIN1+_10") (pintype "input"))
    )
    (net (code "101") (name "Net-(U4-CIN1-)") (class "Default")
      (node (ref "R32") (pin "1") (pinfunction "1_1") (pintype "passive"))
      (node (ref "R34") (pin "2") (pinfunction "2_2") (pintype "passive"))
      (node (ref "TP13") (pin "1") (pinfunction "1_1") (pintype "passive"))
      (node (ref "U4") (pin "11") (pinfunction "CIN1-_11") (pintype "input"))
    )
    (net (code "102") (name "Net-(U4-CIN2+)") (class "Default")
      (node (ref "R32") (pin "2") (pinfunction "2_2") (pintype "passive"))
      (node (ref "U4") (pin "12") (pinfunction "REF_12") (pintype "output"))
      (node (ref "U4") (pin "8") (pinfunction "CIN2+_8") (pintype "input"))
    )
    (net (code "103") (name "Net-(U4-INHIBIT)") (class "Default")
      (node (ref "R27") (pin "1") (pinfunction "1_1") (pintype "passive"))
      (node (ref "U4") (pin "5") (pinfunction "INHIBIT_5") (pintype "input"))
    )
    (net (code "104") (name "Net-(U4-IOUT)") (class "Default")
      (node (ref "R33") (pin "2") (pinfunction "2_2") (pintype "passive"))
      (node (ref "U4") (pin "14") (pinfunction "IOUT_14") (pintype "output"))
    )
    (net (code "105") (name "Net-(U4-RS+)") (class "Default")
      (node (ref "Q3") (pin "1") (pinfunction "D_1") (pintype "passive"))
      (node (ref "Q3") (pin "2") (pinfunction "D_2") (pintype "passive"))
      (node (ref "Q3") (pin "5") (pinfunction "D_5") (pintype "passive"))
      (node (ref "Q3") (pin "6") (pinfunction "D_6") (pintype "passive"))
      (node (ref "R30") (pin "1") (pinfunction "1_1") (pintype "passive"))
      (node (ref "U4") (pin "16") (pinfunction "RS+_16") (pintype "passive"))
    )
    (net (code "106") (name "Net-(U5-PG)") (class "Default")
      (node (ref "TP12") (pin "1") (pinfunction "1_1") (pintype "passive"))
      (node (ref "U5") (pin "13") (pinfunction "PG_13") (pintype "open_collector"))
    )
    (net (code "107") (name "Net-(U5-SYNC)") (class "Default")
      (node (ref "R28") (pin "1") (pinfunction "1_1") (pintype "passive"))
      (node (ref "R29") (pin "2") (pinfunction "2_2") (pintype "passive"))
      (node (ref "TP10") (pin "1") (pinfunction "1_1") (pintype "passive"))
      (node (ref "U5") (pin "5") (pinfunction "SYNC_5") (pintype "input"))
    )
    (net (code "108") (name "Net-(U6-NO1)") (class "Default")
      (node (ref "R57") (pin "1") (pinfunction "1_1") (pintype "passive"))
      (node (ref "U6") (pin "1") (pinfunction "NO1_1") (pintype "bidirectional"))
    )
    (net (code "109") (name "Net-(U6-NO2)") (class "Default")
      (node (ref "R67") (pin "1") (pinfunction "1_1") (pintype "passive"))
      (node (ref "U6") (pin "5") (pinfunction "NO2_5") (pintype "bidirectional"))
    )
    (net (code "110") (name "Net-(U8-CDT)") (class "Default")
      (node (ref "C16") (pin "1") (pinfunction "1_1") (pintype "passive"))
      (node (ref "U8") (pin "4") (pinfunction "CDT_4") (pintype "passive"))
    )
    (net (code "111") (name "Net-(U8-CO)") (class "Default")
      (node (ref "R52") (pin "1") (pinfunction "1_1") (pintype "passive"))
      (node (ref "U8") (pin "7") (pinfunction "CO_7") (pintype "open_collector"))
    )
    (net (code "112") (name "Net-(U8-CTLC)") (class "Default")
      (node (ref "R45") (pin "2") (pinfunction "2_2") (pintype "passive"))
      (node (ref "TP26") (pin "1") (pinfunction "1_1") (pintype "passive"))
      (node (ref "U8") (pin "1") (pinfunction "CTLC_1") (pintype "passive"))
    )
    (net (code "113") (name "Net-(U8-CTLD)") (class "Default")
      (node (ref "R48") (pin "2") (pinfunction "2_2") (pintype "passive"))
      (node (ref "TP28") (pin "1") (pinfunction "1_1") (pintype "passive"))
      (node (ref "U8") (pin "2") (pinfunction "CTLD_2") (pintype "input"))
    )
    (net (code "114") (name "Net-(U8-DO)") (class "Default")
      (node (ref "R53") (pin "1") (pinfunction "1_1") (pintype "passive"))
      (node (ref "U8") (pin "6") (pinfunction "DO_6") (pintype "open_collector"))
    )
    (net (code "115") (name "Net-(U8-VDD)") (class "Default")
      (node (ref "C15") (pin "1") (pinfunction "1_1") (pintype "passive"))
      (node (ref "R51") (pin "1") (pinfunction "1_1") (pintype "passive"))
      (node (ref "U8") (pin "3") (pinfunction "VDD_3") (pintype "power_in"))
    )
    (net (code "116") (name "Net-(U9-CDT)") (class "Default")
      (node (ref "C18") (pin "1") (pinfunction "1_1") (pintype "passive"))
      (node (ref "U9") (pin "4") (pinfunction "CDT_4") (pintype "passive"))
    )
    (net (code "117") (name "Net-(U9-CTLC)") (class "Default")
      (node (ref "R52") (pin "2") (pinfunction "2_2") (pintype "passive"))
      (node (ref "TP30") (pin "1") (pinfunction "1_1") (pintype "passive"))
      (node (ref "U9") (pin "1") (pinfunction "CTLC_1") (pintype "passive"))
    )
    (net (code "118") (name "Net-(U9-CTLD)") (class "Default")
      (node (ref "R53") (pin "2") (pinfunction "2_2") (pintype "passive"))
      (node (ref "TP31") (pin "1") (pinfunction "1_1") (pintype "passive"))
      (node (ref "U9") (pin "2") (pinfunction "CTLD_2") (pintype "input"))
    )
    (net (code "119") (name "Net-(U9-VDD)") (class "Default")
      (node (ref "C17") (pin "1") (pinfunction "1_1") (pintype "passive"))
      (node (ref "R54") (pin "1") (pinfunction "1_1") (pintype "passive"))
      (node (ref "U9") (pin "3") (pinfunction "VDD_3") (pintype "power_in"))
    )
    (net (code "120") (name "Net-(U10-VIN)") (class "Default")
      (node (ref "C19") (pin "1") (pinfunction "1_1") (pintype "passive"))
      (node (ref "Q12") (pin "5") (pinfunction "D_5") (pintype "passive"))
      (node (ref "Q12") (pin "6") (pinfunction "D_6") (pintype "passive"))
      (node (ref "Q12") (pin "7") (pinfunction "D_7") (pintype "passive"))
      (node (ref "Q12") (pin "8") (pinfunction "D_8") (pintype "passive"))
      (node (ref "Q12") (pin "PAD") (pinfunction "D_PAD") (pintype "passive"))
      (node (ref "Q13") (pin "5") (pinfunction "D_5") (pintype "passive"))
      (node (ref "Q13") (pin "6") (pinfunction "D_6") (pintype "passive"))
      (node (ref "Q13") (pin "7") (pinfunction "D_7") (pintype "passive"))
      (node (ref "Q13") (pin "8") (pinfunction "D_8") (pintype "passive"))
      (node (ref "Q13") (pin "PAD") (pinfunction "D_PAD") (pintype "passive"))
      (node (ref "TP23") (pin "1") (pinfunction "1_1") (pintype "passive"))
      (node (ref "U10") (pin "1") (pinfunction "VIN_1") (pintype "power_in"))
    )
    (net (code "121") (name "Net-(U11-SENSE)") (class "Default")
      (node (ref "Q18") (pin "1") (pinfunction "S_1") (pintype "passive"))
      (node (ref "Q18") (pin "2") (pinfunction "S_2") (pintype "passive"))
      (node (ref "Q18") (pin "3") (pinfunction "S_3") (pintype "passive"))
      (node (ref "Q19") (pin "1") (pinfunction "S_1") (pintype "passive"))
      (node (ref "Q19") (pin "2") (pinfunction "S_2") (pintype "passive"))
      (node (ref "Q19") (pin "3") (pinfunction "S_3") (pintype "passive"))
      (node (ref "R55") (pin "2") (pinfunction "2_2") (pintype "passive"))
      (node (ref "TP44") (pin "1") (pinfunction "1_1") (pintype "passive"))
      (node (ref "U11") (pin "6") (pinfunction "SENSE_6") (pintype "input"))
    )
    (net (code "122") (name "Net-(U12-AIN1)") (class "Default")
      (node (ref "JP2") (pin "1") (pinfunction "1_1") (pintype "passive"))
      (node (ref "R73") (pin "1") (pinfunction "1_1") (pintype "passive"))
      (node (ref "U12") (pin "9") (pinfunction "AIN1_9") (pintype "input"))
    )
    (net (code "123") (name "Net-(U12-AIN2)") (class "Default")
      (node (ref "JP1") (pin "1") (pinfunction "1_1") (pintype "passive"))
      (node (ref "R71") (pin "1") (pinfunction "1_1") (pintype "passive"))
      (node (ref "U12") (pin "10") (pinfunction "AIN2_10") (pintype "input"))
    )
    (net (code "124") (name "Net-(U12-CELL1)") (class "Default")
      (node (ref "C20") (pin "2") (pinfunction "2_2") (pintype "passive"))
      (node (ref "C21") (pin "1") (pinfunction "1_1") (pintype "passive"))
      (node (ref "R66") (pin "2") (pinfunction "2_2") (pintype "passive"))
      (node (ref "TP46") (pin "1") (pinfunction "1_1") (pintype "passive"))
      (node (ref "U12") (pin "6") (pinfunction "CELL2_6") (pintype "passive"))
      (node (ref "U12") (pin "7") (pinfunction "CELL1_7") (pintype "passive"))
    )
    (net (code "125") (name "Net-(U12-REG2)") (class "Default")
      (node (ref "C25") (pin "1") (pinfunction "1_1") (pintype "passive"))
      (node (ref "U12") (pin "3") (pinfunction "REG2_3") (pintype "power_in"))
    )
    (net (code "126") (name "Net-(U12-REG3)") (class "Default")
      (node (ref "C24") (pin "1") (pinfunction "1_1") (pintype "passive"))
      (node (ref "U12") (pin "1") (pinfunction "REG3_1") (pintype "power_in"))
    )
    (net (code "127") (name "Net-(U12-THRM)") (class "Default")
      (node (ref "R71") (pin "2") (pinfunction "2_2") (pintype "passive"))
      (node (ref "R73") (pin "2") (pinfunction "2_2") (pintype "passive"))
      (node (ref "U12") (pin "14") (pinfunction "THRM_14") (pintype "passive"))
    )
    (net (code "128") (name "Net-(U12-VBATT)") (class "Default")
      (node (ref "C20") (pin "1") (pinfunction "1_1") (pintype "passive"))
      (node (ref "C22") (pin "1") (pinfunction "1_1") (pintype "passive"))
      (node (ref "R65") (pin "1") (pinfunction "1_1") (pintype "passive"))
      (node (ref "U12") (pin "5") (pinfunction "VBATT_5") (pintype "power_in"))
    )
    (net (code "129") (name "Net-(U13-CDT)") (class "Default")
      (node (ref "C27") (pin "1") (pinfunction "1_1") (pintype "passive"))
      (node (ref "U13") (pin "4") (pinfunction "CDT_4") (pintype "passive"))
    )
    (net (code "130") (name "Net-(U13-CO)") (class "Default")
      (node (ref "R82") (pin "1") (pinfunction "1_1") (pintype "passive"))
      (node (ref "U13") (pin "7") (pinfunction "CO_7") (pintype "open_collector"))
    )
    (net (code "131") (name "Net-(U13-CTLC)") (class "Default")
      (node (ref "R75") (pin "2") (pinfunction "2_2") (pintype "passive"))
      (node (ref "TP49") (pin "1") (pinfunction "1_1") (pintype "passive"))
      (node (ref "U13") (pin "1") (pinfunction "CTLC_1") (pintype "passive"))
    )
    (net (code "132") (name "Net-(U13-CTLD)") (class "Default")
      (node (ref "R78") (pin "2") (pinfunction "2_2") (pintype "passive"))
      (node (ref "TP51") (pin "1") (pinfunction "1_1") (pintype "passive"))
      (node (ref "U13") (pin "2") (pinfunction "CTLD_2") (pintype "input"))
    )
    (net (code "133") (name "Net-(U13-DO)") (class "Default")
      (node (ref "R83") (pin "1") (pinfunction "1_1") (pintype "passive"))
      (node (ref "U13") (pin "6") (pinfunction "DO_6") (pintype "open_collector"))
    )
    (net (code "134") (name "Net-(U13-VDD)") (class "Default")
      (node (ref "C26") (pin "1") (pinfunction "1_1") (pintype "passive"))
      (node (ref "R81") (pin "1") (pinfunction "1_1") (pintype "passive"))
      (node (ref "U13") (pin "3") (pinfunction "VDD_3") (pintype "power_in"))
    )
    (net (code "135") (name "Net-(U14-CDT)") (class "Default")
      (node (ref "C29") (pin "1") (pinfunction "1_1") (pintype "passive"))
      (node (ref "U14") (pin "4") (pinfunction "CDT_4") (pintype "passive"))
    )
    (net (code "136") (name "Net-(U14-CTLC)") (class "Default")
      (node (ref "R82") (pin "2") (pinfunction "2_2") (pintype "passive"))
      (node (ref "TP53") (pin "1") (pinfunction "1_1") (pintype "passive"))
      (node (ref "U14") (pin "1") (pinfunction "CTLC_1") (pintype "passive"))
    )
    (net (code "137") (name "Net-(U14-CTLD)") (class "Default")
      (node (ref "R83") (pin "2") (pinfunction "2_2") (pintype "passive"))
      (node (ref "TP54") (pin "1") (pinfunction "1_1") (pintype "passive"))
      (node (ref "U14") (pin "2") (pinfunction "CTLD_2") (pintype "input"))
    )
    (net (code "138") (name "Net-(U14-VDD)") (class "Default")
      (node (ref "C28") (pin "1") (pinfunction "1_1") (pintype "passive"))
      (node (ref "R84") (pin "1") (pinfunction "1_1") (pintype "passive"))
      (node (ref "U14") (pin "3") (pinfunction "VDD_3") (pintype "power_in"))
    )
    (net (code "139") (name "Net-(U15-VIN)") (class "Default")
      (node (ref "C30") (pin "1") (pinfunction "1_1") (pintype "passive"))
      (node (ref "Q30") (pin "5") (pinfunction "D_5") (pintype "passive"))
      (node (ref "Q30") (pin "6") (pinfunction "D_6") (pintype "passive"))
      (node (ref "Q30") (pin "7") (pinfunction "D_7") (pintype "passive"))
      (node (ref "Q30") (pin "8") (pinfunction "D_8") (pintype "passive"))
      (node (ref "Q30") (pin "PAD") (pinfunction "D_PAD") (pintype "passive"))
      (node (ref "Q31") (pin "5") (pinfunction "D_5") (pintype "passive"))
      (node (ref "Q31") (pin "6") (pinfunction "D_6") (pintype "passive"))
      (node (ref "Q31") (pin "7") (pinfunction "D_7") (pintype "passive"))
      (node (ref "Q31") (pin "8") (pinfunction "D_8") (pintype "passive"))
      (node (ref "Q31") (pin "PAD") (pinfunction "D_PAD") (pintype "passive"))
      (node (ref "TP24") (pin "1") (pinfunction "1_1") (pintype "passive"))
      (node (ref "U15") (pin "1") (pinfunction "VIN_1") (pintype "power_in"))
    )
    (net (code "140") (name "Net-(U16-SENSE)") (class "Default")
      (node (ref "Q36") (pin "1") (pinfunction "S_1") (pintype "passive"))
      (node (ref "Q36") (pin "2") (pinfunction "S_2") (pintype "passive"))
      (node (ref "Q36") (pin "3") (pinfunction "S_3") (pintype "passive"))
      (node (ref "Q37") (pin "1") (pinfunction "S_1") (pintype "passive"))
      (node (ref "Q37") (pin "2") (pinfunction "S_2") (pintype "passive"))
      (node (ref "Q37") (pin "3") (pinfunction "S_3") (pintype "passive"))
      (node (ref "R97") (pin "2") (pinfunction "2_2") (pintype "passive"))
      (node (ref "TP67") (pin "1") (pinfunction "1_1") (pintype "passive"))
      (node (ref "U16") (pin "6") (pinfunction "SENSE_6") (pintype "input"))
    )
    (net (code "141") (name "Net-(U17-AIN1)") (class "Default")
      (node (ref "JP4") (pin "1") (pinfunction "1_1") (pintype "passive"))
      (node (ref "R103") (pin "1") (pinfunction "1_1") (pintype "passive"))
      (node (ref "U17") (pin "9") (pinfunction "AIN1_9") (pintype "input"))
    )
    (net (code "142") (name "Net-(U17-AIN2)") (class "Default")
      (node (ref "JP3") (pin "1") (pinfunction "1_1") (pintype "passive"))
      (node (ref "R101") (pin "1") (pinfunction "1_1") (pintype "passive"))
      (node (ref "U17") (pin "10") (pinfunction "AIN2_10") (pintype "input"))
    )
    (net (code "143") (name "Net-(U17-CELL1)") (class "Default")
      (node (ref "C31") (pin "2") (pinfunction "2_2") (pintype "passive"))
      (node (ref "C32") (pin "1") (pinfunction "1_1") (pintype "passive"))
      (node (ref "R96") (pin "2") (pinfunction "2_2") (pintype "passive"))
      (node (ref "TP69") (pin "1") (pinfunction "1_1") (pintype "passive"))
      (node (ref "U17") (pin "6") (pinfunction "CELL2_6") (pintype "passive"))
      (node (ref "U17") (pin "7") (pinfunction "CELL1_7") (pintype "passive"))
    )
    (net (code "144") (name "Net-(U17-REG2)") (class "Default")
      (node (ref "C36") (pin "1") (pinfunction "1_1") (pintype "passive"))
      (node (ref "U17") (pin "3") (pinfunction "REG2_3") (pintype "power_in"))
    )
    (net (code "145") (name "Net-(U17-REG3)") (class "Default")
      (node (ref "C35") (pin "1") (pinfunction "1_1") (pintype "passive"))
      (node (ref "U17") (pin "1") (pinfunction "REG3_1") (pintype "power_in"))
    )
    (net (code "146") (name "Net-(U17-THRM)") (class "Default")
      (node (ref "R101") (pin "2") (pinfunction "2_2") (pintype "passive"))
      (node (ref "R103") (pin "2") (pinfunction "2_2") (pintype "passive"))
      (node (ref "U17") (pin "14") (pinfunction "THRM_14") (pintype "passive"))
    )
    (net (code "147") (name "Net-(U17-VBATT)") (class "Default")
      (node (ref "C31") (pin "1") (pinfunction "1_1") (pintype "passive"))
      (node (ref "C33") (pin "1") (pinfunction "1_1") (pintype "passive"))
      (node (ref "R95") (pin "1") (pinfunction "1_1") (pintype "passive"))
      (node (ref "U17") (pin "5") (pinfunction "VBATT_5") (pintype "power_in"))
    )
    (net (code "148") (name "Net-(U21-PB3)") (class "Default")
      (node (ref "R68") (pin "1") (pinfunction "1_1") (pintype "passive"))
      (node (ref "U21") (pin "39") (pinfunction "PB3_39") (pintype "bidirectional"))
    )
    (net (code "149") (name "Net-(U21-PB4)") (class "Default")
      (node (ref "R72") (pin "1") (pinfunction "1_1") (pintype "passive"))
      (node (ref "U21") (pin "40") (pinfunction "PB4_40") (pintype "bidirectional"))
    )
    (net (code "150") (name "Net-(U21-PF0-OSC_IN)") (class "Default")
      (node (ref "C47") (pin "1") (pinfunction "1_1") (pintype "passive"))
      (node (ref "U21") (pin "5") (pinfunction "PF0-OSC_IN_5") (pintype "bidirectional"))
      (node (ref "X3") (pin "1") (pinfunction "1_1") (pintype "passive"))
    )
    (net (code "151") (name "Net-(U21-PF1-OSC_OUT)") (class "Default")
      (node (ref "C46") (pin "1") (pinfunction "1_1") (pintype "passive"))
      (node (ref "U21") (pin "6") (pinfunction "PF1-OSC_OUT_6") (pintype "bidirectional"))
      (node (ref "X3") (pin "3") (pinfunction "2_3") (pintype "passive"))
    )
    (net (code "152") (name "ON{slash}~{OFF}") (class "Default")
      (node (ref "C4") (pin "1") (pinfunction "1_1") (pintype "passive"))
      (node (ref "Q2") (pin "1") (pinfunction "G_1") (pintype "passive"))
      (node (ref "R23") (pin "2") (pinfunction "2_2") (pintype "passive"))
      (node (ref "R24") (pin "2") (pinfunction "2_2") (pintype "passive"))
      (node (ref "TP8") (pin "1") (pinfunction "1_1") (pintype "passive"))
      (node (ref "U1") (pin "8") (pinfunction "IO3_8") (pintype "bidirectional"))
      (node (ref "U4") (pin "1") (pinfunction "VCC_1") (pintype "power_in"))
    )
    (net (code "153") (name "OPD_PWR") (class "Default")
      (node (ref "J1") (pin "15") (pinfunction "15_15") (pintype "passive"))
      (node (ref "J1") (pin "16") (pinfunction "16_16") (pintype "passive"))
      (node (ref "R1") (pin "1") (pinfunction "1_1") (pintype "passive"))
    )
    (net (code "154") (name "OPD_SCL") (class "Default")
      (node (ref "J1") (pin "13") (pinfunction "13_13") (pintype "passive"))
      (node (ref "J1") (pin "14") (pinfunction "14_14") (pintype "passive"))
      (node (ref "R6") (pin "1") (pinfunction "1_1") (pintype "passive"))
    )
    (net (code "155") (name "OPD_SDA") (class "Default")
      (node (ref "J1") (pin "11") (pinfunction "11_11") (pintype "passive"))
      (node (ref "J1") (pin "12") (pinfunction "12_12") (pintype "passive"))
      (node (ref "R7") (pin "1") (pinfunction "1_1") (pintype "passive"))
    )
    (net (code "156") (name "PA0") (class "Default")
      (node (ref "R111") (pin "2") (pinfunction "2_2") (pintype "passive"))
      (node (ref "U21") (pin "10") (pinfunction "PA0_10") (pintype "bidirectional"))
    )
    (net (code "157") (name "PA2{slash}USART2_TX") (class "Default")
      (node (ref "J4") (pin "13") (pinfunction "CARD-TX_13") (pintype "passive"))
      (node (ref "U21") (pin "12") (pinfunction "PA2_12") (pintype "bidirectional"))
      (node (ref "U6") (pin "6") (pinfunction "COM2_6") (pintype "bidirectional"))
    )
    (net (code "158") (name "PA3{slash}USART2_RX") (class "Default")
      (node (ref "J4") (pin "12") (pinfunction "CARD-RX_12") (pintype "passive"))
      (node (ref "U21") (pin "13") (pinfunction "PA3_13") (pintype "bidirectional"))
      (node (ref "U6") (pin "2") (pinfunction "COM1_2") (pintype "bidirectional"))
    )
    (net (code "159") (name "PA8{slash}POUTPROT") (class "Default")
      (node (ref "R112") (pin "2") (pinfunction "2_2") (pintype "passive"))
      (node (ref "U21") (pin "29") (pinfunction "PA8_29") (pintype "bidirectional"))
    )
    (net (code "160") (name "PA9{slash}CAN_SILENT") (class "Default")
      (node (ref "U20") (pin "8") (pinfunction "S_8") (pintype "input"))
      (node (ref "U21") (pin "30") (pinfunction "PA9_30") (pintype "bidirectional"))
    )
    (net (code "161") (name "PB6{slash}SCL") (class "Default")
      (node (ref "R113") (pin "1") (pinfunction "1_1") (pintype "passive"))
      (node (ref "TP21") (pin "1") (pinfunction "1_1") (pintype "passive"))
      (node (ref "U1") (pin "4") (pinfunction "IO0_4") (pintype "bidirectional"))
      (node (ref "U12") (pin "11") (pinfunction "SCL_11") (pintype "input"))
      (node (ref "U21") (pin "42") (pinfunction "PB6_42") (pintype "bidirectional"))
    )
    (net (code "162") (name "PB7{slash}SDA") (class "Default")
      (node (ref "R114") (pin "1") (pinfunction "1_1") (pintype "passive"))
      (node (ref "TP22") (pin "1") (pinfunction "1_1") (pintype "passive"))
      (node (ref "U1") (pin "5") (pinfunction "IO1_5") (pintype "bidirectional"))
      (node (ref "U12") (pin "12") (pinfunction "SDA_12") (pintype "bidirectional"))
      (node (ref "U21") (pin "43") (pinfunction "PB7_43") (pintype "bidirectional"))
    )
    (net (code "163") (name "PEN-SCL-FILT") (class "Default")
      (node (ref "Q1") (pin "4") (pinfunction "D_4") (pintype "passive"))
      (node (ref "R14") (pin "1") (pinfunction "1_1") (pintype "passive"))
      (node (ref "R19") (pin "2") (pinfunction "2_2") (pintype "passive"))
      (node (ref "R2") (pin "1") (pinfunction "1_1") (pintype "passive"))
      (node (ref "R8") (pin "1") (pinfunction "1_1") (pintype "passive"))
      (node (ref "TP2") (pin "1") (pinfunction "1_1") (pintype "passive"))
      (node (ref "U1") (pin "15") (pinfunction "SCL_15") (pintype "input"))
    )
    (net (code "164") (name "PEN-SDA-FILT") (class "Default")
      (node (ref "Q1") (pin "6") (pinfunction "D_6") (pintype "passive"))
      (node (ref "R10") (pin "2") (pinfunction "2_2") (pintype "passive"))
      (node (ref "R16") (pin "2") (pinfunction "2_2") (pintype "passive"))
      (node (ref "R20") (pin "2") (pinfunction "2_2") (pintype "passive"))
      (node (ref "R4") (pin "2") (pinfunction "2_2") (pintype "passive"))
      (node (ref "TP3") (pin "1") (pinfunction "1_1") (pintype "passive"))
      (node (ref "U1") (pin "16") (pinfunction "SDA_16") (pintype "bidirectional"))
    )
    (net (code "165") (name "POUT") (class "Default")
      (node (ref "R112") (pin "1") (pinfunction "1_1") (pintype "passive"))
      (node (ref "TP11") (pin "1") (pinfunction "1_1") (pintype "passive"))
      (node (ref "U4") (pin "13") (pinfunction "POUT_13") (pintype "output"))
    )
    (net (code "166") (name "SWCLK") (class "Default")
      (node (ref "J4") (pin "15") (pinfunction "SWCLK_15") (pintype "passive"))
      (node (ref "U21") (pin "37") (pinfunction "PA14-SWCLK_37") (pintype "bidirectional"))
    )
    (net (code "167") (name "SWDIO") (class "Default")
      (node (ref "J4") (pin "14") (pinfunction "SWDIO_14") (pintype "passive"))
      (node (ref "U21") (pin "34") (pinfunction "PA13-SWDIO_34") (pintype "bidirectional"))
    )
    (net (code "168") (name "VBAT") (class "Default")
      (node (ref "C10") (pin "1") (pinfunction "1_1") (pintype "passive"))
      (node (ref "C11") (pin "1") (pinfunction "1_1") (pintype "passive"))
      (node (ref "C23") (pin "1") (pinfunction "1_1") (pintype "passive"))
      (node (ref "C34") (pin "1") (pinfunction "1_1") (pintype "passive"))
      (node (ref "Q13") (pin "1") (pinfunction "S_1") (pintype "passive"))
      (node (ref "Q13") (pin "2") (pinfunction "S_2") (pintype "passive"))
      (node (ref "Q13") (pin "3") (pinfunction "S_3") (pintype "passive"))
      (node (ref "Q18") (pin "5") (pinfunction "D_5") (pintype "passive"))
      (node (ref "Q18") (pin "6") (pinfunction "D_6") (pintype "passive"))
      (node (ref "Q18") (pin "7") (pinfunction "D_7") (pintype "passive"))
      (node (ref "Q18") (pin "8") (pinfunction "D_8") (pintype "passive"))
      (node (ref "Q18") (pin "PAD") (pinfunction "D_PAD") (pintype "passive"))
      (node (ref "Q31") (pin "1") (pinfunction "S_1") (pintype "passive"))
      (node (ref "Q31") (pin "2") (pinfunction "S_2") (pintype "passive"))
      (node (ref "Q31") (pin "3") (pinfunction "S_3") (pintype "passive"))
      (node (ref "Q36") (pin "5") (pinfunction "D_5") (pintype "passive"))
      (node (ref "Q36") (pin "6") (pinfunction "D_6") (pintype "passive"))
      (node (ref "Q36") (pin "7") (pinfunction "D_7") (pintype "passive"))
      (node (ref "Q36") (pin "8") (pinfunction "D_8") (pintype "passive"))
      (node (ref "Q36") (pin "PAD") (pinfunction "D_PAD") (pintype "passive"))
      (node (ref "SW3") (pin "C") (pinfunction "COM_C") (pintype "passive"))
      (node (ref "TP36") (pin "1") (pinfunction "1_1") (pintype "passive"))
      (node (ref "TP59") (pin "1") (pinfunction "1_1") (pintype "passive"))
      (node (ref "U10") (pin "6") (pinfunction "SENSE_6") (pintype "input"))
      (node (ref "U11") (pin "1") (pinfunction "VIN_1") (pintype "power_in"))
      (node (ref "U15") (pin "6") (pinfunction "SENSE_6") (pintype "input"))
      (node (ref "U16") (pin "1") (pinfunction "VIN_1") (pintype "power_in"))
    )
    (net (code "169") (name "VBATT-PK1") (class "Default")
      (node (ref "F1") (pin "2") (pinfunction "P$2_2") (pintype "passive"))
      (node (ref "F3") (pin "2") (pinfunction "P$2_2") (pintype "passive"))
      (node (ref "Q16") (pin "5") (pinfunction "D_5") (pintype "passive"))
      (node (ref "Q16") (pin "6") (pinfunction "D_6") (pintype "passive"))
      (node (ref "Q16") (pin "7") (pinfunction "D_7") (pintype "passive"))
      (node (ref "Q16") (pin "8") (pinfunction "D_8") (pintype "passive"))
      (node (ref "Q16") (pin "PAD") (pinfunction "D_PAD") (pintype "passive"))
      (node (ref "R54") (pin "2") (pinfunction "2_2") (pintype "passive"))
      (node (ref "R65") (pin "2") (pinfunction "2_2") (pintype "passive"))
      (node (ref "TP38") (pin "1") (pinfunction "1_1") (pintype "passive"))
    )
    (net (code "170") (name "VBATT-PK2") (class "Default")
      (node (ref "F2") (pin "2") (pinfunction "P$2_2") (pintype "passive"))
      (node (ref "F4") (pin "2") (pinfunction "P$2_2") (pintype "passive"))
      (node (ref "Q34") (pin "5") (pinfunction "D_5") (pintype "passive"))
      (node (ref "Q34") (pin "6") (pinfunction "D_6") (pintype "passive"))
      (node (ref "Q34") (pin "7") (pinfunction "D_7") (pintype "passive"))
      (node (ref "Q34") (pin "8") (pinfunction "D_8") (pintype "passive"))
      (node (ref "Q34") (pin "PAD") (pinfunction "D_PAD") (pintype "passive"))
      (node (ref "R84") (pin "2") (pinfunction "2_2") (pintype "passive"))
      (node (ref "R95") (pin "2") (pinfunction "2_2") (pintype "passive"))
      (node (ref "TP61") (pin "1") (pinfunction "1_1") (pintype "passive"))
    )
    (net (code "171") (name "VBUS") (class "Default")
      (node (ref "J1") (pin "23") (pinfunction "23_23") (pintype "passive"))
      (node (ref "J1") (pin "24") (pinfunction "24_24") (pintype "passive"))
      (node (ref "J1") (pin "25") (pinfunction "25_25") (pintype "passive"))
      (node (ref "J1") (pin "26") (pinfunction "26_26") (pintype "passive"))
      (node (ref "Q3") (pin "4") (pinfunction "S_4") (pintype "passive"))
      (node (ref "R25") (pin "2") (pinfunction "2_2") (pintype "passive"))
      (node (ref "SW4") (pin "C") (pinfunction "COM_C") (pintype "passive"))
      (node (ref "TP25") (pin "1") (pinfunction "1_1") (pintype "passive"))
    )
    (net (code "172") (name "VBUSP") (class "Default")
      (node (ref "C5") (pin "1") (pinfunction "1_1") (pintype "passive"))
      (node (ref "C6") (pin "1") (pinfunction "1_1") (pintype "passive"))
      (node (ref "C7") (pin "2") (pinfunction "2_2") (pintype "passive"))
      (node (ref "J4") (pin "1") (pinfunction "VBUSP_1") (pintype "passive"))
      (node (ref "J4") (pin "2") (pinfunction "VBUSP_2") (pintype "passive"))
      (node (ref "Q4") (pin "1") (pinfunction "D_1") (pintype "passive"))
      (node (ref "Q4") (pin "2") (pinfunction "D_2") (pintype "passive"))
      (node (ref "Q4") (pin "5") (pinfunction "D_5") (pintype "passive"))
      (node (ref "Q4") (pin "6") (pinfunction "D_6") (pintype "passive"))
      (node (ref "Q42") (pin "5") (pinfunction "S_5") (pintype "passive"))
      (node (ref "Q43") (pin "5") (pinfunction "S_5") (pintype "passive"))
      (node (ref "R28") (pin "2") (pinfunction "2_2") (pintype "passive"))
      (node (ref "R39") (pin "2") (pinfunction "2_2") (pintype "passive"))
      (node (ref "R40") (pin "1") (pinfunction "1_1") (pintype "passive"))
      (node (ref "R41") (pin "1") (pinfunction "1_1") (pintype "passive"))
      (node (ref "R42") (pin "1") (pinfunction "1_1") (pintype "passive"))
      (node (ref "R43") (pin "1") (pinfunction "1_1") (pintype "passive"))
      (node (ref "TP18") (pin "1") (pinfunction "1_1") (pintype "passive"))
      (node (ref "U5") (pin "2") (pinfunction "VIN_2") (pintype "power_in"))
      (node (ref "U5") (pin "3") (pinfunction "VIN_3") (pintype "power_in"))
      (node (ref "U5") (pin "4") (pinfunction "EN_4") (pintype "input"))
      (node (ref "U5") (pin "8") (pinfunction "VIN_8") (pintype "power_in"))
    )
    (net (code "173") (name "VPD") (class "Default")
      (node (ref "C3") (pin "2") (pinfunction "2_2") (pintype "passive"))
      (node (ref "C9") (pin "2") (pinfunction "2_2") (pintype "passive"))
      (node (ref "J2") (pin "2") (pinfunction "2_2") (pintype "passive"))
      (node (ref "R1") (pin "2") (pinfunction "2_2") (pintype "passive"))
      (node (ref "R15") (pin "2") (pinfunction "2_2") (pintype "passive"))
      (node (ref "R18") (pin "2") (pinfunction "2_2") (pintype "passive"))
      (node (ref "R21") (pin "2") (pinfunction "2_2") (pintype "passive"))
      (node (ref "R22") (pin "2") (pinfunction "2_2") (pintype "passive"))
      (node (ref "R3") (pin "2") (pinfunction "2_2") (pintype "passive"))
      (node (ref "R38") (pin "2") (pinfunction "2_2") (pintype "passive"))
      (node (ref "R9") (pin "2") (pinfunction "2_2") (pintype "passive"))
      (node (ref "TP1") (pin "1") (pinfunction "1_1") (pintype "passive"))
      (node (ref "U1") (pin "14") (pinfunction "V+_14") (pintype "power_in"))
      (node (ref "U2") (pin "5") (pinfunction "VDD_5") (pintype "power_in"))
      (node (ref "U3") (pin "5") (pinfunction "VDD_5") (pintype "power_in"))
      (node (ref "U6") (pin "8") (pinfunction "V+_8") (pintype "power_in"))
    )
    (net (code "174") (name "unconnected-(FIDUCIAL1-PadFIDUCIAL)") (class "Default")
      (node (ref "FIDUCIAL1") (pin "FIDUCIAL") (pinfunction "FIDUCIAL_FIDUCIAL") (pintype "no_connect"))
    )
    (net (code "175") (name "unconnected-(FIDUCIAL2-PadFIDUCIAL)") (class "Default")
      (node (ref "FIDUCIAL2") (pin "FIDUCIAL") (pinfunction "FIDUCIAL_FIDUCIAL") (pintype "no_connect"))
    )
    (net (code "176") (name "unconnected-(FIDUCIAL3-PadFIDUCIAL)") (class "Default")
      (node (ref "FIDUCIAL3") (pin "FIDUCIAL") (pinfunction "FIDUCIAL_FIDUCIAL") (pintype "no_connect"))
    )
    (net (code "177") (name "unconnected-(J1-Pad1)") (class "Default")
      (node (ref "J1") (pin "1") (pinfunction "1_1") (pintype "passive"))
    )
    (net (code "178") (name "unconnected-(J1-Pad2)") (class "Default")
      (node (ref "J1") (pin "2") (pinfunction "2_2") (pintype "passive"))
    )
    (net (code "179") (name "unconnected-(J1-Pad3)") (class "Default")
      (node (ref "J1") (pin "3") (pinfunction "3_3") (pintype "passive"))
    )
    (net (code "180") (name "unconnected-(J1-Pad4)") (class "Default")
      (node (ref "J1") (pin "4") (pinfunction "4_4") (pintype "passive"))
    )
    (net (code "181") (name "unconnected-(J1-Pad5)") (class "Default")
      (node (ref "J1") (pin "5") (pinfunction "5_5") (pintype "passive"))
    )
    (net (code "182") (name "unconnected-(J1-Pad6)") (class "Default")
      (node (ref "J1") (pin "6") (pinfunction "6_6") (pintype "passive"))
    )
    (net (code "183") (name "unconnected-(J1-Pad7)") (class "Default")
      (node (ref "J1") (pin "7") (pinfunction "7_7") (pintype "passive"))
    )
    (net (code "184") (name "unconnected-(J1-Pad8)") (class "Default")
      (node (ref "J1") (pin "8") (pinfunction "8_8") (pintype "passive"))
    )
    (net (code "185") (name "unconnected-(J1-Pad9)") (class "Default")
      (node (ref "J1") (pin "9") (pinfunction "9_9") (pintype "passive"))
    )
    (net (code "186") (name "unconnected-(J1-Pad10)") (class "Default")
      (node (ref "J1") (pin "10") (pinfunction "10_10") (pintype "passive"))
    )
    (net (code "187") (name "unconnected-(J1-Pad17)") (class "Default")
      (node (ref "J1") (pin "17") (pinfunction "17_17") (pintype "passive"))
    )
    (net (code "188") (name "unconnected-(J1-Pad18)") (class "Default")
      (node (ref "J1") (pin "18") (pinfunction "18_18") (pintype "passive"))
    )
    (net (code "189") (name "unconnected-(J1-Pad19)") (class "Default")
      (node (ref "J1") (pin "19") (pinfunction "19_19") (pintype "passive"))
    )
    (net (code "190") (name "unconnected-(J1-Pad20)") (class "Default")
      (node (ref "J1") (pin "20") (pinfunction "20_20") (pintype "passive"))
    )
    (net (code "191") (name "unconnected-(J1-Pad21)") (class "Default")
      (node (ref "J1") (pin "21") (pinfunction "21_21") (pintype "passive"))
    )
    (net (code "192") (name "unconnected-(J1-Pad22)") (class "Default")
      (node (ref "J1") (pin "22") (pinfunction "22_22") (pintype "passive"))
    )
    (net (code "193") (name "unconnected-(J1-Pad31)") (class "Default")
      (node (ref "J1") (pin "31") (pinfunction "31_31") (pintype "passive"))
    )
    (net (code "194") (name "unconnected-(J1-Pad32)") (class "Default")
      (node (ref "J1") (pin "32") (pinfunction "32_32") (pintype "passive"))
    )
    (net (code "195") (name "unconnected-(J4-DEVICE-D+-Pad4)") (class "Default")
      (node (ref "J4") (pin "4") (pinfunction "DEVICE-D+_4") (pintype "passive"))
    )
    (net (code "196") (name "unconnected-(J4-DEVICE-D--Pad5)") (class "Default")
      (node (ref "J4") (pin "5") (pinfunction "DEVICE-D-_5") (pintype "passive"))
    )
    (net (code "197") (name "unconnected-(J4-HOST-D+-Pad7)") (class "Default")
      (node (ref "J4") (pin "7") (pinfunction "HOST-D+_7") (pintype "passive"))
    )
    (net (code "198") (name "unconnected-(J4-HOST-D--Pad8)") (class "Default")
      (node (ref "J4") (pin "8") (pinfunction "HOST-D-_8") (pintype "passive"))
    )
    (net (code "199") (name "unconnected-(SW1-PadNC)") (class "Default")
      (node (ref "SW1") (pin "NC") (pinfunction "NC_NC") (pintype "passive"))
    )
    (net (code "200") (name "unconnected-(SW2-PadNC)") (class "Default")
      (node (ref "SW2") (pin "NC") (pinfunction "NC_NC") (pintype "passive"))
    )
    (net (code "201") (name "unconnected-(SW3-PadNO)") (class "Default")
      (node (ref "SW3") (pin "NO") (pinfunction "NO_NO") (pintype "passive"))
    )
    (net (code "202") (name "unconnected-(SW4-PadNO)") (class "Default")
      (node (ref "SW4") (pin "NO") (pinfunction "NO_NO") (pintype "passive"))
    )
    (net (code "203") (name "unconnected-(U8-CB-Pad8)") (class "Default")
      (node (ref "U8") (pin "8") (pinfunction "CB_8") (pintype "output"))
    )
    (net (code "204") (name "unconnected-(U9-CB-Pad8)") (class "Default")
      (node (ref "U9") (pin "8") (pinfunction "CB_8") (pintype "output"))
    )
    (net (code "205") (name "unconnected-(U12-CELLX-Pad13)") (class "Default")
      (node (ref "U12") (pin "13") (pinfunction "CELLX_13") (pintype "passive"))
    )
    (net (code "206") (name "unconnected-(U13-CB-Pad8)") (class "Default")
      (node (ref "U13") (pin "8") (pinfunction "CB_8") (pintype "output"))
    )
    (net (code "207") (name "unconnected-(U14-CB-Pad8)") (class "Default")
      (node (ref "U14") (pin "8") (pinfunction "CB_8") (pintype "output"))
    )
    (net (code "208") (name "unconnected-(U17-CELLX-Pad13)") (class "Default")
      (node (ref "U17") (pin "13") (pinfunction "CELLX_13") (pintype "passive"))
    )
    (net (code "209") (name "unconnected-(U21-PA6-Pad16)") (class "Default")
      (node (ref "U21") (pin "16") (pinfunction "PA6_16") (pintype "bidirectional"))
    )
    (net (code "210") (name "unconnected-(U21-PA15-Pad38)") (class "Default")
      (node (ref "U21") (pin "38") (pinfunction "PA15_38") (pintype "bidirectional"))
    )
    (net (code "211") (name "unconnected-(U21-PB2-Pad20)") (class "Default")
      (node (ref "U21") (pin "20") (pinfunction "PB2_20") (pintype "bidirectional"))
    )
    (net (code "212") (name "unconnected-(U21-PB8-Pad45)") (class "Default")
      (node (ref "U21") (pin "45") (pinfunction "PB8_45") (pintype "bidirectional"))
    )
    (net (code "213") (name "unconnected-(U21-PB9-Pad46)") (class "Default")
      (node (ref "U21") (pin "46") (pinfunction "PB9_46") (pintype "bidirectional"))
    )
    (net (code "214") (name "unconnected-(U21-PC13-Pad2)") (class "Default")
      (node (ref "U21") (pin "2") (pinfunction "PC13_2") (pintype "bidirectional"))
    )
    (net (code "215") (name "~{CHARGE-PK1}") (class "Default")
      (node (ref "Q19") (pin "4") (pinfunction "G_4") (pintype "passive"))
      (node (ref "R55") (pin "1") (pinfunction "1_1") (pintype "passive"))
      (node (ref "TP33") (pin "1") (pinfunction "1_1") (pintype "passive"))
      (node (ref "U9") (pin "7") (pinfunction "CO_7") (pintype "open_collector"))
    )
    (net (code "216") (name "~{CHARGE-PK2}") (class "Default")
      (node (ref "Q37") (pin "4") (pinfunction "G_4") (pintype "passive"))
      (node (ref "R97") (pin "1") (pinfunction "1_1") (pintype "passive"))
      (node (ref "TP56") (pin "1") (pinfunction "1_1") (pintype "passive"))
      (node (ref "U14") (pin "7") (pinfunction "CO_7") (pintype "open_collector"))
    )
    (net (code "217") (name "~{DISCHARGE-PK1}") (class "Default")
      (node (ref "Q12") (pin "4") (pinfunction "G_4") (pintype "passive"))
      (node (ref "R74") (pin "2") (pinfunction "2_2") (pintype "passive"))
      (node (ref "TP32") (pin "1") (pinfunction "1_1") (pintype "passive"))
      (node (ref "U9") (pin "6") (pinfunction "DO_6") (pintype "open_collector"))
    )
    (net (code "218") (name "~{DISCHARGE-PK2}") (class "Default")
      (node (ref "Q30") (pin "4") (pinfunction "G_4") (pintype "passive"))
      (node (ref "R56") (pin "1") (pinfunction "1_1") (pintype "passive"))
      (node (ref "TP55") (pin "1") (pinfunction "1_1") (pintype "passive"))
      (node (ref "U14") (pin "6") (pinfunction "DO_6") (pintype "open_collector"))
    )
    (net (code "219") (name "~{FAULT}") (class "Default")
      (node (ref "Q5") (pin "3") (pinfunction "D_3") (pintype "passive"))
      (node (ref "R38") (pin "1") (pinfunction "1_1") (pintype "passive"))
      (node (ref "TP17") (pin "1") (pinfunction "1_1") (pintype "passive"))
      (node (ref "U1") (pin "7") (pinfunction "IO2_7") (pintype "bidirectional"))
    )
    (net (code "220") (name "~{SD}") (class "Default")
      (node (ref "D13") (pin "C") (pinfunction "C_C") (pintype "passive"))
      (node (ref "D14") (pin "C") (pinfunction "C_C") (pintype "passive"))
      (node (ref "D5") (pin "C") (pinfunction "C_C") (pintype "passive"))
      (node (ref "D6") (pin "C") (pinfunction "C_C") (pintype "passive"))
      (node (ref "D7") (pin "C") (pinfunction "C_C") (pintype "passive"))
      (node (ref "D8") (pin "C") (pinfunction "C_C") (pintype "passive"))
      (node (ref "J1") (pin "39") (pinfunction "39_39") (pintype "passive"))
      (node (ref "J1") (pin "40") (pinfunction "40_40") (pintype "passive"))
      (node (ref "SW1") (pin "NO") (pinfunction "NO_NO") (pintype "passive"))
      (node (ref "SW2") (pin "NO") (pinfunction "NO_NO") (pintype "passive"))
      (node (ref "TP57") (pin "1") (pinfunction "1_1") (pintype "passive"))
    )
  )
)
